# SixPak_Ultra.net
KiCad netlist of a schematic drawn in Altium Designer
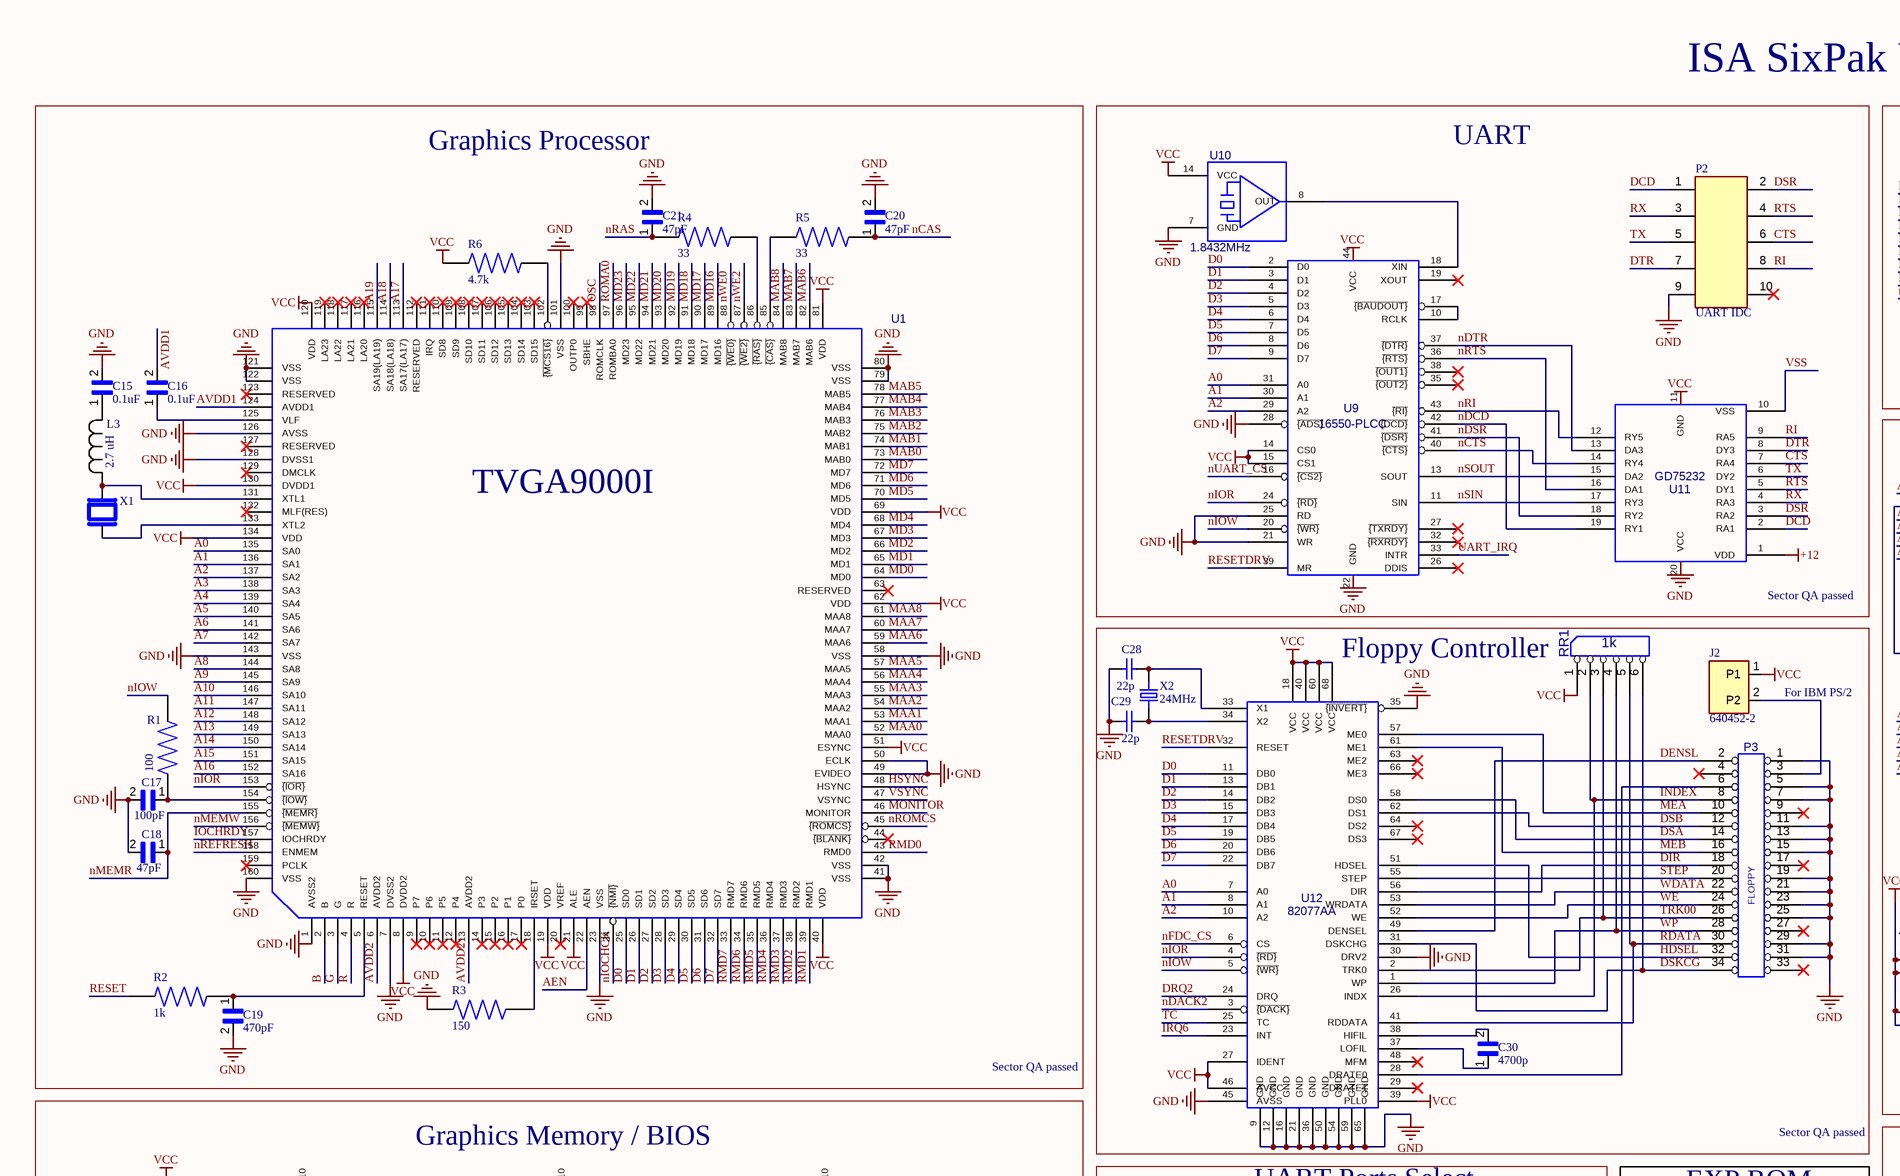
[diagram p0: SixPak Ultra.SchDoc, top left]
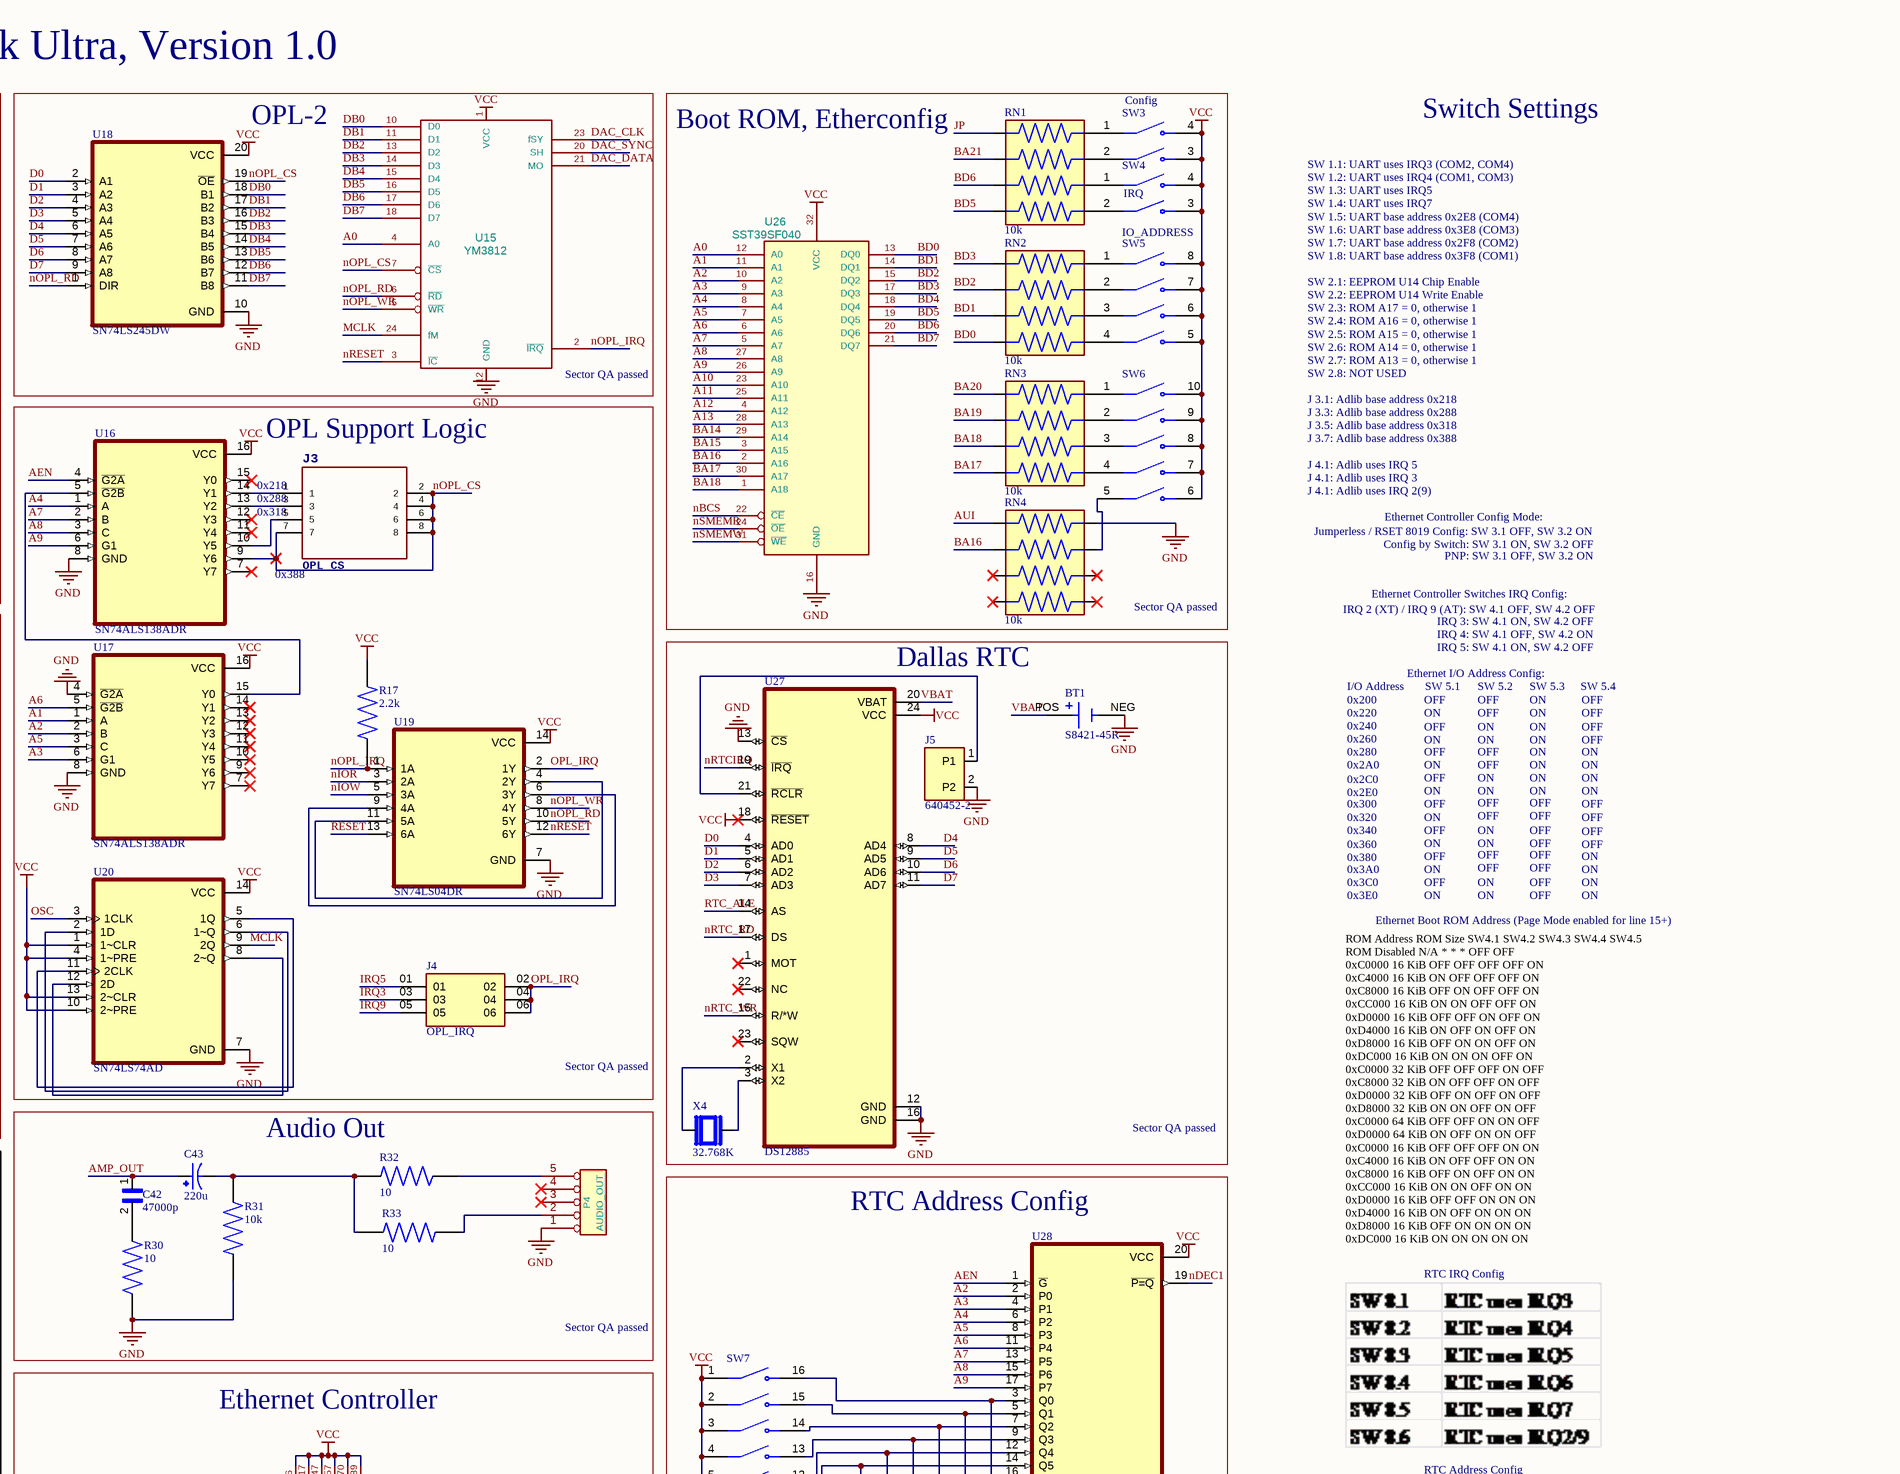
[diagram p1: SixPak Ultra.SchDoc, top right]
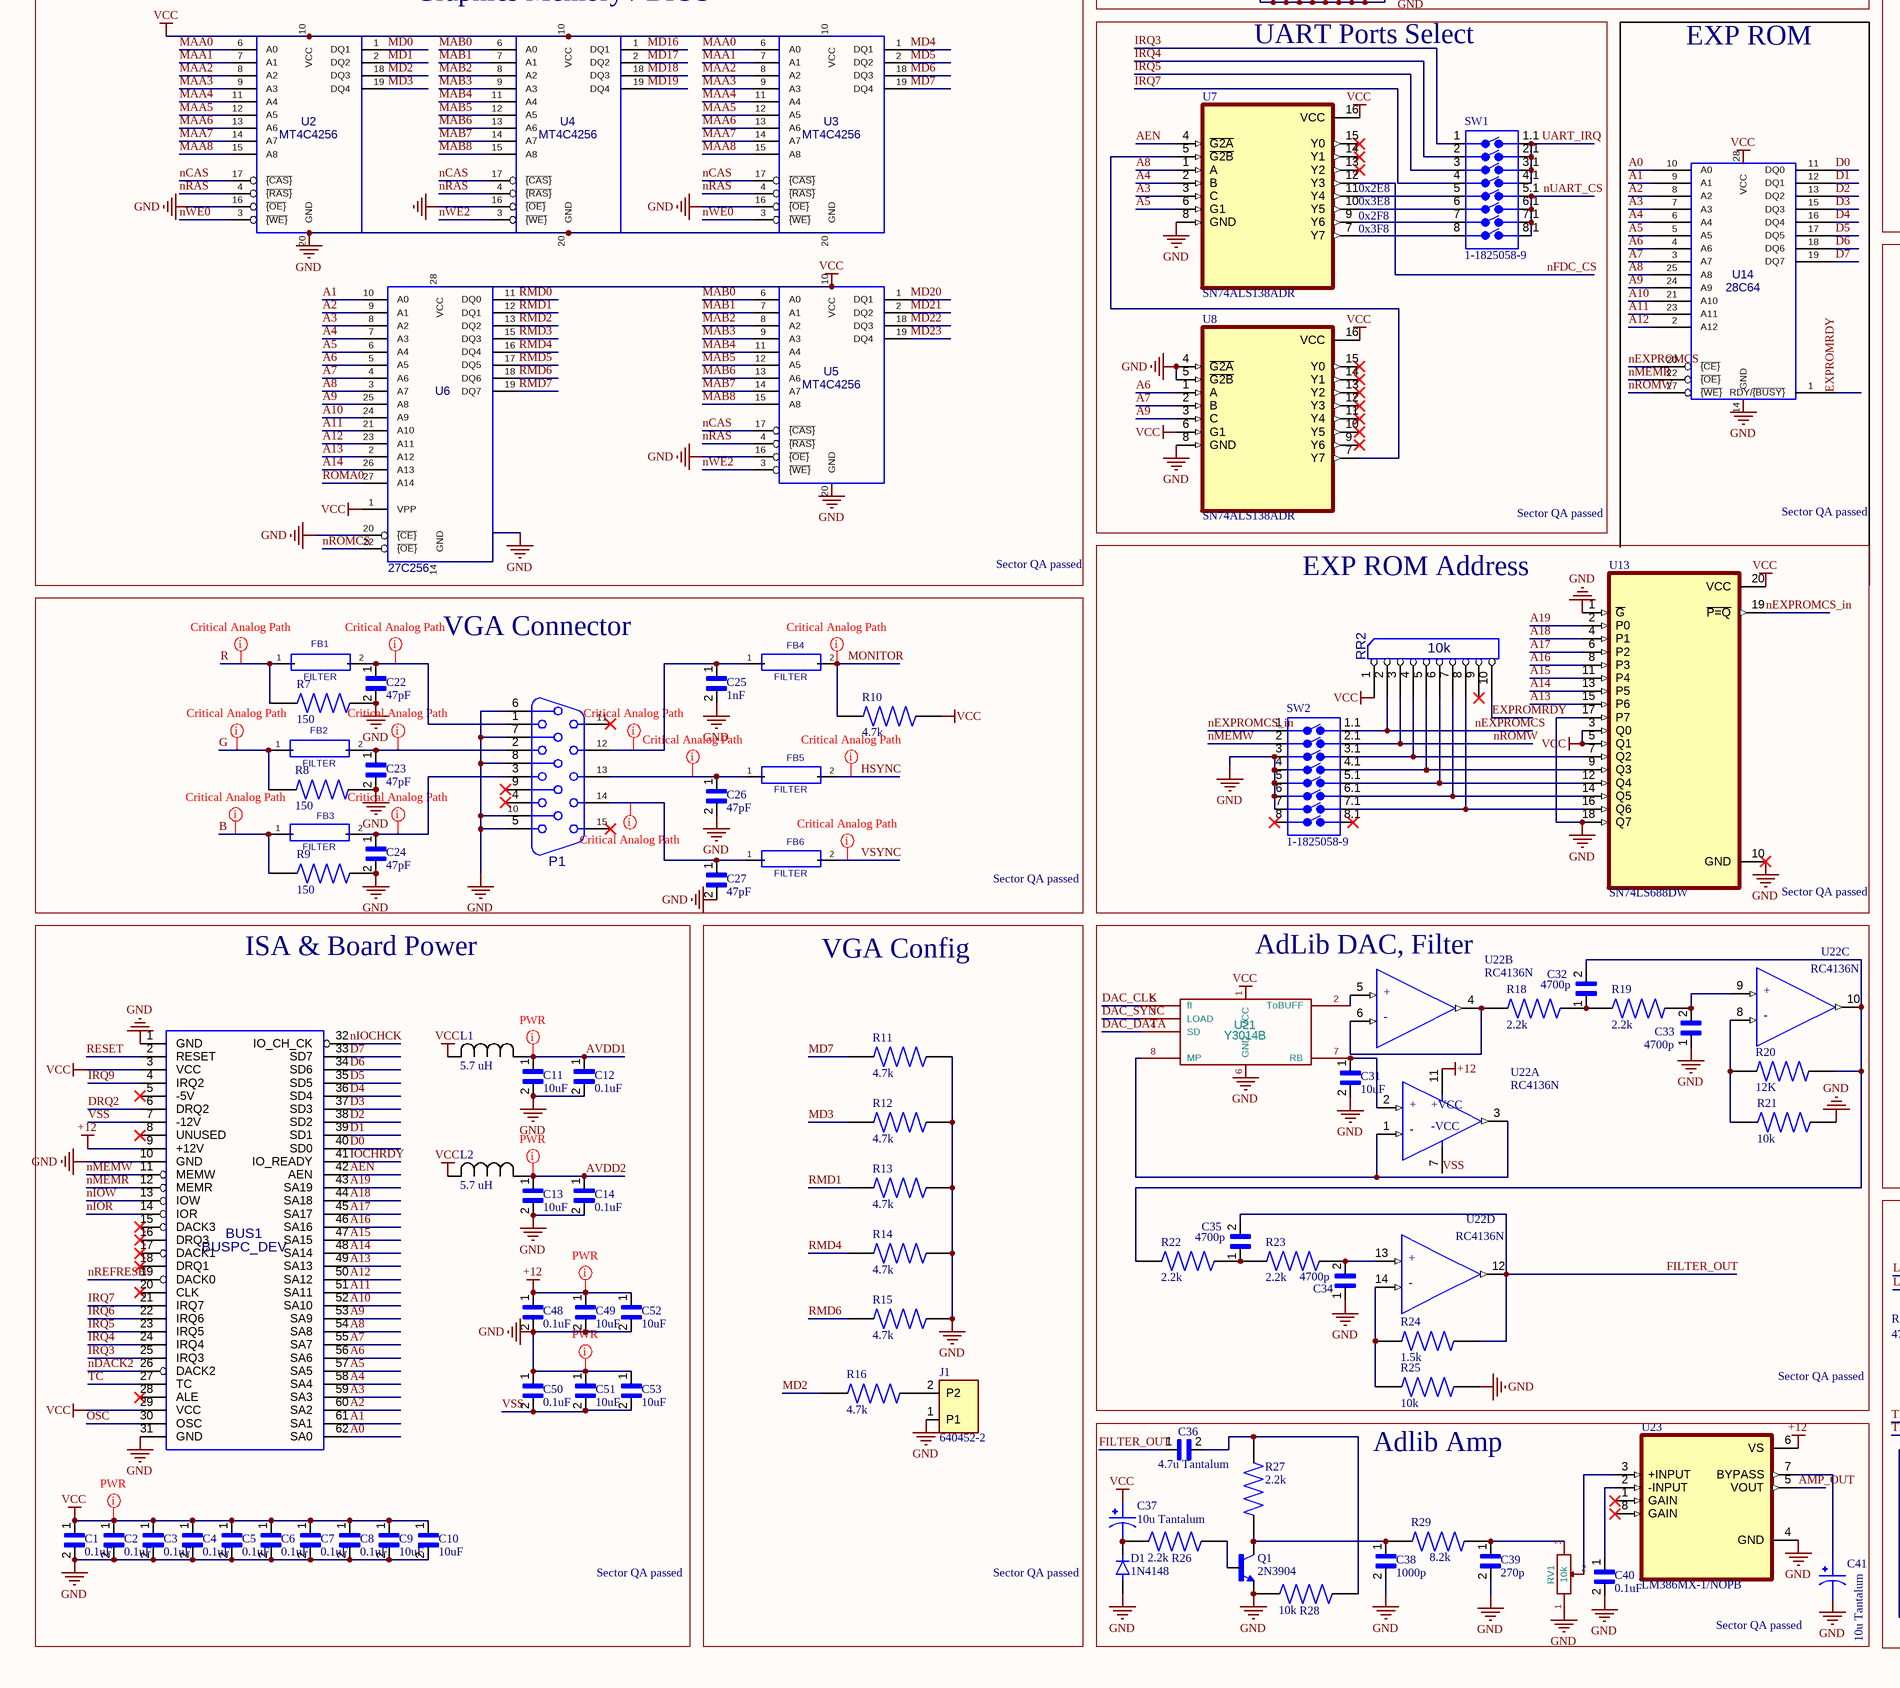
[diagram p2: SixPak Ultra.SchDoc, bottom left]
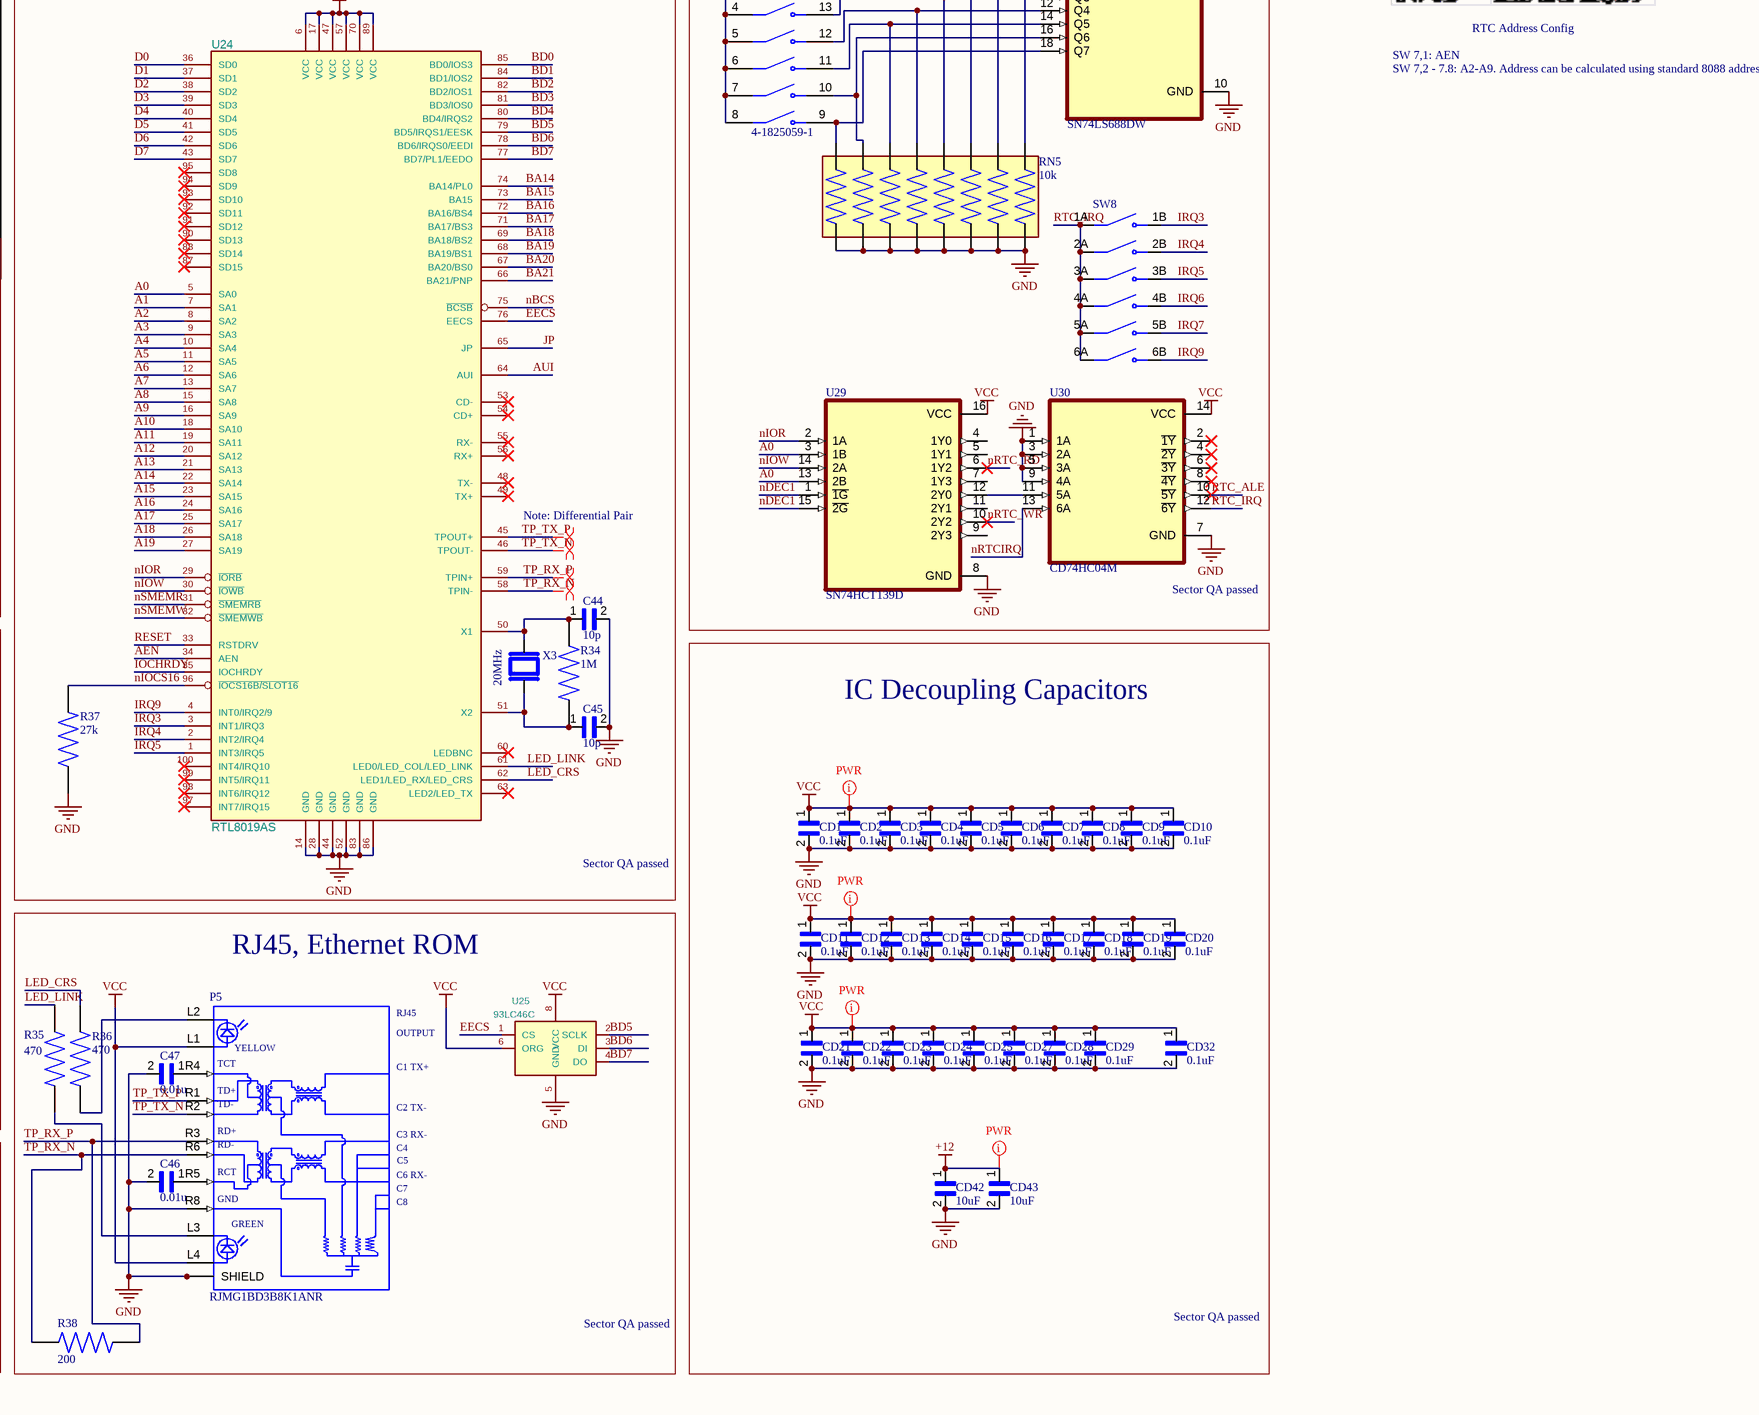
[diagram p3: SixPak Ultra.SchDoc, bottom right]

(export (version "E")
  (design (tool "Eeschema 10.0.6"))
  (components
    (comp (ref "BT1")
      (value "S8421-45R")
      (footprint "BAT_S8421-45R")
      (description "Battery Holder (Open) Coin, 20.0mm 1 Cell SMD (SMT) Tab")
      (fields (field (name "MF") "{'manufacturer': u'Harwin Inc.'}"))
      (libsource (lib "SixPakUltra_Mac") (part "S8421-45R"))
    )
    (comp (ref "BUS1")
      (value "BUSPC_DEV")
      (footprint "Conn_Bus_ISA8")
      (libsource (lib "isa_svga-rescue") (part "BUSPC_DEV"))
    )
    (comp (ref "C1")
      (value "0.1uF")
      (footprint "CAPC2012X140N")
      (description "0.1ÂµF Molded Tantalum Capacitors 35V 0805 _2012 Metric_ 29Ohm")
      (fields (field (name "MF") "AVX") (field (name "MP") "TAJR104K035RNJ"))
      (libsource (lib "TAJR104K035RNJ") (part "TAJR104K035RNJ"))
    )
    (comp (ref "C2")
      (value "0.1uF")
      (footprint "CAPC2012X140N")
      (description "0.1ÂµF Molded Tantalum Capacitors 35V 0805 _2012 Metric_ 29Ohm")
      (fields (field (name "MF") "AVX") (field (name "MP") "TAJR104K035RNJ"))
      (libsource (lib "TAJR104K035RNJ") (part "TAJR104K035RNJ"))
    )
    (comp (ref "C3")
      (value "0.1uF")
      (footprint "CAPC2012X140N")
      (description "0.1ÂµF Molded Tantalum Capacitors 35V 0805 _2012 Metric_ 29Ohm")
      (fields (field (name "MF") "AVX") (field (name "MP") "TAJR104K035RNJ"))
      (libsource (lib "TAJR104K035RNJ") (part "TAJR104K035RNJ"))
    )
    (comp (ref "C4")
      (value "0.1uF")
      (footprint "CAPC2012X140N")
      (description "0.1ÂµF Molded Tantalum Capacitors 35V 0805 _2012 Metric_ 29Ohm")
      (fields (field (name "MF") "AVX") (field (name "MP") "TAJR104K035RNJ"))
      (libsource (lib "TAJR104K035RNJ") (part "TAJR104K035RNJ"))
    )
    (comp (ref "C5")
      (value "0.1uF")
      (footprint "CAPC2012X140N")
      (description "0.1ÂµF Molded Tantalum Capacitors 35V 0805 _2012 Metric_ 29Ohm")
      (fields (field (name "MF") "AVX") (field (name "MP") "TAJR104K035RNJ"))
      (libsource (lib "TAJR104K035RNJ") (part "TAJR104K035RNJ"))
    )
    (comp (ref "C6")
      (value "0.1uF")
      (footprint "CAPC2012X140N")
      (description "0.1ÂµF Molded Tantalum Capacitors 35V 0805 _2012 Metric_ 29Ohm")
      (fields (field (name "MF") "AVX") (field (name "MP") "TAJR104K035RNJ"))
      (libsource (lib "TAJR104K035RNJ") (part "TAJR104K035RNJ"))
    )
    (comp (ref "C7")
      (value "0.1uF")
      (footprint "CAPC2012X140N")
      (description "0.1ÂµF Molded Tantalum Capacitors 35V 0805 _2012 Metric_ 29Ohm")
      (fields (field (name "MF") "AVX") (field (name "MP") "TAJR104K035RNJ"))
      (libsource (lib "TAJR104K035RNJ") (part "TAJR104K035RNJ"))
    )
    (comp (ref "C8")
      (value "0.1uF")
      (footprint "CAPC2012X140N")
      (description "0.1ÂµF Molded Tantalum Capacitors 35V 0805 _2012 Metric_ 29Ohm")
      (fields (field (name "MF") "AVX") (field (name "MP") "TAJR104K035RNJ"))
      (libsource (lib "TAJR104K035RNJ") (part "TAJR104K035RNJ"))
    )
    (comp (ref "C9")
      (value "10uF")
      (footprint "CAPC2012X140N")
      (description "Cap Tant Solid 10uF 16V R CASE 10% (2 X 1.35 X 1.35mm) SMD 2012-15 5 Ohm 125ÂÂŽ T/R")
      (fields (field (name "MP") "TACR106K016XTA"))
      (libsource (lib "TACR106K016XTA") (part "TACR106K016XTA"))
    )
    (comp (ref "C10")
      (value "10uF")
      (footprint "CAPC2012X140N")
      (description "Cap Tant Solid 10uF 16V R CASE 10% (2 X 1.35 X 1.35mm) SMD 2012-15 5 Ohm 125ÂÂŽ T/R")
      (fields (field (name "MP") "TACR106K016XTA"))
      (libsource (lib "TACR106K016XTA") (part "TACR106K016XTA"))
    )
    (comp (ref "C11")
      (value "10uF")
      (footprint "CAPC2012X140N")
      (description "Cap Tant Solid 10uF 16V R CASE 10% (2 X 1.35 X 1.35mm) SMD 2012-15 5 Ohm 125ÂÂŽ T/R")
      (fields (field (name "MP") "TACR106K016XTA"))
      (libsource (lib "TACR106K016XTA") (part "TACR106K016XTA"))
    )
    (comp (ref "C12")
      (value "0.1uF")
      (footprint "CAPC2012X140N")
      (description "0.1ÂµF Molded Tantalum Capacitors 35V 0805 _2012 Metric_ 29Ohm")
      (fields (field (name "MF") "AVX") (field (name "MP") "TAJR104K035RNJ"))
      (libsource (lib "TAJR104K035RNJ") (part "TAJR104K035RNJ"))
    )
    (comp (ref "C13")
      (value "10uF")
      (footprint "CAPC2012X140N")
      (description "Cap Tant Solid 10uF 16V R CASE 10% (2 X 1.35 X 1.35mm) SMD 2012-15 5 Ohm 125ÂÂŽ T/R")
      (fields (field (name "MP") "TACR106K016XTA"))
      (libsource (lib "TACR106K016XTA") (part "TACR106K016XTA"))
    )
    (comp (ref "C14")
      (value "0.1uF")
      (footprint "CAPC2012X140N")
      (description "0.1ÂµF Molded Tantalum Capacitors 35V 0805 _2012 Metric_ 29Ohm")
      (fields (field (name "MF") "AVX") (field (name "MP") "TAJR104K035RNJ"))
      (libsource (lib "TAJR104K035RNJ") (part "TAJR104K035RNJ"))
    )
    (comp (ref "C15")
      (value "0.1uF")
      (footprint "CAPC2012X145N")
      (description "0.1 ÂµF Â±10% 50V Ceramic Capacitor X8R 0805 (2012 Metric)")
      (fields (field (name "MF") "TDK") (field (name "MP") "CGA4J2X8R1H104K125AA"))
      (libsource (lib "CGA4J2X8R1H104K125AA") (part "CGA4J2X8R1H104K125AA"))
    )
    (comp (ref "C16")
      (value "0.1uF")
      (footprint "CAPC2012X145N")
      (description "0.1 ÂµF Â±10% 50V Ceramic Capacitor X8R 0805 (2012 Metric)")
      (fields (field (name "MF") "TDK") (field (name "MP") "CGA4J2X8R1H104K125AA"))
      (libsource (lib "CGA4J2X8R1H104K125AA") (part "CGA4J2X8R1H104K125AA"))
    )
    (comp (ref "C17")
      (value "100pF")
      (footprint "CAPC2012X88N")
      (fields (field (name "MP") "C0805C101J5RAC7800"))
      (libsource (lib "C0805C101J5RAC7800") (part "C0805C101J5RAC7800"))
    )
    (comp (ref "C18")
      (value "47pF")
      (footprint "CAPC2012X94N")
      (description "Capacitor: ceramic; 47pF; 50V; C0G; Â±5%; SMD; Case (inch):0805")
      (fields (field (name "MP") "08055A470JAT2A"))
      (libsource (lib "") (part "08055A470JAT2A_2"))
    )
    (comp (ref "C19")
      (value "470pF")
      (footprint "CAPC2012X94N")
      (description "Capacitor: ceramic; 47pF; 50V; C0G; Â±5%; SMD; Case (inch):0805")
      (fields (field (name "MP") "08055A470JAT2A"))
      (libsource (lib "") (part "08055A470JAT2A_1"))
    )
    (comp (ref "C20")
      (value "47pF")
      (footprint "CAPC2012X94N")
      (description "Capacitor: ceramic; 47pF; 50V; C0G; Â±5%; SMD; Case (inch):0805")
      (fields (field (name "MP") "08055A470JAT2A"))
      (libsource (lib "08055A470JAT2A") (part "08055A470JAT2A"))
    )
    (comp (ref "C21")
      (value "47pF")
      (footprint "CAPC2012X94N")
      (description "Capacitor: ceramic; 47pF; 50V; C0G; Â±5%; SMD; Case (inch):0805")
      (fields (field (name "MP") "08055A470JAT2A"))
      (libsource (lib "08055A470JAT2A") (part "08055A470JAT2A"))
    )
    (comp (ref "C22")
      (value "47pF")
      (footprint "CAPC2012X94N")
      (description "Capacitor: ceramic; 47pF; 50V; C0G; Â±5%; SMD; Case (inch):0805")
      (fields (field (name "MP") "08055A470JAT2A"))
      (libsource (lib "") (part "08055A470JAT2A_1"))
    )
    (comp (ref "C23")
      (value "47pF")
      (footprint "CAPC2012X94N")
      (description "Capacitor: ceramic; 47pF; 50V; C0G; Â±5%; SMD; Case (inch):0805")
      (fields (field (name "MP") "08055A470JAT2A"))
      (libsource (lib "") (part "08055A470JAT2A_1"))
    )
    (comp (ref "C24")
      (value "47pF")
      (footprint "CAPC2012X94N")
      (description "Capacitor: ceramic; 47pF; 50V; C0G; Â±5%; SMD; Case (inch):0805")
      (fields (field (name "MP") "08055A470JAT2A"))
      (libsource (lib "") (part "08055A470JAT2A_1"))
    )
    (comp (ref "C25")
      (value "1nF")
      (footprint "CAPC2012X70")
      (description "1ÂµF Â±10% 25V Ceramic Capacitor X7R 0805 (2012 Metric)")
      (fields (field (name "MP") "CC0805KFX7R8BB105") (field (name "MF") "Yageo"))
      (libsource (lib "CC0805KFX7R8BB105") (part "CC0805KFX7R8BB105"))
    )
    (comp (ref "C26")
      (value "47pF")
      (footprint "CAPC2012X94N")
      (description "Capacitor: ceramic; 47pF; 50V; C0G; Â±5%; SMD; Case (inch):0805")
      (fields (field (name "MP") "08055A470JAT2A"))
      (libsource (lib "") (part "08055A470JAT2A_1"))
    )
    (comp (ref "C27")
      (value "47pF")
      (footprint "CAPC2012X94N")
      (description "Capacitor: ceramic; 47pF; 50V; C0G; Â±5%; SMD; Case (inch):0805")
      (fields (field (name "MP") "08055A470JAT2A"))
      (libsource (lib "") (part "08055A470JAT2A_1"))
    )
    (comp (ref "C28")
      (value "22p")
      (footprint "CAPC2013X145X50NL20T20")
      (fields (field (name "MANUFACTURER") "Vitramon") (field (name "PART NUMBER") "VJ0805A220KXJPW1BC"))
      (libsource (lib "Altium Content Vault") (part "CAP"))
    )
    (comp (ref "C29")
      (value "22p")
      (footprint "CAPC2013X145X50NL20T20")
      (fields (field (name "MANUFACTURER") "Vitramon") (field (name "PART NUMBER") "VJ0805A220KXJPW1BC"))
      (libsource (lib "Altium Content Vault") (part "CAP"))
    )
    (comp (ref "C30")
      (value "4700p")
      (footprint "CAPC2012X100N")
      (fields (field (name "MP") "C0805C472J2GAC7800"))
      (libsource (lib "C0805C472J2GAC7800") (part "C0805C472J2GAC7800"))
    )
    (comp (ref "C31")
      (value "10uF")
      (footprint "CAPC2012X140N")
      (description "Cap Tant Solid 10uF 16V R CASE 10% (2 X 1.35 X 1.35mm) SMD 2012-15 5 Ohm 125ÂÂŽ T/R")
      (fields (field (name "MP") "TACR106K016XTA"))
      (libsource (lib "TACR106K016XTA") (part "TACR106K016XTA"))
    )
    (comp (ref "C32")
      (value "4700p")
      (footprint "CAPC2012X100N")
      (fields (field (name "MP") "C0805C472J2GAC7800"))
      (libsource (lib "C0805C472J2GAC7800") (part "C0805C472J2GAC7800"))
    )
    (comp (ref "C33")
      (value "4700p")
      (footprint "CAPC2012X100N")
      (fields (field (name "MP") "C0805C472J2GAC7800"))
      (libsource (lib "C0805C472J2GAC7800") (part "C0805C472J2GAC7800"))
    )
    (comp (ref "C34")
      (value "4700p")
      (footprint "CAPC2012X100N")
      (fields (field (name "MP") "C0805C472J2GAC7800"))
      (libsource (lib "C0805C472J2GAC7800") (part "C0805C472J2GAC7800"))
    )
    (comp (ref "C35")
      (value "4700p")
      (footprint "CAPC2012X100N")
      (fields (field (name "MP") "C0805C472J2GAC7800"))
      (libsource (lib "C0805C472J2GAC7800") (part "C0805C472J2GAC7800"))
    )
    (comp (ref "C36")
      (value "4.7u Tantalum")
      (footprint "CAPC2012X140N")
      (description "4.7uF SMD Solid MnO2 Tantalum Electrolytic Capacitor, 20 V dc +/-20%, TAC Series")
      (fields (field (name "MP") "TACR475M020XTA"))
      (libsource (lib "TACR475M020XTA") (part "TACR475M020XTA"))
    )
    (comp (ref "C37")
      (value "10u Tantalum")
      (footprint "CAPPM6032X280N")
      (description "10ÂµF Molded Tantalum Capacitors 16V 2312 (6032 Metric) 2Ohm")
      (fields (field (name "MP") "TAJC106J016RNJ") (field (name "MF") "AVX"))
      (libsource (lib "TAJC106J016RNJ") (part "TAJC106J016RNJ"))
    )
    (comp (ref "C38")
      (value "1000p")
      (footprint "CAPC2012X94N")
      (description "CAP CER 1000PF 16V 5% X7R 0805")
      (fields (field (name "MP") "0805YC102JAT2A"))
      (libsource (lib "0805YC102JAT2A") (part "0805YC102JAT2A"))
    )
    (comp (ref "C39")
      (value "270p")
      (footprint "CAPC2012X88N")
      (description "CAP, MLCC, C0G, 270PF, 50V, 0805")
      (fields (field (name "MP") "C0805C271F5GACTU"))
      (libsource (lib "C0805C271F5GACTU") (part "C0805C271F5GACTU"))
    )
    (comp (ref "C40")
      (value "0.1uF")
      (footprint "CAPC2012X140N")
      (description "0.1ÂµF Molded Tantalum Capacitors 35V 0805 _2012 Metric_ 29Ohm")
      (fields (field (name "MF") "AVX") (field (name "MP") "TAJR104K035RNJ"))
      (libsource (lib "TAJR104K035RNJ") (part "TAJR104K035RNJ"))
    )
    (comp (ref "C41")
      (value "10u Tantalum")
      (footprint "CAPPM6032X280N")
      (description "10ÂµF Molded Tantalum Capacitors 16V 2312 (6032 Metric) 2Ohm")
      (fields (field (name "MP") "TAJC106J016RNJ") (field (name "MF") "AVX"))
      (libsource (lib "TAJC106J016RNJ") (part "TAJC106J016RNJ"))
    )
    (comp (ref "C42")
      (value "47000p")
      (footprint "CAPC2012X75N")
      (description "4700 pF Â±5% 50V Ceramic Capacitor C0G, NP0 0805 (2012 Metric)")
      (fields (field (name "MF") "TDK") (field (name "MP") "CGA4C2C0G1H472J060AA"))
      (libsource (lib "CGA4C2C0G1H472J060AA") (part "CGA4C2C0G1H472J060AA"))
    )
    (comp (ref "C43")
      (value "220u")
      (footprint "CAPPRD350W60D800H1150")
      (description "470F 16V Aluminum Electrolytic Capacitors Radial, Can 2000 Hrs @ 85C")
      (fields (field (name "MF") "Panasonic") (field (name "MP") "ECA1CM471"))
      (libsource (lib "ECA1CM471") (part "ECA1CM471"))
    )
    (comp (ref "C44")
      (value "10p")
      (footprint "CAPC2012X88N")
      (fields (field (name "MP") "C0805C100K4HACAUTO"))
      (libsource (lib "C0805C100K4HACAUTO") (part "C0805C100K4HACAUTO"))
    )
    (comp (ref "C45")
      (value "10p")
      (footprint "CAPC2012X88N")
      (fields (field (name "MP") "C0805C100K4HACAUTO"))
      (libsource (lib "C0805C100K4HACAUTO") (part "C0805C100K4HACAUTO"))
    )
    (comp (ref "C46")
      (value "0.01u")
      (footprint "CAPC2012X88N")
      (fields (field (name "MP") "C0805C103J4RAC7800"))
      (libsource (lib "C0805C103J4RAC7800") (part "C0805C103J4RAC7800"))
    )
    (comp (ref "C47")
      (value "0.01u")
      (footprint "CAPC2012X88N")
      (fields (field (name "MP") "C0805C103J4RAC7800"))
      (libsource (lib "C0805C103J4RAC7800") (part "C0805C103J4RAC7800"))
    )
    (comp (ref "C48")
      (value "0.1uF")
      (footprint "CAPC2012X140N")
      (description "0.1ÂµF Molded Tantalum Capacitors 35V 0805 _2012 Metric_ 29Ohm")
      (fields (field (name "MF") "AVX") (field (name "MP") "TAJR104K035RNJ"))
      (libsource (lib "TAJR104K035RNJ") (part "TAJR104K035RNJ"))
    )
    (comp (ref "C49")
      (value "10uF")
      (footprint "CAPC2012X140N")
      (description "Cap Tant Solid 10uF 16V R CASE 10% (2 X 1.35 X 1.35mm) SMD 2012-15 5 Ohm 125ÂÂŽ T/R")
      (fields (field (name "MP") "TACR106K016XTA"))
      (libsource (lib "TACR106K016XTA") (part "TACR106K016XTA"))
    )
    (comp (ref "C50")
      (value "0.1uF")
      (footprint "CAPC2012X140N")
      (description "0.1ÂµF Molded Tantalum Capacitors 35V 0805 _2012 Metric_ 29Ohm")
      (fields (field (name "MF") "AVX") (field (name "MP") "TAJR104K035RNJ"))
      (libsource (lib "TAJR104K035RNJ") (part "TAJR104K035RNJ"))
    )
    (comp (ref "C51")
      (value "10uF")
      (footprint "CAPC2012X140N")
      (description "Cap Tant Solid 10uF 16V R CASE 10% (2 X 1.35 X 1.35mm) SMD 2012-15 5 Ohm 125ÂÂŽ T/R")
      (fields (field (name "MP") "TACR106K016XTA"))
      (libsource (lib "TACR106K016XTA") (part "TACR106K016XTA"))
    )
    (comp (ref "C52")
      (value "10uF")
      (footprint "CAPC2012X140N")
      (description "Cap Tant Solid 10uF 16V R CASE 10% (2 X 1.35 X 1.35mm) SMD 2012-15 5 Ohm 125ÂÂŽ T/R")
      (fields (field (name "MP") "TACR106K016XTA"))
      (libsource (lib "TACR106K016XTA") (part "TACR106K016XTA"))
    )
    (comp (ref "C53")
      (value "10uF")
      (footprint "CAPC2012X140N")
      (description "Cap Tant Solid 10uF 16V R CASE 10% (2 X 1.35 X 1.35mm) SMD 2012-15 5 Ohm 125ÂÂŽ T/R")
      (fields (field (name "MP") "TACR106K016XTA"))
      (libsource (lib "TACR106K016XTA") (part "TACR106K016XTA"))
    )
    (comp (ref "CD1")
      (value "0.1uF")
      (footprint "CAPC2012X140N")
      (description "0.1ÂµF Molded Tantalum Capacitors 35V 0805 _2012 Metric_ 29Ohm")
      (fields (field (name "MF") "AVX") (field (name "MP") "TAJR104K035RNJ"))
      (libsource (lib "TAJR104K035RNJ") (part "TAJR104K035RNJ"))
    )
    (comp (ref "CD2")
      (value "0.1uF")
      (footprint "CAPC2012X140N")
      (description "0.1ÂµF Molded Tantalum Capacitors 35V 0805 _2012 Metric_ 29Ohm")
      (fields (field (name "MF") "AVX") (field (name "MP") "TAJR104K035RNJ"))
      (libsource (lib "TAJR104K035RNJ") (part "TAJR104K035RNJ"))
    )
    (comp (ref "CD3")
      (value "0.1uF")
      (footprint "CAPC2012X140N")
      (description "0.1ÂµF Molded Tantalum Capacitors 35V 0805 _2012 Metric_ 29Ohm")
      (fields (field (name "MF") "AVX") (field (name "MP") "TAJR104K035RNJ"))
      (libsource (lib "TAJR104K035RNJ") (part "TAJR104K035RNJ"))
    )
    (comp (ref "CD4")
      (value "0.1uF")
      (footprint "CAPC2012X140N")
      (description "0.1ÂµF Molded Tantalum Capacitors 35V 0805 _2012 Metric_ 29Ohm")
      (fields (field (name "MF") "AVX") (field (name "MP") "TAJR104K035RNJ"))
      (libsource (lib "TAJR104K035RNJ") (part "TAJR104K035RNJ"))
    )
    (comp (ref "CD5")
      (value "0.1uF")
      (footprint "CAPC2012X140N")
      (description "0.1ÂµF Molded Tantalum Capacitors 35V 0805 _2012 Metric_ 29Ohm")
      (fields (field (name "MF") "AVX") (field (name "MP") "TAJR104K035RNJ"))
      (libsource (lib "TAJR104K035RNJ") (part "TAJR104K035RNJ"))
    )
    (comp (ref "CD6")
      (value "0.1uF")
      (footprint "CAPC2012X140N")
      (description "0.1ÂµF Molded Tantalum Capacitors 35V 0805 _2012 Metric_ 29Ohm")
      (fields (field (name "MF") "AVX") (field (name "MP") "TAJR104K035RNJ"))
      (libsource (lib "TAJR104K035RNJ") (part "TAJR104K035RNJ"))
    )
    (comp (ref "CD7")
      (value "0.1uF")
      (footprint "CAPC2012X140N")
      (description "0.1ÂµF Molded Tantalum Capacitors 35V 0805 _2012 Metric_ 29Ohm")
      (fields (field (name "MF") "AVX") (field (name "MP") "TAJR104K035RNJ"))
      (libsource (lib "TAJR104K035RNJ") (part "TAJR104K035RNJ"))
    )
    (comp (ref "CD8")
      (value "0.1uF")
      (footprint "CAPC2012X140N")
      (description "0.1ÂµF Molded Tantalum Capacitors 35V 0805 _2012 Metric_ 29Ohm")
      (fields (field (name "MF") "AVX") (field (name "MP") "TAJR104K035RNJ"))
      (libsource (lib "TAJR104K035RNJ") (part "TAJR104K035RNJ"))
    )
    (comp (ref "CD9")
      (value "0.1uF")
      (footprint "CAPC2012X140N")
      (description "0.1ÂµF Molded Tantalum Capacitors 35V 0805 _2012 Metric_ 29Ohm")
      (fields (field (name "MF") "AVX") (field (name "MP") "TAJR104K035RNJ"))
      (libsource (lib "TAJR104K035RNJ") (part "TAJR104K035RNJ"))
    )
    (comp (ref "CD10")
      (value "0.1uF")
      (footprint "CAPC2012X140N")
      (description "0.1ÂµF Molded Tantalum Capacitors 35V 0805 _2012 Metric_ 29Ohm")
      (fields (field (name "MF") "AVX") (field (name "MP") "TAJR104K035RNJ"))
      (libsource (lib "TAJR104K035RNJ") (part "TAJR104K035RNJ"))
    )
    (comp (ref "CD11")
      (value "0.1uF")
      (footprint "CAPC2012X140N")
      (description "0.1ÂµF Molded Tantalum Capacitors 35V 0805 _2012 Metric_ 29Ohm")
      (fields (field (name "MF") "AVX") (field (name "MP") "TAJR104K035RNJ"))
      (libsource (lib "TAJR104K035RNJ") (part "TAJR104K035RNJ"))
    )
    (comp (ref "CD12")
      (value "0.1uF")
      (footprint "CAPC2012X140N")
      (description "0.1ÂµF Molded Tantalum Capacitors 35V 0805 _2012 Metric_ 29Ohm")
      (fields (field (name "MF") "AVX") (field (name "MP") "TAJR104K035RNJ"))
      (libsource (lib "TAJR104K035RNJ") (part "TAJR104K035RNJ"))
    )
    (comp (ref "CD13")
      (value "0.1uF")
      (footprint "CAPC2012X140N")
      (description "0.1ÂµF Molded Tantalum Capacitors 35V 0805 _2012 Metric_ 29Ohm")
      (fields (field (name "MF") "AVX") (field (name "MP") "TAJR104K035RNJ"))
      (libsource (lib "TAJR104K035RNJ") (part "TAJR104K035RNJ"))
    )
    (comp (ref "CD14")
      (value "0.1uF")
      (footprint "CAPC2012X140N")
      (description "0.1ÂµF Molded Tantalum Capacitors 35V 0805 _2012 Metric_ 29Ohm")
      (fields (field (name "MF") "AVX") (field (name "MP") "TAJR104K035RNJ"))
      (libsource (lib "TAJR104K035RNJ") (part "TAJR104K035RNJ"))
    )
    (comp (ref "CD15")
      (value "0.1uF")
      (footprint "CAPC2012X140N")
      (description "0.1ÂµF Molded Tantalum Capacitors 35V 0805 _2012 Metric_ 29Ohm")
      (fields (field (name "MF") "AVX") (field (name "MP") "TAJR104K035RNJ"))
      (libsource (lib "TAJR104K035RNJ") (part "TAJR104K035RNJ"))
    )
    (comp (ref "CD16")
      (value "0.1uF")
      (footprint "CAPC2012X140N")
      (description "0.1ÂµF Molded Tantalum Capacitors 35V 0805 _2012 Metric_ 29Ohm")
      (fields (field (name "MF") "AVX") (field (name "MP") "TAJR104K035RNJ"))
      (libsource (lib "TAJR104K035RNJ") (part "TAJR104K035RNJ"))
    )
    (comp (ref "CD17")
      (value "0.1uF")
      (footprint "CAPC2012X140N")
      (description "0.1ÂµF Molded Tantalum Capacitors 35V 0805 _2012 Metric_ 29Ohm")
      (fields (field (name "MF") "AVX") (field (name "MP") "TAJR104K035RNJ"))
      (libsource (lib "TAJR104K035RNJ") (part "TAJR104K035RNJ"))
    )
    (comp (ref "CD18")
      (value "0.1uF")
      (footprint "CAPC2012X140N")
      (description "0.1ÂµF Molded Tantalum Capacitors 35V 0805 _2012 Metric_ 29Ohm")
      (fields (field (name "MF") "AVX") (field (name "MP") "TAJR104K035RNJ"))
      (libsource (lib "TAJR104K035RNJ") (part "TAJR104K035RNJ"))
    )
    (comp (ref "CD19")
      (value "0.1uF")
      (footprint "CAPC2012X140N")
      (description "0.1ÂµF Molded Tantalum Capacitors 35V 0805 _2012 Metric_ 29Ohm")
      (fields (field (name "MF") "AVX") (field (name "MP") "TAJR104K035RNJ"))
      (libsource (lib "TAJR104K035RNJ") (part "TAJR104K035RNJ"))
    )
    (comp (ref "CD20")
      (value "0.1uF")
      (footprint "CAPC2012X140N")
      (description "0.1ÂµF Molded Tantalum Capacitors 35V 0805 _2012 Metric_ 29Ohm")
      (fields (field (name "MF") "AVX") (field (name "MP") "TAJR104K035RNJ"))
      (libsource (lib "TAJR104K035RNJ") (part "TAJR104K035RNJ"))
    )
    (comp (ref "CD21")
      (value "0.1uF")
      (footprint "CAPC2012X140N")
      (description "0.1ÂµF Molded Tantalum Capacitors 35V 0805 _2012 Metric_ 29Ohm")
      (fields (field (name "MF") "AVX") (field (name "MP") "TAJR104K035RNJ"))
      (libsource (lib "TAJR104K035RNJ") (part "TAJR104K035RNJ"))
    )
    (comp (ref "CD22")
      (value "0.1uF")
      (footprint "CAPC2012X140N")
      (description "0.1ÂµF Molded Tantalum Capacitors 35V 0805 _2012 Metric_ 29Ohm")
      (fields (field (name "MF") "AVX") (field (name "MP") "TAJR104K035RNJ"))
      (libsource (lib "TAJR104K035RNJ") (part "TAJR104K035RNJ"))
    )
    (comp (ref "CD23")
      (value "0.1uF")
      (footprint "CAPC2012X140N")
      (description "0.1ÂµF Molded Tantalum Capacitors 35V 0805 _2012 Metric_ 29Ohm")
      (fields (field (name "MF") "AVX") (field (name "MP") "TAJR104K035RNJ"))
      (libsource (lib "TAJR104K035RNJ") (part "TAJR104K035RNJ"))
    )
    (comp (ref "CD24")
      (value "0.1uF")
      (footprint "CAPC2012X140N")
      (description "0.1ÂµF Molded Tantalum Capacitors 35V 0805 _2012 Metric_ 29Ohm")
      (fields (field (name "MF") "AVX") (field (name "MP") "TAJR104K035RNJ"))
      (libsource (lib "TAJR104K035RNJ") (part "TAJR104K035RNJ"))
    )
    (comp (ref "CD25")
      (value "0.1uF")
      (footprint "CAPC2012X140N")
      (description "0.1ÂµF Molded Tantalum Capacitors 35V 0805 _2012 Metric_ 29Ohm")
      (fields (field (name "MF") "AVX") (field (name "MP") "TAJR104K035RNJ"))
      (libsource (lib "TAJR104K035RNJ") (part "TAJR104K035RNJ"))
    )
    (comp (ref "CD27")
      (value "0.1uF")
      (footprint "CAPC2012X140N")
      (description "0.1ÂµF Molded Tantalum Capacitors 35V 0805 _2012 Metric_ 29Ohm")
      (fields (field (name "MF") "AVX") (field (name "MP") "TAJR104K035RNJ"))
      (libsource (lib "TAJR104K035RNJ") (part "TAJR104K035RNJ"))
    )
    (comp (ref "CD28")
      (value "0.1uF")
      (footprint "CAPC2012X140N")
      (description "0.1ÂµF Molded Tantalum Capacitors 35V 0805 _2012 Metric_ 29Ohm")
      (fields (field (name "MF") "AVX") (field (name "MP") "TAJR104K035RNJ"))
      (libsource (lib "TAJR104K035RNJ") (part "TAJR104K035RNJ"))
    )
    (comp (ref "CD29")
      (value "0.1uF")
      (footprint "CAPC2012X140N")
      (description "0.1ÂµF Molded Tantalum Capacitors 35V 0805 _2012 Metric_ 29Ohm")
      (fields (field (name "MF") "AVX") (field (name "MP") "TAJR104K035RNJ"))
      (libsource (lib "TAJR104K035RNJ") (part "TAJR104K035RNJ"))
    )
    (comp (ref "CD32")
      (value "0.1uF")
      (footprint "CAPC2012X140N")
      (description "0.1ÂµF Molded Tantalum Capacitors 35V 0805 _2012 Metric_ 29Ohm")
      (fields (field (name "MF") "AVX") (field (name "MP") "TAJR104K035RNJ"))
      (libsource (lib "TAJR104K035RNJ") (part "TAJR104K035RNJ"))
    )
    (comp (ref "CD42")
      (value "10uF")
      (footprint "CAPC2012X140N")
      (description "Cap Tant Solid 10uF 16V R CASE 10% (2 X 1.35 X 1.35mm) SMD 2012-15 5 Ohm 125ÂÂŽ T/R")
      (fields (field (name "MP") "TACR106K016XTA"))
      (libsource (lib "TACR106K016XTA") (part "TACR106K016XTA"))
    )
    (comp (ref "CD43")
      (value "10uF")
      (footprint "CAPC2012X140N")
      (description "Cap Tant Solid 10uF 16V R CASE 10% (2 X 1.35 X 1.35mm) SMD 2012-15 5 Ohm 125ÂÂŽ T/R")
      (fields (field (name "MP") "TACR106K016XTA"))
      (libsource (lib "TACR106K016XTA") (part "TACR106K016XTA"))
    )
    (comp (ref "D1")
      (value "1N4148")
      (footprint "DIOAD829W49L456D191")
      (description "Small Signal Fast Switching Diodes")
      (libsource (lib "1N4148") (part "1N4148"))
    )
    (comp (ref "FB1")
      (value "FILTER")
      (footprint "FILTER")
      (libsource (lib "isa_svga-rescue") (part "FILTER"))
    )
    (comp (ref "FB2")
      (value "FILTER")
      (footprint "FILTER")
      (libsource (lib "isa_svga-rescue") (part "FILTER"))
    )
    (comp (ref "FB3")
      (value "FILTER")
      (footprint "FILTER")
      (libsource (lib "isa_svga-rescue") (part "FILTER"))
    )
    (comp (ref "FB4")
      (value "FILTER")
      (footprint "FILTER")
      (libsource (lib "isa_svga-rescue") (part "FILTER"))
    )
    (comp (ref "FB5")
      (value "FILTER")
      (footprint "FILTER")
      (libsource (lib "isa_svga-rescue") (part "FILTER"))
    )
    (comp (ref "FB6")
      (value "FILTER")
      (footprint "FILTER")
      (libsource (lib "isa_svga-rescue") (part "FILTER"))
    )
    (comp (ref "J1")
      (value "640452-2")
      (footprint "TE_640452-2")
      (description "Header, Friction Lock; MTA-100; 2; 250 VAC; Polyester; Tin; Copper Alloy; Tin")
      (fields (field (name "MF") "TE Connectivity") (field (name "DIGI-KEY_PART_NUMBER") "A1911-ND"))
      (libsource (lib "640452-2") (part "640452-2"))
    )
    (comp (ref "J2")
      (value "640452-2")
      (footprint "TE_640452-2")
      (description "Header, Friction Lock; MTA-100; 2; 250 VAC; Polyester; Tin; Copper Alloy; Tin")
      (fields (field (name "MF") "TE Connectivity") (field (name "DIGI-KEY_PART_NUMBER") "A1911-ND"))
      (libsource (lib "") (part "640452-2_1"))
    )
    (comp (ref "J3")
      (value "OPL CS")
      (footprint "SAMTEC-TSM-104-01-X-DV-A")
      (libsource (lib "SAMTEC-TSM-104-01-X-DV-A") (part "SAMTEC-TSM-104-01-X-DV-AJ"))
    )
    (comp (ref "J4")
      (value "OPL_IRQ")
      (footprint "SAMTEC_TSM-103-01-T-DV")
      (fields (field (name "MP") "TSM-103-01-T-DV") (field (name "MF") "Samtec"))
      (libsource (lib "TSM-103-01-T-DV") (part "TSM-103-01-T-DV"))
    )
    (comp (ref "J5")
      (value "640452-2")
      (footprint "TE_640452-2")
      (description "Header, Friction Lock; MTA-100; 2; 250 VAC; Polyester; Tin; Copper Alloy; Tin")
      (fields (field (name "MF") "TE Connectivity") (field (name "DIGI-KEY_PART_NUMBER") "A1911-ND"))
      (libsource (lib "") (part "640452-2_1"))
    )
    (comp (ref "L1")
      (value "5.7 uH")
      (footprint "IND_BOURNS_78F")
      (description "No Description Available")
      (fields
        (field (name "MANUFACTURER_PART_NUMBER") "78F5R6J-RC")
        (field (name "COPYRIGHT") "Copyright (C) 2022 Ultra Librarian. All rights reserved.")
      )
      (libsource (lib "78F5R6J-RC") (part "78F5R6J-RC"))
    )
    (comp (ref "L2")
      (value "5.7 uH")
      (footprint "IND_BOURNS_78F")
      (description "No Description Available")
      (fields
        (field (name "MANUFACTURER_PART_NUMBER") "78F5R6J-RC")
        (field (name "COPYRIGHT") "Copyright (C) 2022 Ultra Librarian. All rights reserved.")
      )
      (libsource (lib "78F5R6J-RC") (part "78F5R6J-RC"))
    )
    (comp (ref "L3")
      (value "2.7 uH")
      (footprint "IND_BOURNS_78F")
      (description "No Description Available")
      (fields
        (field (name "MANUFACTURER_PART_NUMBER") "78F5R6J-RC")
        (field (name "COPYRIGHT") "Copyright (C) 2022 Ultra Librarian. All rights reserved.")
      )
      (libsource (lib "78F5R6J-RC") (part "78F5R6J-RC"))
    )
    (comp (ref "P1") (value "VGA") (footprint "VGA_Conn") (libsource (lib "isa_svga-rescue") (part "DE15")))
    (comp (ref "P2")
      (value "UART IDC")
      (footprint "61201021621")
      (fields (field (name "MF") "{'manufacturer': u'Wurth Elektronik'}") (field (name "MP") "61201021621"))
      (libsource (lib "SnapEDA_Library") (part "61201021621"))
    )
    (comp (ref "P3")
      (value "FLOPPY")
      (footprint "Floppy Connector")
      (libsource (lib "isa_fdc-rescue") (part "CONN_17X2"))
    )
    (comp (ref "P4")
      (value "AUDIO_OUT")
      (footprint "Headphone")
      (libsource (lib "isa_opl2-rescue") (part "CONN_5"))
    )
    (comp (ref "P5")
      (value "RJMG1BD3B8K1ANR")
      (footprint "CONN_RJMG1BD3B8K1ANR")
      (description "1 Port RJ45 Magjack Connector Through Hole 10/100 Base-T, AutoMDIX")
      (fields (field (name "MF") "Amphenol ICC") (field (name "DIGI-KEY_PART_NUMBER") "RJMG1BD3B8K1ANR-ND"))
      (libsource (lib "RJMG1BD3B8K1ANR") (part "RJMG1BD3B8K1ANR"))
    )
    (comp (ref "Q1")
      (value "2N3904")
      (footprint "TO92127P495H495-3")
      (libsource (lib "2N3904") (part "2N3904"))
    )
    (comp (ref "R1")
      (value "100")
      (footprint "RES_ERJ6ENF1000V")
      (fields (field (name "MP") "ERJ6ENF1000V"))
      (libsource (lib "ERJ6ENF1000V") (part "ERJ6ENF1000V"))
    )
    (comp (ref "R2")
      (value "1k")
      (footprint "RESC2012X60N")
      (description "1 kOhms Â±1% 0.125W, 1/8W Chip Resistor 0805 (2012 Metric) Automotive AEC-Q200 Thick Film")
      (fields
        (field (name "MP") "AC0805FR-101KL")
        (field (name "DIGI-KEY_PART_NUMBER") "13-AC0805FR-101KLTR-ND")
      )
      (libsource (lib "AC0805FR-101KL") (part "AC0805FR-101KL"))
    )
    (comp (ref "R3")
      (value "150")
      (footprint "RESC2012X70N")
      (description "Res Thick Film 0805 150 Ohm 5% 0.125W(1/8W) Â}200ppm/ÂÂŽ Molded SMD Automotive T/R")
      (fields (field (name "MP") "ERJ-6GEYJ151V"))
      (libsource (lib "ERJ-6GEYJ151V") (part "ERJ-6GEYJ151V"))
    )
    (comp (ref "R4")
      (value "33")
      (footprint "RESC2012X65N")
      (fields (field (name "MP") "RMCF0805JT33R0"))
      (libsource (lib "RMCF0805JT33R0") (part "RMCF0805JT33R0"))
    )
    (comp (ref "R5")
      (value "33")
      (footprint "RESC2012X65N")
      (fields (field (name "MP") "RMCF0805JT33R0"))
      (libsource (lib "RMCF0805JT33R0") (part "RMCF0805JT33R0"))
    )
    (comp (ref "R6")
      (value "4.7k")
      (footprint "RESC2012X60N")
      (description "4.7 kOhms Â±1% 0.125W, 1/8W Chip Resistor 0805 _2012 Metric_ Moisture Resistant Thick Film")
      (fields (field (name "MF") "Yageo") (field (name "DIGI-KEY_PART_NUMBER") "311-4.70KCRCT-ND"))
      (libsource (lib "RC0805FR-074K7L") (part "RC0805FR-074K7L"))
    )
    (comp (ref "R7")
      (value "150")
      (footprint "RESC2012X70N")
      (description "Res Thick Film 0805 150 Ohm 5% 0.125W(1/8W) Â}200ppm/ÂÂŽ Molded SMD Automotive T/R")
      (fields (field (name "MP") "ERJ-6GEYJ151V"))
      (libsource (lib "ERJ-6GEYJ151V") (part "ERJ-6GEYJ151V"))
    )
    (comp (ref "R8")
      (value "150")
      (footprint "RESC2012X70N")
      (description "Res Thick Film 0805 150 Ohm 5% 0.125W(1/8W) Â}200ppm/ÂÂŽ Molded SMD Automotive T/R")
      (fields (field (name "MP") "ERJ-6GEYJ151V"))
      (libsource (lib "ERJ-6GEYJ151V") (part "ERJ-6GEYJ151V"))
    )
    (comp (ref "R9")
      (value "150")
      (footprint "RESC2012X70N")
      (description "Res Thick Film 0805 150 Ohm 5% 0.125W(1/8W) Â}200ppm/ÂÂŽ Molded SMD Automotive T/R")
      (fields (field (name "MP") "ERJ-6GEYJ151V"))
      (libsource (lib "ERJ-6GEYJ151V") (part "ERJ-6GEYJ151V"))
    )
    (comp (ref "R10")
      (value "4.7k")
      (footprint "RESC2012X60N")
      (description "4.7 kOhms Â±1% 0.125W, 1/8W Chip Resistor 0805 _2012 Metric_ Moisture Resistant Thick Film")
      (fields (field (name "MF") "Yageo") (field (name "DIGI-KEY_PART_NUMBER") "311-4.70KCRCT-ND"))
      (libsource (lib "RC0805FR-074K7L") (part "RC0805FR-074K7L"))
    )
    (comp (ref "R11")
      (value "4.7k")
      (footprint "RESC2012X60N")
      (description "4.7 kOhms Â±1% 0.125W, 1/8W Chip Resistor 0805 _2012 Metric_ Moisture Resistant Thick Film")
      (fields (field (name "MF") "Yageo") (field (name "DIGI-KEY_PART_NUMBER") "311-4.70KCRCT-ND"))
      (libsource (lib "RC0805FR-074K7L") (part "RC0805FR-074K7L"))
    )
    (comp (ref "R12")
      (value "4.7k")
      (footprint "RESC2012X60N")
      (description "4.7 kOhms Â±1% 0.125W, 1/8W Chip Resistor 0805 _2012 Metric_ Moisture Resistant Thick Film")
      (fields (field (name "MF") "Yageo") (field (name "DIGI-KEY_PART_NUMBER") "311-4.70KCRCT-ND"))
      (libsource (lib "RC0805FR-074K7L") (part "RC0805FR-074K7L"))
    )
    (comp (ref "R13")
      (value "4.7k")
      (footprint "RESC2012X60N")
      (description "4.7 kOhms Â±1% 0.125W, 1/8W Chip Resistor 0805 _2012 Metric_ Moisture Resistant Thick Film")
      (fields (field (name "MF") "Yageo") (field (name "DIGI-KEY_PART_NUMBER") "311-4.70KCRCT-ND"))
      (libsource (lib "RC0805FR-074K7L") (part "RC0805FR-074K7L"))
    )
    (comp (ref "R14")
      (value "4.7k")
      (footprint "RESC2012X60N")
      (description "4.7 kOhms Â±1% 0.125W, 1/8W Chip Resistor 0805 _2012 Metric_ Moisture Resistant Thick Film")
      (fields (field (name "MF") "Yageo") (field (name "DIGI-KEY_PART_NUMBER") "311-4.70KCRCT-ND"))
      (libsource (lib "RC0805FR-074K7L") (part "RC0805FR-074K7L"))
    )
    (comp (ref "R15")
      (value "4.7k")
      (footprint "RESC2012X60N")
      (description "4.7 kOhms Â±1% 0.125W, 1/8W Chip Resistor 0805 _2012 Metric_ Moisture Resistant Thick Film")
      (fields (field (name "MF") "Yageo") (field (name "DIGI-KEY_PART_NUMBER") "311-4.70KCRCT-ND"))
      (libsource (lib "RC0805FR-074K7L") (part "RC0805FR-074K7L"))
    )
    (comp (ref "R16")
      (value "4.7k")
      (footprint "RESC2012X60N")
      (description "4.7 kOhms Â±1% 0.125W, 1/8W Chip Resistor 0805 _2012 Metric_ Moisture Resistant Thick Film")
      (fields (field (name "MF") "Yageo") (field (name "DIGI-KEY_PART_NUMBER") "311-4.70KCRCT-ND"))
      (libsource (lib "RC0805FR-074K7L") (part "RC0805FR-074K7L"))
    )
    (comp (ref "R17")
      (value "2.2k")
      (footprint "RESC2012X60N")
      (description "AC0805 2,2K 5% 0,125W AUTOMO")
      (fields (field (name "MP") "AC0805JR-072K2L"))
      (libsource (lib "AC0805JR-072K2L") (part "AC0805JR-072K2L"))
    )
    (comp (ref "R18")
      (value "2.2k")
      (footprint "RESC2012X70N")
      (fields (field (name "MP") "ERJ-PB6B2201V"))
      (libsource (lib "ERJ-PB6B2201V") (part "ERJ-PB6B2201V"))
    )
    (comp (ref "R19")
      (value "2.2k")
      (footprint "RESC2012X70N")
      (fields (field (name "MP") "ERJ-PB6B2201V"))
      (libsource (lib "ERJ-PB6B2201V") (part "ERJ-PB6B2201V"))
    )
    (comp (ref "R20")
      (value "12K")
      (footprint "RESC2012X70N")
      (fields (field (name "MP") "ERJ-PB6B1202V"))
      (libsource (lib "ERJ-PB6B1202V") (part "ERJ-PB6B1202V"))
    )
    (comp (ref "R21")
      (value "10k")
      (footprint "RESC2012X70N")
      (fields
        (field (name "MP") "ERJ-PB6B1002V")
        (field (name "MF") "Panasonic Electronic")
        (field (name "DIGI-KEY_PART_NUMBER") "P20708CT-ND")
      )
      (libsource (lib "ERJ-PB6B1002V") (part "ERJ-PB6B1002V"))
    )
    (comp (ref "R22")
      (value "2.2k")
      (footprint "RESC2012X70N")
      (fields (field (name "MP") "ERJ-PB6B2201V"))
      (libsource (lib "ERJ-PB6B2201V") (part "ERJ-PB6B2201V"))
    )
    (comp (ref "R23")
      (value "2.2k")
      (footprint "RESC2012X70N")
      (fields (field (name "MP") "ERJ-PB6B2201V"))
      (libsource (lib "ERJ-PB6B2201V") (part "ERJ-PB6B2201V"))
    )
    (comp (ref "R24")
      (value "1.5k")
      (footprint "RESC2012X70N")
      (description "Res Thick Film 0805 1.5K Ohm 0.1% 0.25W(1/4W) Â±50ppm/C Pad SMD Automotive T/R")
      (fields (field (name "MP") "ERJ-PB6B1501V"))
      (libsource (lib "ERJ-PB6B1501V") (part "ERJ-PB6B1501V"))
    )
    (comp (ref "R25")
      (value "10k")
      (footprint "RESC2012X70N")
      (fields
        (field (name "MP") "ERJ-PB6B1002V")
        (field (name "MF") "Panasonic Electronic")
        (field (name "DIGI-KEY_PART_NUMBER") "P20708CT-ND")
      )
      (libsource (lib "ERJ-PB6B1002V") (part "ERJ-PB6B1002V"))
    )
    (comp (ref "R26")
      (value "2.2k")
      (footprint "RESC2012X70N")
      (fields (field (name "MP") "ERJ-PB6B2201V"))
      (libsource (lib "ERJ-PB6B2201V") (part "ERJ-PB6B2201V"))
    )
    (comp (ref "R27")
      (value "2.2k")
      (footprint "RESC2012X70N")
      (fields (field (name "MP") "ERJ-PB6B2201V"))
      (libsource (lib "ERJ-PB6B2201V") (part "ERJ-PB6B2201V"))
    )
    (comp (ref "R28")
      (value "10k")
      (footprint "RESC2012X70N")
      (fields
        (field (name "MP") "ERJ-PB6B1002V")
        (field (name "MF") "Panasonic Electronic")
        (field (name "DIGI-KEY_PART_NUMBER") "P20708CT-ND")
      )
      (libsource (lib "ERJ-PB6B1002V") (part "ERJ-PB6B1002V"))
    )
    (comp (ref "R29")
      (value "8.2k")
      (footprint "RESC2012X70N")
      (fields (field (name "MP") "ERJ-PB6B8201V"))
      (libsource (lib "ERJ-PB6B8201V") (part "ERJ-PB6B8201V"))
    )
    (comp (ref "R30")
      (value "10")
      (footprint "RESC2012X70N")
      (fields (field (name "MP") "ERJ-PB6B8201V"))
      (libsource (lib "ERJ-PB6B8201V") (part "ERJ-PB6B8201V"))
    )
    (comp (ref "R31")
      (value "10k")
      (footprint "RESC2012X70N")
      (fields
        (field (name "MP") "ERJ-PB6B1002V")
        (field (name "MF") "Panasonic Electronic")
        (field (name "DIGI-KEY_PART_NUMBER") "P20708CT-ND")
      )
      (libsource (lib "ERJ-PB6B1002V") (part "ERJ-PB6B1002V"))
    )
    (comp (ref "R32")
      (value "10")
      (footprint "RESC2012X70N")
      (fields (field (name "MP") "ERJ-PB6B8201V"))
      (libsource (lib "ERJ-PB6B8201V") (part "ERJ-PB6B8201V"))
    )
    (comp (ref "R33")
      (value "10")
      (footprint "RESC2012X70N")
      (fields (field (name "MP") "ERJ-PB6B8201V"))
      (libsource (lib "ERJ-PB6B8201V") (part "ERJ-PB6B8201V"))
    )
    (comp (ref "R34")
      (value "1M")
      (footprint "RESC2012X70N")
      (fields (field (name "MP") "ERJ-PB6B8201V"))
      (libsource (lib "ERJ-PB6B8201V") (part "ERJ-PB6B8201V"))
    )
    (comp (ref "R35")
      (value "470")
      (footprint "RESC2012X70N")
      (fields (field (name "MP") "ERJ-PB6B4700V"))
      (libsource (lib "ERJ-PB6B4700V") (part "ERJ-PB6B4700V"))
    )
    (comp (ref "R36")
      (value "470")
      (footprint "RESC2012X70N")
      (fields (field (name "MP") "ERJ-PB6B4700V"))
      (libsource (lib "ERJ-PB6B4700V") (part "ERJ-PB6B4700V"))
    )
    (comp (ref "R37")
      (value "27k")
      (footprint "RESC2012X60N")
      (description "Res Thick Film 0805 27K Ohm 1% 0.25W(1/4W) Â±100ppm/Â°C Sulfur Resistant Pad SMD Automotive T/R")
      (fields (field (name "MP") "RK73H2ARTTD2702F") (field (name "MF") "{'manufacturer': u'KOA Speer'}"))
      (libsource (lib "SnapEDA_Library") (part "RK73H2ARTTD2702F"))
    )
    (comp (ref "R38")
      (value "200")
      (footprint "RESC2012X70N")
      (description "Res Thick Film 0805 200 Ohm 0.1% 0.25W(1/4W) Â±50ppm/C Pad SMD Automotive T/R")
      (fields (field (name "MP") "ERJ-PB6B2000V") (field (name "MF") "{'manufacturer': u'Panasonic'}"))
      (libsource (lib "SnapEDA_Library") (part "ERJ-PB6B2000V"))
    )
    (comp (ref "RN1")
      (value "10k")
      (footprint "RESCAXS80P320X160X60-8N")
      (fields (field (name "MP") "EXB-38V103JV") (field (name "MF") "{'manufacturer': u'Panasonic'}"))
      (libsource (lib "SixPakUltra_Mac") (part "EXB-38V103JV"))
    )
    (comp (ref "RN2")
      (value "10k")
      (footprint "RESCAXS80P320X160X60-8N")
      (fields (field (name "MP") "EXB-38V103JV") (field (name "MF") "{'manufacturer': u'Panasonic'}"))
      (libsource (lib "SixPakUltra_Mac") (part "EXB-38V103JV"))
    )
    (comp (ref "RN3")
      (value "10k")
      (footprint "RESCAXS80P320X160X60-8N")
      (fields (field (name "MP") "EXB-38V103JV") (field (name "MF") "{'manufacturer': u'Panasonic'}"))
      (libsource (lib "SixPakUltra_Mac") (part "EXB-38V103JV"))
    )
    (comp (ref "RN4")
      (value "10k")
      (footprint "RESCAXS80P320X160X60-8N")
      (fields (field (name "MP") "EXB-38V103JV") (field (name "MF") "{'manufacturer': u'Panasonic'}"))
      (libsource (lib "SixPakUltra_Mac") (part "EXB-38V103JV"))
    )
    (comp (ref "RN5")
      (value "10k")
      (footprint "SOIC127P762X240-16N")
      (description "Res Thick Film NET 68K Ohm 2% 1.28W Â±100ppm/C ISOL Molded 16-Pin SOM Gull Wing SMD Automotive T/R")
      (fields (field (name "MP") "4816P-1-103LF") (field (name "MF") "{'manufacturer': u'Bourns'}"))
      (libsource (lib "SixPakUltra_Mac") (part "4816P-1-103LF"))
    )
    (comp (ref "RR1")
      (value "1k")
      (footprint "Res Network RR2 Floppy")
      (libsource (lib "isa_fdc-rescue") (part "RR5"))
    )
    (comp (ref "RR2")
      (value "10k")
      (footprint "Res Network RR1 Floppy ROM")
      (libsource (lib "isa_fdc-rescue") (part "RR9"))
    )
    (comp (ref "RV1")
      (value "10k")
      (footprint "Potentiometer")
      (libsource (lib "isa_opl2-rescue") (part "POT"))
    )
    (comp (ref "SW1")
      (value "1-1825058-9")
      (footprint "SW_1-1825058-9")
      (description "AD Series 8 Position SPST Extended Slide Non Sealed 2.54 mm Pitch SMT DIP Switch")
      (fields (field (name "MF") "TE Connectivity"))
      (libsource (lib "1-1825058-9") (part "1-1825058-9"))
    )
    (comp (ref "SW2")
      (value "1-1825058-9")
      (footprint "SW_1-1825058-9")
      (description "AD Series 8 Position SPST Extended Slide Non Sealed 2.54 mm Pitch SMT DIP Switch")
      (fields (field (name "MF") "TE Connectivity"))
      (libsource (lib "1-1825058-9") (part "1-1825058-9"))
    )
    (comp (ref "SW3")
      (value "1825059-1")
      (footprint "SW_1825059-1")
      (description "SPST Flush Slide Sealed 2.54 mm Pitch Surface Mount DIP Switch")
      (fields (field (name "MF") "{'manufacturer': u'TE Connectivity'}"))
      (libsource (lib "SixPakUltra_Mac") (part "1825059-1"))
    )
    (comp (ref "SW4")
      (value "1825059-1")
      (footprint "SW_1825059-1")
      (description "SPST Flush Slide Sealed 2.54 mm Pitch Surface Mount DIP Switch")
      (fields (field (name "MF") "{'manufacturer': u'TE Connectivity'}"))
      (libsource (lib "SixPakUltra_Mac") (part "1825059-1"))
    )
    (comp (ref "SW5")
      (value "1-1825059-7")
      (footprint "SW_1-1825059-7")
      (description "SPST Flush Slide Sealed 2.54 mm Pitch Surface Mount DIP Switch")
      (fields (field (name "MF") "{'manufacturer': u'TE Connectivity'}"))
      (libsource (lib "SixPakUltra_Mac") (part "1-1825059-7"))
    )
    (comp (ref "SW6")
      (value "2-1825059-3")
      (footprint "SW_2-1825059-3")
      (description "SPST Flush Slide Sealed 2.54 mm Pitch Surface Mount DIP Switch")
      (fields (field (name "MF") "{'manufacturer': u'TE Connectivity'}"))
      (libsource (lib "SixPakUltra_Mac") (part "2-1825059-3"))
    )
    (comp (ref "SW7")
      (value "4-1825059-1")
      (footprint "SW_4-1825059-1")
      (description "SPST Flush Slide Sealed 2.54 mm Pitch Surface Mount DIP Switch")
      (fields (field (name "MF") "{'manufacturer': u'TE Connectivity'}"))
      (libsource (lib "SixPakUltra_Mac") (part "4-1825059-1"))
    )
    (comp (ref "SW8")
      (value "DS04-254-2-06BK-SMT-TR")
      (footprint "SW_DS04-254-2-06BK-SMT-TR")
      (fields (field (name "MF") "{'manufacturer': u'CUI Devices'}"))
      (libsource (lib "SixPakUltra_Mac") (part "DS04-254-2-06BK-SMT-TR"))
    )
    (comp (ref "U1")
      (value "TVGA9000I")
      (footprint "TVGA9000")
      (libsource (lib "isa_svga-rescue") (part "TVGA9000I"))
    )
    (comp (ref "U2")
      (value "MT4C4256")
      (footprint "MT4C4256")
      (libsource (lib "isa_svga-rescue") (part "MT4C4256"))
    )
    (comp (ref "U3")
      (value "MT4C4256")
      (footprint "MT4C4256")
      (libsource (lib "isa_svga-rescue") (part "MT4C4256"))
    )
    (comp (ref "U4")
      (value "MT4C4256")
      (footprint "MT4C4256")
      (libsource (lib "isa_svga-rescue") (part "MT4C4256"))
    )
    (comp (ref "U5")
      (value "MT4C4256")
      (footprint "MT4C4256")
      (libsource (lib "isa_svga-rescue") (part "MT4C4256"))
    )
    (comp (ref "U6")
      (value "27C256")
      (footprint "27C256")
      (libsource (lib "isa_svga-rescue") (part "27C256"))
    )
    (comp (ref "U7")
      (value "SN74ALS138ADR")
      (footprint "SOIC127P600X175-16N")
      (libsource (lib "SN74ALS138ADR") (part "SN74ALS138ADR"))
    )
    (comp (ref "U8")
      (value "SN74ALS138ADR")
      (footprint "SOIC127P600X175-16N")
      (libsource (lib "SN74ALS138ADR") (part "SN74ALS138ADR"))
    )
    (comp (ref "U9")
      (value "16550-PLCC")
      (footprint "16550_PLCC")
      (libsource (lib "isa_fdc-rescue") (part "16550-PLCC"))
    )
    (comp (ref "U10")
      (value "1.8432MHz")
      (footprint "Osc_Socket 4PIN")
      (libsource (lib "isa_fdc-rescue") (part "OSC"))
    )
    (comp (ref "U11")
      (value "GD75232")
      (footprint "GD75232")
      (libsource (lib "isa_fdc-rescue") (part "GD75232"))
    )
    (comp (ref "U12")
      (value "82077AA")
      (footprint "82077AA")
      (libsource (lib "isa_fdc-rescue") (part "82077AA"))
    )
    (comp (ref "U13")
      (value "SN74LS688DW")
      (footprint "SOIC127P1030X265-20N")
      (libsource (lib "SN74LS688DW") (part "SN74LS688DW"))
    )
    (comp (ref "U14") (value "28C64") (footprint "27C256") (libsource (lib "isa_fdc-rescue") (part "28C64")))
    (comp (ref "U15")
      (value "YM3812")
      (footprint "YM3812")
      (libsource (lib "controllers-sergey") (part "YM3812"))
    )
    (comp (ref "U16")
      (value "SN74ALS138ADR")
      (footprint "SOIC127P600X175-16N")
      (libsource (lib "SN74ALS138ADR") (part "SN74ALS138ADR"))
    )
    (comp (ref "U17")
      (value "SN74ALS138ADR")
      (footprint "SOIC127P600X175-16N")
      (libsource (lib "SN74ALS138ADR") (part "SN74ALS138ADR"))
    )
    (comp (ref "U18")
      (value "SN74LS245DW")
      (footprint "SOIC127P1030X265-20N")
      (description "Octal bus transceivers 20-SOIC 0 to 70")
      (fields (field (name "MF") "Texas Instruments") (field (name "DIGI-KEY_PART_NUMBER") "296-1214-2-ND"))
      (libsource (lib "SN74LS245DW") (part "SN74LS245DW"))
    )
    (comp (ref "U19")
      (value "SN74LS04DR")
      (footprint "SOIC127P600X175-14N")
      (description "6-ch, 4.75-V to 5.25-V bipolar inverters")
      (fields (field (name "MF") "Texas Instruments"))
      (libsource (lib "SN74LS04DR") (part "SN74LS04DR"))
    )
    (comp (ref "U20")
      (value "SN74LS74AD")
      (footprint "SOIC127P600X175-14N")
      (description "Dual D-type pos.-edge-triggered flip-flops with preset and clear 14-SOIC 0 to 70")
      (fields (field (name "MF") "Texas Instruments"))
      (libsource (lib "SN74LS74AD") (part "SN74LS74AD"))
    )
    (comp (ref "U21")
      (value "Y3014B")
      (footprint "Y3014B")
      (libsource (lib "controllers-sergey") (part "Y3014B"))
    )
    (comp (ref "U22")
      (value "RC4136N")
      (footprint "DIP794W45P254L1969H508Q14")
      (description "Quad general purpose 30V operational amplifier 14-PDIP 0 to 70")
      (fields (field (name "MF") "Texas Instruments"))
      (libsource (lib "RC4136N") (part "RC4136N"))
    )
    (comp (ref "U23")
      (value "LM386MX-1/NOPB")
      (footprint "SOIC127P599X175-8N")
      (description "Wide Input Voltage Low Power Audio Amplifier with Internal Gain")
      (fields (field (name "MF") "Texas Instruments"))
      (libsource (lib "LM386MX-1_NOPB") (part "LM386MX-1/NOPB"))
    )
    (comp (ref "U24")
      (value "RTL8019AS")
      (footprint "Ethernet Controller")
      (libsource (lib "my_components") (part "RTL8019AS"))
    )
    (comp (ref "U25")
      (value "93LC46C")
      (footprint "93LC46C")
      (libsource (lib "Memory_EEPROM") (part "93LCxxC"))
    )
    (comp (ref "U26")
      (value "SST39SF040")
      (footprint "SST39LF040")
      (libsource (lib "my_components") (part "SST39SF040"))
    )
    (comp (ref "U27")
      (value "DS12885")
      (footprint "DIP1524W46P254L3226H508Q24")
      (fields (field (name "MF") "{'manufacturer': u'Maxim Integrated'}"))
      (libsource (lib "SixPakUltra_Mac") (part "DS12885"))
    )
    (comp (ref "U28")
      (value "SN74LS688DW")
      (footprint "SOIC127P1030X265-20N")
      (fields (field (name "MF") "{'manufacturer': u'Texas Instruments'}"))
      (libsource (lib "SixPakUltra_Mac") (part "SN74LS688DW"))
    )
    (comp (ref "U29")
      (value "SN74HCT139D")
      (footprint "SOIC127P600X175-16N")
      (fields (field (name "MF") "{'manufacturer': u'Texas Instruments'}"))
      (libsource (lib "SixPakUltra_Mac") (part "SN74HCT139D"))
    )
    (comp (ref "U30")
      (value "CD74HC04M")
      (footprint "SOIC127P600X175-14N")
      (fields (field (name "MF") "{'manufacturer': u'Texas Instruments'}"))
      (libsource (lib "SixPakUltra_Mac") (part "CD74HC04M"))
    )
    (comp (ref "X1")
      (value "ABM3-40.000MHZ-B2-T")
      (footprint "XTAL_ABM3-40.000MHZ-B2-T")
      (libsource (lib "ABM3-40.000MHZ-B2-T") (part "ABM3-40.000MHZ-B2-T"))
    )
    (comp (ref "X2")
      (value "24MHz")
      (footprint "XTAL_ECS-240-12-20A-TR")
      (description "SMD CRYSTAL")
      (fields (field (name "MP") "ECS-240-12-20A-TR") (field (name "MF") "{'manufacturer': u'ECS Inc.'}"))
      (libsource (lib "SnapEDA_Library") (part "ECS-240-12-20A-TR"))
    )
    (comp (ref "X3")
      (value "20MHz")
      (footprint "XTAL_ABM3-20.000MHZ-B2-T")
      (description "20 MHz Â±20ppm Crystal 18pF 30 Ohms 2-SMD, No Lead")
      (fields (field (name "MP") "ABM3-20.000MHZ-B2-T") (field (name "MF") "Abracon"))
      (libsource (lib "ABM3-20.000MHZ-B2-T") (part "ABM3-20.000MHZ-B2-T"))
    )
    (comp (ref "X4")
      (value "32.768K")
      (footprint "XTAL_MS1V-T1K-32.768KHZ-7PF-20PPM-TA-QC-AU")
      (description "Tuning Fork Crystal 30 kHz â€“ 200 kHz")
      (fields
        (field (name "MP") "MS1V-T1K-32.768KHZ-7PF-20PPM-TA-QC-AU")
        (field (name "MF") "{'manufacturer': u'Micro Crystal'}")
      )
      (libsource (lib "SixPakUltra_Mac") (part "MS1V-T1K-32.768KHZ-7PF-20PPM-TA-QC-AU"))
    )
  )
  (nets
    (net (code "1") (name "+12") (class "Default")
      (node (ref "BUS1") (pin "9") (pinfunction "+12V_9") (pintype "passive"))
      (node (ref "C48") (pin "1") (pinfunction "1_1") (pintype "passive"))
      (node (ref "C49") (pin "1") (pinfunction "1_1") (pintype "passive"))
      (node (ref "C52") (pin "1") (pinfunction "1_1") (pintype "passive"))
      (node (ref "CD42") (pin "1") (pinfunction "1_1") (pintype "passive"))
      (node (ref "CD43") (pin "1") (pinfunction "1_1") (pintype "passive"))
      (node (ref "U11") (pin "1") (pinfunction "VDD_1") (pintype "passive"))
      (node (ref "U22") (pin "11") (pinfunction "VCC+_11") (pintype "power_in"))
      (node (ref "U23") (pin "6") (pinfunction "VS_6") (pintype "power_in"))
    )
    (net (code "2") (name "/A0") (class "Default")
      (node (ref "BUS1") (pin "62") (pinfunction "SA0_62") (pintype "passive"))
      (node (ref "U1") (pin "135") (pinfunction "SA0_135") (pintype "passive"))
      (node (ref "U12") (pin "7") (pinfunction "A0_7") (pintype "passive"))
      (node (ref "U14") (pin "10") (pinfunction "A0_10") (pintype "passive"))
      (node (ref "U15") (pin "4") (pinfunction "A0_4") (pintype "passive"))
      (node (ref "U24") (pin "5") (pinfunction "SA0_5") (pintype "passive"))
      (node (ref "U26") (pin "12") (pinfunction "A0_12") (pintype "passive"))
      (node (ref "U29") (pin "13") (pinfunction "2B_13") (pintype "input"))
      (node (ref "U29") (pin "3") (pinfunction "1B_3") (pintype "input"))
      (node (ref "U9") (pin "31") (pinfunction "A0_31") (pintype "passive"))
    )
    (net (code "3") (name "/A1") (class "Default")
      (node (ref "BUS1") (pin "61") (pinfunction "SA1_61") (pintype "passive"))
      (node (ref "U1") (pin "136") (pinfunction "SA1_136") (pintype "passive"))
      (node (ref "U12") (pin "8") (pinfunction "A1_8") (pintype "passive"))
      (node (ref "U14") (pin "9") (pinfunction "A1_9") (pintype "passive"))
      (node (ref "U17") (pin "1") (pinfunction "A_1") (pintype "input"))
      (node (ref "U24") (pin "7") (pinfunction "SA1_7") (pintype "passive"))
      (node (ref "U26") (pin "11") (pinfunction "A1_11") (pintype "passive"))
      (node (ref "U6") (pin "10") (pinfunction "A0_10") (pintype "passive"))
      (node (ref "U9") (pin "30") (pinfunction "A1_30") (pintype "passive"))
    )
    (net (code "4") (name "/A2") (class "Default")
      (node (ref "BUS1") (pin "60") (pinfunction "SA2_60") (pintype "passive"))
      (node (ref "U1") (pin "137") (pinfunction "SA2_137") (pintype "passive"))
      (node (ref "U12") (pin "10") (pinfunction "A2_10") (pintype "passive"))
      (node (ref "U14") (pin "8") (pinfunction "A2_8") (pintype "passive"))
      (node (ref "U17") (pin "2") (pinfunction "B_2") (pintype "input"))
      (node (ref "U24") (pin "8") (pinfunction "SA2_8") (pintype "passive"))
      (node (ref "U26") (pin "10") (pinfunction "A2_10") (pintype "passive"))
      (node (ref "U28") (pin "2") (pinfunction "P0_2") (pintype "input"))
      (node (ref "U6") (pin "9") (pinfunction "A1_9") (pintype "passive"))
      (node (ref "U9") (pin "29") (pinfunction "A2_29") (pintype "passive"))
    )
    (net (code "5") (name "/A3") (class "Default")
      (node (ref "BUS1") (pin "59") (pinfunction "SA3_59") (pintype "passive"))
      (node (ref "U1") (pin "138") (pinfunction "SA3_138") (pintype "passive"))
      (node (ref "U14") (pin "7") (pinfunction "A3_7") (pintype "passive"))
      (node (ref "U17") (pin "6") (pinfunction "G1_6") (pintype "input"))
      (node (ref "U24") (pin "9") (pinfunction "SA3_9") (pintype "passive"))
      (node (ref "U26") (pin "9") (pinfunction "A3_9") (pintype "passive"))
      (node (ref "U28") (pin "4") (pinfunction "P1_4") (pintype "input"))
      (node (ref "U6") (pin "8") (pinfunction "A2_8") (pintype "passive"))
      (node (ref "U7") (pin "3") (pinfunction "C_3") (pintype "input"))
    )
    (net (code "6") (name "/A4") (class "Default")
      (node (ref "BUS1") (pin "58") (pinfunction "SA4_58") (pintype "passive"))
      (node (ref "U1") (pin "139") (pinfunction "SA4_139") (pintype "passive"))
      (node (ref "U14") (pin "6") (pinfunction "A4_6") (pintype "passive"))
      (node (ref "U16") (pin "1") (pinfunction "A_1") (pintype "input"))
      (node (ref "U24") (pin "10") (pinfunction "SA4_10") (pintype "passive"))
      (node (ref "U26") (pin "8") (pinfunction "A4_8") (pintype "passive"))
      (node (ref "U28") (pin "6") (pinfunction "P2_6") (pintype "input"))
      (node (ref "U6") (pin "7") (pinfunction "A3_7") (pintype "passive"))
      (node (ref "U7") (pin "2") (pinfunction "B_2") (pintype "input"))
    )
    (net (code "7") (name "/A5") (class "Default")
      (node (ref "BUS1") (pin "57") (pinfunction "SA5_57") (pintype "passive"))
      (node (ref "U1") (pin "140") (pinfunction "SA5_140") (pintype "passive"))
      (node (ref "U14") (pin "5") (pinfunction "A5_5") (pintype "passive"))
      (node (ref "U17") (pin "3") (pinfunction "C_3") (pintype "input"))
      (node (ref "U24") (pin "11") (pinfunction "SA5_11") (pintype "passive"))
      (node (ref "U26") (pin "7") (pinfunction "A5_7") (pintype "passive"))
      (node (ref "U28") (pin "8") (pinfunction "P3_8") (pintype "input"))
      (node (ref "U6") (pin "6") (pinfunction "A4_6") (pintype "passive"))
      (node (ref "U7") (pin "6") (pinfunction "G1_6") (pintype "input"))
    )
    (net (code "8") (name "/A6") (class "Default")
      (node (ref "BUS1") (pin "56") (pinfunction "SA6_56") (pintype "passive"))
      (node (ref "U1") (pin "141") (pinfunction "SA6_141") (pintype "passive"))
      (node (ref "U14") (pin "4") (pinfunction "A6_4") (pintype "passive"))
      (node (ref "U17") (pin "5") (pinfunction "~{G2B}_5") (pintype "input"))
      (node (ref "U24") (pin "12") (pinfunction "SA6_12") (pintype "passive"))
      (node (ref "U26") (pin "6") (pinfunction "A6_6") (pintype "passive"))
      (node (ref "U28") (pin "11") (pinfunction "P4_11") (pintype "input"))
      (node (ref "U6") (pin "5") (pinfunction "A5_5") (pintype "passive"))
      (node (ref "U8") (pin "1") (pinfunction "A_1") (pintype "input"))
    )
    (net (code "9") (name "/A7") (class "Default")
      (node (ref "BUS1") (pin "55") (pinfunction "SA7_55") (pintype "passive"))
      (node (ref "U1") (pin "142") (pinfunction "SA7_142") (pintype "passive"))
      (node (ref "U14") (pin "3") (pinfunction "A7_3") (pintype "passive"))
      (node (ref "U16") (pin "2") (pinfunction "B_2") (pintype "input"))
      (node (ref "U24") (pin "13") (pinfunction "SA7_13") (pintype "passive"))
      (node (ref "U26") (pin "5") (pinfunction "A7_5") (pintype "passive"))
      (node (ref "U28") (pin "13") (pinfunction "P5_13") (pintype "input"))
      (node (ref "U6") (pin "4") (pinfunction "A6_4") (pintype "passive"))
      (node (ref "U8") (pin "2") (pinfunction "B_2") (pintype "input"))
    )
    (net (code "10") (name "/A8") (class "Default")
      (node (ref "BUS1") (pin "54") (pinfunction "SA8_54") (pintype "passive"))
      (node (ref "U1") (pin "144") (pinfunction "SA8_144") (pintype "passive"))
      (node (ref "U14") (pin "25") (pinfunction "A8_25") (pintype "passive"))
      (node (ref "U16") (pin "3") (pinfunction "C_3") (pintype "input"))
      (node (ref "U24") (pin "15") (pinfunction "SA8_15") (pintype "passive"))
      (node (ref "U26") (pin "27") (pinfunction "A8_27") (pintype "passive"))
      (node (ref "U28") (pin "15") (pinfunction "P6_15") (pintype "input"))
      (node (ref "U6") (pin "3") (pinfunction "A7_3") (pintype "passive"))
      (node (ref "U7") (pin "1") (pinfunction "A_1") (pintype "input"))
    )
    (net (code "11") (name "/A9") (class "Default")
      (node (ref "BUS1") (pin "53") (pinfunction "SA9_53") (pintype "passive"))
      (node (ref "U1") (pin "145") (pinfunction "SA9_145") (pintype "passive"))
      (node (ref "U14") (pin "24") (pinfunction "A9_24") (pintype "passive"))
      (node (ref "U16") (pin "6") (pinfunction "G1_6") (pintype "input"))
      (node (ref "U24") (pin "16") (pinfunction "SA9_16") (pintype "passive"))
      (node (ref "U26") (pin "26") (pinfunction "A9_26") (pintype "passive"))
      (node (ref "U28") (pin "17") (pinfunction "P7_17") (pintype "input"))
      (node (ref "U6") (pin "25") (pinfunction "A8_25") (pintype "passive"))
      (node (ref "U8") (pin "3") (pinfunction "C_3") (pintype "input"))
    )
    (net (code "12") (name "/A10") (class "Default")
      (node (ref "BUS1") (pin "52") (pinfunction "SA10_52") (pintype "passive"))
      (node (ref "U1") (pin "146") (pinfunction "SA10_146") (pintype "passive"))
      (node (ref "U14") (pin "21") (pinfunction "A10_21") (pintype "passive"))
      (node (ref "U24") (pin "18") (pinfunction "SA10_18") (pintype "passive"))
      (node (ref "U26") (pin "23") (pinfunction "A10_23") (pintype "passive"))
      (node (ref "U6") (pin "24") (pinfunction "A9_24") (pintype "passive"))
    )
    (net (code "13") (name "/A11") (class "Default")
      (node (ref "BUS1") (pin "51") (pinfunction "SA11_51") (pintype "passive"))
      (node (ref "U1") (pin "147") (pinfunction "SA11_147") (pintype "passive"))
      (node (ref "U14") (pin "23") (pinfunction "A11_23") (pintype "passive"))
      (node (ref "U24") (pin "19") (pinfunction "SA11_19") (pintype "passive"))
      (node (ref "U26") (pin "25") (pinfunction "A11_25") (pintype "passive"))
      (node (ref "U6") (pin "21") (pinfunction "A10_21") (pintype "passive"))
    )
    (net (code "14") (name "/A12") (class "Default")
      (node (ref "BUS1") (pin "50") (pinfunction "SA12_50") (pintype "passive"))
      (node (ref "U1") (pin "148") (pinfunction "SA12_148") (pintype "passive"))
      (node (ref "U14") (pin "2") (pinfunction "A12_2") (pintype "passive"))
      (node (ref "U24") (pin "20") (pinfunction "SA12_20") (pintype "passive"))
      (node (ref "U26") (pin "4") (pinfunction "A12_4") (pintype "passive"))
      (node (ref "U6") (pin "23") (pinfunction "A11_23") (pintype "passive"))
    )
    (net (code "15") (name "/A13") (class "Default")
      (node (ref "BUS1") (pin "49") (pinfunction "SA13_49") (pintype "passive"))
      (node (ref "U1") (pin "149") (pinfunction "SA13_149") (pintype "passive"))
      (node (ref "U13") (pin "15") (pinfunction "P6_15") (pintype "input"))
      (node (ref "U24") (pin "21") (pinfunction "SA13_21") (pintype "passive"))
      (node (ref "U26") (pin "28") (pinfunction "A13_28") (pintype "passive"))
      (node (ref "U6") (pin "2") (pinfunction "A12_2") (pintype "passive"))
    )
    (net (code "16") (name "/A14") (class "Default")
      (node (ref "BUS1") (pin "48") (pinfunction "SA14_48") (pintype "passive"))
      (node (ref "U1") (pin "150") (pinfunction "SA14_150") (pintype "passive"))
      (node (ref "U13") (pin "13") (pinfunction "P5_13") (pintype "input"))
      (node (ref "U24") (pin "22") (pinfunction "SA14_22") (pintype "passive"))
      (node (ref "U6") (pin "26") (pinfunction "A13_26") (pintype "passive"))
    )
    (net (code "17") (name "/A15") (class "Default")
      (node (ref "BUS1") (pin "47") (pinfunction "SA15_47") (pintype "passive"))
      (node (ref "U1") (pin "151") (pinfunction "SA15_151") (pintype "passive"))
      (node (ref "U13") (pin "11") (pinfunction "P4_11") (pintype "input"))
      (node (ref "U24") (pin "23") (pinfunction "SA15_23") (pintype "passive"))
    )
    (net (code "18") (name "/A16") (class "Default")
      (node (ref "BUS1") (pin "46") (pinfunction "SA16_46") (pintype "passive"))
      (node (ref "U1") (pin "152") (pinfunction "SA16_152") (pintype "passive"))
      (node (ref "U13") (pin "8") (pinfunction "P3_8") (pintype "input"))
      (node (ref "U24") (pin "24") (pinfunction "SA16_24") (pintype "passive"))
    )
    (net (code "19") (name "/A17") (class "Default")
      (node (ref "BUS1") (pin "45") (pinfunction "SA17_45") (pintype "passive"))
      (node (ref "U1") (pin "113") (pinfunction "SA17(LA17)_113") (pintype "passive"))
      (node (ref "U13") (pin "6") (pinfunction "P2_6") (pintype "input"))
      (node (ref "U24") (pin "25") (pinfunction "SA17_25") (pintype "passive"))
    )
    (net (code "20") (name "/A18") (class "Default")
      (node (ref "BUS1") (pin "44") (pinfunction "SA18_44") (pintype "passive"))
      (node (ref "U1") (pin "114") (pinfunction "SA18(LA18)_114") (pintype "passive"))
      (node (ref "U13") (pin "4") (pinfunction "P1_4") (pintype "input"))
      (node (ref "U24") (pin "26") (pinfunction "SA18_26") (pintype "passive"))
    )
    (net (code "21") (name "/A19") (class "Default")
      (node (ref "BUS1") (pin "43") (pinfunction "SA19_43") (pintype "passive"))
      (node (ref "U1") (pin "115") (pinfunction "SA19(LA19)_115") (pintype "passive"))
      (node (ref "U13") (pin "2") (pinfunction "P0_2") (pintype "input"))
      (node (ref "U24") (pin "27") (pinfunction "SA19_27") (pintype "passive"))
    )
    (net (code "22") (name "/AEN") (class "Default")
      (node (ref "BUS1") (pin "42") (pinfunction "AEN_42") (pintype "passive"))
      (node (ref "U1") (pin "22") (pinfunction "AEN_22") (pintype "passive"))
      (node (ref "U16") (pin "4") (pinfunction "~{G2A}_4") (pintype "input"))
      (node (ref "U24") (pin "34") (pinfunction "AEN_34") (pintype "passive"))
      (node (ref "U28") (pin "1") (pinfunction "~{G}_1") (pintype "input"))
      (node (ref "U7") (pin "4") (pinfunction "~{G2A}_4") (pintype "input"))
    )
    (net (code "23") (name "/AMP_OUT") (class "Default")
      (node (ref "C42") (pin "1") (pinfunction "1_1") (pintype "passive"))
      (node (ref "C43") (pin "P") (pinfunction "P_P") (pintype "passive"))
      (node (ref "U23") (pin "5") (pinfunction "VOUT_5") (pintype "output"))
    )
    (net (code "24") (name "/AUI") (class "Default")
      (node (ref "RN4") (pin "1") (pinfunction "1_1") (pintype "passive"))
      (node (ref "U24") (pin "64") (pinfunction "AUI_64") (pintype "passive"))
    )
    (net (code "25") (name "/AVDD1") (class "Default")
      (node (ref "C11") (pin "1") (pinfunction "1_1") (pintype "passive"))
      (node (ref "C12") (pin "1") (pinfunction "1_1") (pintype "passive"))
      (node (ref "C16") (pin "2") (pinfunction "2_2") (pintype "passive"))
      (node (ref "L1") (pin "1") (pinfunction "1_1") (pintype "passive"))
      (node (ref "U1") (pin "124") (pinfunction "AVDD1_124") (pintype "passive"))
    )
    (net (code "26") (name "/AVDD2") (class "Default")
      (node (ref "C13") (pin "1") (pinfunction "1_1") (pintype "passive"))
      (node (ref "C14") (pin "1") (pinfunction "1_1") (pintype "passive"))
      (node (ref "L2") (pin "1") (pinfunction "1_1") (pintype "passive"))
      (node (ref "U1") (pin "13") (pinfunction "AVDD2_13") (pintype "passive"))
      (node (ref "U1") (pin "6") (pinfunction "AVDD2_6") (pintype "passive"))
    )
    (net (code "27") (name "/B") (class "Default")
      (node (ref "FB3") (pin "1") (pinfunction "1_1") (pintype "passive"))
      (node (ref "R9") (pin "2") (pinfunction "2_2") (pintype "passive"))
      (node (ref "U1") (pin "2") (pinfunction "B_2") (pintype "passive"))
    )
    (net (code "28") (name "/BA14") (class "Default")
      (node (ref "U24") (pin "74") (pinfunction "BA14/PL0_74") (pintype "passive"))
      (node (ref "U26") (pin "29") (pinfunction "A14_29") (pintype "passive"))
    )
    (net (code "29") (name "/BA15") (class "Default")
      (node (ref "U24") (pin "73") (pinfunction "BA15_73") (pintype "passive"))
      (node (ref "U26") (pin "3") (pinfunction "A15_3") (pintype "passive"))
    )
    (net (code "30") (name "/BA16") (class "Default")
      (node (ref "RN4") (pin "2") (pinfunction "2_2") (pintype "passive"))
      (node (ref "U24") (pin "72") (pinfunction "BA16/BS4_72") (pintype "passive"))
      (node (ref "U26") (pin "2") (pinfunction "A16_2") (pintype "passive"))
    )
    (net (code "31") (name "/BA17") (class "Default")
      (node (ref "RN3") (pin "4") (pinfunction "4_4") (pintype "passive"))
      (node (ref "U24") (pin "71") (pinfunction "BA17/BS3_71") (pintype "passive"))
      (node (ref "U26") (pin "30") (pinfunction "A17_30") (pintype "passive"))
    )
    (net (code "32") (name "/BA18") (class "Default")
      (node (ref "RN3") (pin "3") (pinfunction "3_3") (pintype "passive"))
      (node (ref "U24") (pin "69") (pinfunction "BA18/BS2_69") (pintype "passive"))
      (node (ref "U26") (pin "1") (pinfunction "A18_1") (pintype "passive"))
    )
    (net (code "33") (name "/BA19") (class "Default")
      (node (ref "RN3") (pin "2") (pinfunction "2_2") (pintype "passive"))
      (node (ref "U24") (pin "68") (pinfunction "BA19/BS1_68") (pintype "passive"))
    )
    (net (code "34") (name "/BA20") (class "Default")
      (node (ref "RN3") (pin "1") (pinfunction "1_1") (pintype "passive"))
      (node (ref "U24") (pin "67") (pinfunction "BA20/BS0_67") (pintype "passive"))
    )
    (net (code "35") (name "/BA21") (class "Default")
      (node (ref "RN1") (pin "2") (pinfunction "2_2") (pintype "passive"))
      (node (ref "U24") (pin "66") (pinfunction "BA21/PNP_66") (pintype "passive"))
    )
    (net (code "36") (name "/BD0") (class "Default")
      (node (ref "RN2") (pin "4") (pinfunction "4_4") (pintype "passive"))
      (node (ref "U24") (pin "85") (pinfunction "BD0/IOS3_85") (pintype "passive"))
      (node (ref "U26") (pin "13") (pinfunction "DQ0_13") (pintype "passive"))
    )
    (net (code "37") (name "/BD1") (class "Default")
      (node (ref "RN2") (pin "3") (pinfunction "3_3") (pintype "passive"))
      (node (ref "U24") (pin "84") (pinfunction "BD1/IOS2_84") (pintype "passive"))
      (node (ref "U26") (pin "14") (pinfunction "DQ1_14") (pintype "passive"))
    )
    (net (code "38") (name "/BD2") (class "Default")
      (node (ref "RN2") (pin "2") (pinfunction "2_2") (pintype "passive"))
      (node (ref "U24") (pin "82") (pinfunction "BD2/IOS1_82") (pintype "passive"))
      (node (ref "U26") (pin "15") (pinfunction "DQ2_15") (pintype "passive"))
    )
    (net (code "39") (name "/BD3") (class "Default")
      (node (ref "RN2") (pin "1") (pinfunction "1_1") (pintype "passive"))
      (node (ref "U24") (pin "81") (pinfunction "BD3/IOS0_81") (pintype "passive"))
      (node (ref "U26") (pin "17") (pinfunction "DQ3_17") (pintype "passive"))
    )
    (net (code "40") (name "/BD4") (class "Default")
      (node (ref "U24") (pin "80") (pinfunction "BD4/IRQS2_80") (pintype "passive"))
      (node (ref "U26") (pin "18") (pinfunction "DQ4_18") (pintype "passive"))
    )
    (net (code "41") (name "/BD5") (class "Default")
      (node (ref "RN1") (pin "4") (pinfunction "4_4") (pintype "passive"))
      (node (ref "U24") (pin "79") (pinfunction "BD5/IRQS1/EESK_79") (pintype "passive"))
      (node (ref "U25") (pin "2") (pinfunction "SCLK_2") (pintype "passive"))
      (node (ref "U26") (pin "19") (pinfunction "DQ5_19") (pintype "passive"))
    )
    (net (code "42") (name "/BD6") (class "Default")
      (node (ref "RN1") (pin "3") (pinfunction "3_3") (pintype "passive"))
      (node (ref "U24") (pin "78") (pinfunction "BD6/IRQS0/EEDI_78") (pintype "passive"))
      (node (ref "U25") (pin "3") (pinfunction "DI_3") (pintype "passive"))
      (node (ref "U26") (pin "20") (pinfunction "DQ6_20") (pintype "passive"))
    )
    (net (code "43") (name "/BD7") (class "Default")
      (node (ref "U24") (pin "77") (pinfunction "BD7/PL1/EEDO_77") (pintype "passive"))
      (node (ref "U25") (pin "4") (pinfunction "DO_4") (pintype "passive"))
      (node (ref "U26") (pin "21") (pinfunction "DQ7_21") (pintype "passive"))
    )
    (net (code "44") (name "/CTS") (class "Default")
      (node (ref "P2") (pin "6") (pinfunction "6_6") (pintype "passive"))
      (node (ref "U11") (pin "7") (pinfunction "RA4_7") (pintype "passive"))
    )
    (net (code "45") (name "/D0") (class "Default")
      (node (ref "BUS1") (pin "40") (pinfunction "SD0_40") (pintype "passive"))
      (node (ref "U1") (pin "25") (pinfunction "SD0_25") (pintype "passive"))
      (node (ref "U12") (pin "11") (pinfunction "DB0_11") (pintype "passive"))
      (node (ref "U14") (pin "11") (pinfunction "DQ0_11") (pintype "passive"))
      (node (ref "U18") (pin "2") (pinfunction "A1_2") (pintype "input"))
      (node (ref "U24") (pin "36") (pinfunction "SD0_36") (pintype "passive"))
      (node (ref "U27") (pin "4") (pinfunction "AD0_4") (pintype "bidirectional"))
      (node (ref "U9") (pin "2") (pinfunction "D0_2") (pintype "passive"))
    )
    (net (code "46") (name "/D1") (class "Default")
      (node (ref "BUS1") (pin "39") (pinfunction "SD1_39") (pintype "passive"))
      (node (ref "U1") (pin "26") (pinfunction "SD1_26") (pintype "passive"))
      (node (ref "U12") (pin "13") (pinfunction "DB1_13") (pintype "passive"))
      (node (ref "U14") (pin "12") (pinfunction "DQ1_12") (pintype "passive"))
      (node (ref "U18") (pin "3") (pinfunction "A2_3") (pintype "input"))
      (node (ref "U24") (pin "37") (pinfunction "SD1_37") (pintype "passive"))
      (node (ref "U27") (pin "5") (pinfunction "AD1_5") (pintype "bidirectional"))
      (node (ref "U9") (pin "3") (pinfunction "D1_3") (pintype "passive"))
    )
    (net (code "47") (name "/D2") (class "Default")
      (node (ref "BUS1") (pin "38") (pinfunction "SD2_38") (pintype "passive"))
      (node (ref "U1") (pin "27") (pinfunction "SD2_27") (pintype "passive"))
      (node (ref "U12") (pin "14") (pinfunction "DB2_14") (pintype "passive"))
      (node (ref "U14") (pin "13") (pinfunction "DQ2_13") (pintype "passive"))
      (node (ref "U18") (pin "4") (pinfunction "A3_4") (pintype "input"))
      (node (ref "U24") (pin "38") (pinfunction "SD2_38") (pintype "passive"))
      (node (ref "U27") (pin "6") (pinfunction "AD2_6") (pintype "bidirectional"))
      (node (ref "U9") (pin "4") (pinfunction "D2_4") (pintype "passive"))
    )
    (net (code "48") (name "/D3") (class "Default")
      (node (ref "BUS1") (pin "37") (pinfunction "SD3_37") (pintype "passive"))
      (node (ref "U1") (pin "28") (pinfunction "SD3_28") (pintype "passive"))
      (node (ref "U12") (pin "15") (pinfunction "DB3_15") (pintype "passive"))
      (node (ref "U14") (pin "15") (pinfunction "DQ3_15") (pintype "passive"))
      (node (ref "U18") (pin "5") (pinfunction "A4_5") (pintype "input"))
      (node (ref "U24") (pin "39") (pinfunction "SD3_39") (pintype "passive"))
      (node (ref "U27") (pin "7") (pinfunction "AD3_7") (pintype "bidirectional"))
      (node (ref "U9") (pin "5") (pinfunction "D3_5") (pintype "passive"))
    )
    (net (code "49") (name "/D4") (class "Default")
      (node (ref "BUS1") (pin "36") (pinfunction "SD4_36") (pintype "passive"))
      (node (ref "U1") (pin "29") (pinfunction "SD4_29") (pintype "passive"))
      (node (ref "U12") (pin "17") (pinfunction "DB4_17") (pintype "passive"))
      (node (ref "U14") (pin "16") (pinfunction "DQ4_16") (pintype "passive"))
      (node (ref "U18") (pin "6") (pinfunction "A5_6") (pintype "input"))
      (node (ref "U24") (pin "40") (pinfunction "SD4_40") (pintype "passive"))
      (node (ref "U27") (pin "8") (pinfunction "AD4_8") (pintype "bidirectional"))
      (node (ref "U9") (pin "6") (pinfunction "D4_6") (pintype "passive"))
    )
    (net (code "50") (name "/D5") (class "Default")
      (node (ref "BUS1") (pin "35") (pinfunction "SD5_35") (pintype "passive"))
      (node (ref "U1") (pin "30") (pinfunction "SD5_30") (pintype "passive"))
      (node (ref "U12") (pin "19") (pinfunction "DB5_19") (pintype "passive"))
      (node (ref "U14") (pin "17") (pinfunction "DQ5_17") (pintype "passive"))
      (node (ref "U18") (pin "7") (pinfunction "A6_7") (pintype "input"))
      (node (ref "U24") (pin "41") (pinfunction "SD5_41") (pintype "passive"))
      (node (ref "U27") (pin "9") (pinfunction "AD5_9") (pintype "bidirectional"))
      (node (ref "U9") (pin "7") (pinfunction "D5_7") (pintype "passive"))
    )
    (net (code "51") (name "/D6") (class "Default")
      (node (ref "BUS1") (pin "34") (pinfunction "SD6_34") (pintype "passive"))
      (node (ref "U1") (pin "31") (pinfunction "SD6_31") (pintype "passive"))
      (node (ref "U12") (pin "20") (pinfunction "DB6_20") (pintype "passive"))
      (node (ref "U14") (pin "18") (pinfunction "DQ6_18") (pintype "passive"))
      (node (ref "U18") (pin "8") (pinfunction "A7_8") (pintype "input"))
      (node (ref "U24") (pin "42") (pinfunction "SD6_42") (pintype "passive"))
      (node (ref "U27") (pin "10") (pinfunction "AD6_10") (pintype "bidirectional"))
      (node (ref "U9") (pin "8") (pinfunction "D6_8") (pintype "passive"))
    )
    (net (code "52") (name "/D7") (class "Default")
      (node (ref "BUS1") (pin "33") (pinfunction "SD7_33") (pintype "passive"))
      (node (ref "U1") (pin "32") (pinfunction "SD7_32") (pintype "passive"))
      (node (ref "U12") (pin "22") (pinfunction "DB7_22") (pintype "passive"))
      (node (ref "U14") (pin "19") (pinfunction "DQ7_19") (pintype "passive"))
      (node (ref "U18") (pin "9") (pinfunction "A8_9") (pintype "input"))
      (node (ref "U24") (pin "43") (pinfunction "SD7_43") (pintype "passive"))
      (node (ref "U27") (pin "11") (pinfunction "AD7_11") (pintype "bidirectional"))
      (node (ref "U9") (pin "9") (pinfunction "D7_9") (pintype "passive"))
    )
    (net (code "53") (name "/DAC_CLK") (class "Default")
      (node (ref "U15") (pin "23") (pinfunction "fSY_23") (pintype "passive"))
      (node (ref "U21") (pin "5") (pinfunction "fI_5") (pintype "passive"))
    )
    (net (code "54") (name "/DAC_DATA") (class "Default")
      (node (ref "U15") (pin "21") (pinfunction "MO_21") (pintype "passive"))
      (node (ref "U21") (pin "4") (pinfunction "SD_4") (pintype "passive"))
    )
    (net (code "55") (name "/DAC_SYNC") (class "Default")
      (node (ref "U15") (pin "20") (pinfunction "SH_20") (pintype "passive"))
      (node (ref "U21") (pin "3") (pinfunction "LOAD_3") (pintype "passive"))
    )
    (net (code "56") (name "/DB0") (class "Default")
      (node (ref "U15") (pin "10") (pinfunction "D0_10") (pintype "passive"))
      (node (ref "U18") (pin "18") (pinfunction "B1_18") (pintype "output"))
    )
    (net (code "57") (name "/DB1") (class "Default")
      (node (ref "U15") (pin "11") (pinfunction "D1_11") (pintype "passive"))
      (node (ref "U18") (pin "17") (pinfunction "B2_17") (pintype "output"))
    )
    (net (code "58") (name "/DB2") (class "Default")
      (node (ref "U15") (pin "13") (pinfunction "D2_13") (pintype "passive"))
      (node (ref "U18") (pin "16") (pinfunction "B3_16") (pintype "output"))
    )
    (net (code "59") (name "/DB3") (class "Default")
      (node (ref "U15") (pin "14") (pinfunction "D3_14") (pintype "passive"))
      (node (ref "U18") (pin "15") (pinfunction "B4_15") (pintype "output"))
    )
    (net (code "60") (name "/DB4") (class "Default")
      (node (ref "U15") (pin "15") (pinfunction "D4_15") (pintype "passive"))
      (node (ref "U18") (pin "14") (pinfunction "B5_14") (pintype "output"))
    )
    (net (code "61") (name "/DB5") (class "Default")
      (node (ref "U15") (pin "16") (pinfunction "D5_16") (pintype "passive"))
      (node (ref "U18") (pin "13") (pinfunction "B6_13") (pintype "output"))
    )
    (net (code "62") (name "/DB6") (class "Default")
      (node (ref "U15") (pin "17") (pinfunction "D6_17") (pintype "passive"))
      (node (ref "U18") (pin "12") (pinfunction "B7_12") (pintype "output"))
    )
    (net (code "63") (name "/DB7") (class "Default")
      (node (ref "U15") (pin "18") (pinfunction "D7_18") (pintype "passive"))
      (node (ref "U18") (pin "11") (pinfunction "B8_11") (pintype "output"))
    )
    (net (code "64") (name "/DCD") (class "Default")
      (node (ref "P2") (pin "1") (pinfunction "1_1") (pintype "passive"))
      (node (ref "U11") (pin "2") (pinfunction "RA1_2") (pintype "passive"))
    )
    (net (code "65") (name "/DENSL") (class "Default")
      (node (ref "P3") (pin "2") (pinfunction "P2_2") (pintype "passive"))
      (node (ref "U12") (pin "49") (pinfunction "DENSEL_49") (pintype "passive"))
    )
    (net (code "66") (name "/DIR") (class "Default")
      (node (ref "P3") (pin "18") (pinfunction "P18_18") (pintype "passive"))
      (node (ref "U12") (pin "56") (pinfunction "DIR_56") (pintype "passive"))
    )
    (net (code "67") (name "/DRQ2") (class "Default")
      (node (ref "BUS1") (pin "6") (pinfunction "DRQ2_6") (pintype "passive"))
      (node (ref "U12") (pin "24") (pinfunction "DRQ_24") (pintype "passive"))
    )
    (net (code "68") (name "/DSA") (class "Default")
      (node (ref "P3") (pin "14") (pinfunction "P14_14") (pintype "passive"))
      (node (ref "U12") (pin "58") (pinfunction "DS0_58") (pintype "passive"))
    )
    (net (code "69") (name "/DSB") (class "Default")
      (node (ref "P3") (pin "12") (pinfunction "P12_12") (pintype "passive"))
      (node (ref "U12") (pin "62") (pinfunction "DS1_62") (pintype "passive"))
    )
    (net (code "70") (name "/DSKCG") (class "Default")
      (node (ref "P3") (pin "34") (pinfunction "P34_34") (pintype "passive"))
      (node (ref "RR1") (pin "6") (pinfunction "6_6") (pintype "passive"))
      (node (ref "U12") (pin "31") (pinfunction "DSKCHG_31") (pintype "passive"))
    )
    (net (code "71") (name "/DSR") (class "Default")
      (node (ref "P2") (pin "2") (pinfunction "2_2") (pintype "passive"))
      (node (ref "U11") (pin "3") (pinfunction "RA2_3") (pintype "passive"))
    )
    (net (code "72") (name "/DTR") (class "Default")
      (node (ref "P2") (pin "7") (pinfunction "7_7") (pintype "passive"))
      (node (ref "U11") (pin "8") (pinfunction "DY3_8") (pintype "passive"))
    )
    (net (code "73") (name "/EECS") (class "Default")
      (node (ref "U24") (pin "76") (pinfunction "EECS_76") (pintype "passive"))
      (node (ref "U25") (pin "1") (pinfunction "CS_1") (pintype "passive"))
    )
    (net (code "74") (name "/EXPROMRDY") (class "Default")
      (node (ref "RR2") (pin "10") (pinfunction "10_10") (pintype "passive"))
      (node (ref "U14") (pin "1") (pinfunction "RDY/~{{BUSY}}_1") (pintype "passive"))
    )
    (net (code "75") (name "/FILTER_OUT") (class "Default")
      (node (ref "C35") (pin "2") (pinfunction "2_2") (pintype "passive"))
      (node (ref "C36") (pin "1") (pinfunction "1_1") (pintype "passive"))
      (node (ref "R24") (pin "2") (pinfunction "2_2") (pintype "passive"))
      (node (ref "U22") (pin "12") (pinfunction "OUT_12") (pintype "output"))
    )
    (net (code "76") (name "/G") (class "Default")
      (node (ref "FB2") (pin "1") (pinfunction "1_1") (pintype "passive"))
      (node (ref "R8") (pin "2") (pinfunction "2_2") (pintype "passive"))
      (node (ref "U1") (pin "3") (pinfunction "G_3") (pintype "passive"))
    )
    (net (code "77") (name "/HDSEL") (class "Default")
      (node (ref "P3") (pin "32") (pinfunction "P32_32") (pintype "passive"))
      (node (ref "U12") (pin "51") (pinfunction "HDSEL_51") (pintype "passive"))
    )
    (net (code "78") (name "/HSYNC") (class "Default")
      (node (ref "FB5") (pin "2") (pinfunction "2_2") (pintype "passive"))
      (node (ref "U1") (pin "48") (pinfunction "HSYNC_48") (pintype "passive"))
    )
    (net (code "79") (name "/INDEX") (class "Default")
      (node (ref "P3") (pin "8") (pinfunction "P8_8") (pintype "passive"))
      (node (ref "RR1") (pin "2") (pinfunction "2_2") (pintype "passive"))
      (node (ref "U12") (pin "26") (pinfunction "INDX_26") (pintype "passive"))
    )
    (net (code "80") (name "/IOCHRDY") (class "Default")
      (node (ref "BUS1") (pin "41") (pinfunction "IO_READY_41") (pintype "passive"))
      (node (ref "U1") (pin "157") (pinfunction "IOCHRDY_157") (pintype "passive"))
      (node (ref "U24") (pin "35") (pinfunction "IOCHRDY_35") (pintype "passive"))
    )
    (net (code "81") (name "/IRQ3") (class "Default")
      (node (ref "BUS1") (pin "25") (pinfunction "IRQ3_25") (pintype "passive"))
      (node (ref "J4") (pin "03") (pinfunction "03_03") (pintype "passive"))
      (node (ref "SW1") (pin "1") (pinfunction "1_1") (pintype "passive"))
      (node (ref "SW8") (pin "1B") (pinfunction "NO1_1B") (pintype "passive"))
      (node (ref "U24") (pin "3") (pinfunction "INT1/IRQ3_3") (pintype "passive"))
    )
    (net (code "82") (name "/IRQ4") (class "Default")
      (node (ref "BUS1") (pin "24") (pinfunction "IRQ4_24") (pintype "passive"))
      (node (ref "SW1") (pin "2") (pinfunction "2_2") (pintype "passive"))
      (node (ref "SW8") (pin "2B") (pinfunction "NO2_2B") (pintype "passive"))
      (node (ref "U24") (pin "2") (pinfunction "INT2/IRQ4_2") (pintype "passive"))
    )
    (net (code "83") (name "/IRQ5") (class "Default")
      (node (ref "BUS1") (pin "23") (pinfunction "IRQ5_23") (pintype "passive"))
      (node (ref "J4") (pin "01") (pinfunction "01_01") (pintype "passive"))
      (node (ref "SW1") (pin "3") (pinfunction "3_3") (pintype "passive"))
      (node (ref "SW8") (pin "3B") (pinfunction "NO3_3B") (pintype "passive"))
      (node (ref "U24") (pin "1") (pinfunction "INT3/IRQ5_1") (pintype "passive"))
    )
    (net (code "84") (name "/IRQ6") (class "Default")
      (node (ref "BUS1") (pin "22") (pinfunction "IRQ6_22") (pintype "passive"))
      (node (ref "SW8") (pin "4B") (pinfunction "NO4_4B") (pintype "passive"))
      (node (ref "U12") (pin "23") (pinfunction "INT_23") (pintype "passive"))
    )
    (net (code "85") (name "/IRQ7") (class "Default")
      (node (ref "BUS1") (pin "21") (pinfunction "IRQ7_21") (pintype "passive"))
      (node (ref "SW1") (pin "4") (pinfunction "4_4") (pintype "passive"))
      (node (ref "SW8") (pin "5B") (pinfunction "NO5_5B") (pintype "passive"))
    )
    (net (code "86") (name "/IRQ9") (class "Default")
      (node (ref "BUS1") (pin "4") (pinfunction "IRQ2_4") (pintype "passive"))
      (node (ref "J4") (pin "05") (pinfunction "05_05") (pintype "passive"))
      (node (ref "SW8") (pin "6B") (pinfunction "NO6_6B") (pintype "passive"))
      (node (ref "U24") (pin "4") (pinfunction "INT0/IRQ2/9_4") (pintype "passive"))
    )
    (net (code "87") (name "/JP") (class "Default")
      (node (ref "RN1") (pin "1") (pinfunction "1_1") (pintype "passive"))
      (node (ref "U24") (pin "65") (pinfunction "JP_65") (pintype "passive"))
    )
    (net (code "88") (name "/LED_CRS") (class "Default")
      (node (ref "R36") (pin "2") (pinfunction "2_2") (pintype "passive"))
      (node (ref "U24") (pin "62") (pinfunction "LED1/LED_RX/LED_CRS_62") (pintype "passive"))
    )
    (net (code "89") (name "/LED_LINK") (class "Default")
      (node (ref "R35") (pin "2") (pinfunction "2_2") (pintype "passive"))
      (node (ref "U24") (pin "61") (pinfunction "LED0/LED_COL/LED_LINK_61") (pintype "passive"))
    )
    (net (code "90") (name "/MAA0") (class "Default")
      (node (ref "U1") (pin "52") (pinfunction "MAA0_52") (pintype "passive"))
      (node (ref "U2") (pin "6") (pinfunction "A0_6") (pintype "passive"))
      (node (ref "U3") (pin "6") (pinfunction "A0_6") (pintype "passive"))
    )
    (net (code "91") (name "/MAA1") (class "Default")
      (node (ref "U1") (pin "53") (pinfunction "MAA1_53") (pintype "passive"))
      (node (ref "U2") (pin "7") (pinfunction "A1_7") (pintype "passive"))
      (node (ref "U3") (pin "7") (pinfunction "A1_7") (pintype "passive"))
    )
    (net (code "92") (name "/MAA2") (class "Default")
      (node (ref "U1") (pin "54") (pinfunction "MAA2_54") (pintype "passive"))
      (node (ref "U2") (pin "8") (pinfunction "A2_8") (pintype "passive"))
      (node (ref "U3") (pin "8") (pinfunction "A2_8") (pintype "passive"))
    )
    (net (code "93") (name "/MAA3") (class "Default")
      (node (ref "U1") (pin "55") (pinfunction "MAA3_55") (pintype "passive"))
      (node (ref "U2") (pin "9") (pinfunction "A3_9") (pintype "passive"))
      (node (ref "U3") (pin "9") (pinfunction "A3_9") (pintype "passive"))
    )
    (net (code "94") (name "/MAA4") (class "Default")
      (node (ref "U1") (pin "56") (pinfunction "MAA4_56") (pintype "passive"))
      (node (ref "U2") (pin "11") (pinfunction "A4_11") (pintype "passive"))
      (node (ref "U3") (pin "11") (pinfunction "A4_11") (pintype "passive"))
    )
    (net (code "95") (name "/MAA5") (class "Default")
      (node (ref "U1") (pin "57") (pinfunction "MAA5_57") (pintype "passive"))
      (node (ref "U2") (pin "12") (pinfunction "A5_12") (pintype "passive"))
      (node (ref "U3") (pin "12") (pinfunction "A5_12") (pintype "passive"))
    )
    (net (code "96") (name "/MAA6") (class "Default")
      (node (ref "U1") (pin "59") (pinfunction "MAA6_59") (pintype "passive"))
      (node (ref "U2") (pin "13") (pinfunction "A6_13") (pintype "passive"))
      (node (ref "U3") (pin "13") (pinfunction "A6_13") (pintype "passive"))
    )
    (net (code "97") (name "/MAA7") (class "Default")
      (node (ref "U1") (pin "60") (pinfunction "MAA7_60") (pintype "passive"))
      (node (ref "U2") (pin "14") (pinfunction "A7_14") (pintype "passive"))
      (node (ref "U3") (pin "14") (pinfunction "A7_14") (pintype "passive"))
    )
    (net (code "98") (name "/MAA8") (class "Default")
      (node (ref "U1") (pin "61") (pinfunction "MAA8_61") (pintype "passive"))
      (node (ref "U2") (pin "15") (pinfunction "A8_15") (pintype "passive"))
      (node (ref "U3") (pin "15") (pinfunction "A8_15") (pintype "passive"))
    )
    (net (code "99") (name "/MAB0") (class "Default")
      (node (ref "U1") (pin "73") (pinfunction "MAB0_73") (pintype "passive"))
      (node (ref "U4") (pin "6") (pinfunction "A0_6") (pintype "passive"))
      (node (ref "U5") (pin "6") (pinfunction "A0_6") (pintype "passive"))
    )
    (net (code "100") (name "/MAB1") (class "Default")
      (node (ref "U1") (pin "74") (pinfunction "MAB1_74") (pintype "passive"))
      (node (ref "U4") (pin "7") (pinfunction "A1_7") (pintype "passive"))
      (node (ref "U5") (pin "7") (pinfunction "A1_7") (pintype "passive"))
    )
    (net (code "101") (name "/MAB2") (class "Default")
      (node (ref "U1") (pin "75") (pinfunction "MAB2_75") (pintype "passive"))
      (node (ref "U4") (pin "8") (pinfunction "A2_8") (pintype "passive"))
      (node (ref "U5") (pin "8") (pinfunction "A2_8") (pintype "passive"))
    )
    (net (code "102") (name "/MAB3") (class "Default")
      (node (ref "U1") (pin "76") (pinfunction "MAB3_76") (pintype "passive"))
      (node (ref "U4") (pin "9") (pinfunction "A3_9") (pintype "passive"))
      (node (ref "U5") (pin "9") (pinfunction "A3_9") (pintype "passive"))
    )
    (net (code "103") (name "/MAB4") (class "Default")
      (node (ref "U1") (pin "77") (pinfunction "MAB4_77") (pintype "passive"))
      (node (ref "U4") (pin "11") (pinfunction "A4_11") (pintype "passive"))
      (node (ref "U5") (pin "11") (pinfunction "A4_11") (pintype "passive"))
    )
    (net (code "104") (name "/MAB5") (class "Default")
      (node (ref "U1") (pin "78") (pinfunction "MAB5_78") (pintype "passive"))
      (node (ref "U4") (pin "12") (pinfunction "A5_12") (pintype "passive"))
      (node (ref "U5") (pin "12") (pinfunction "A5_12") (pintype "passive"))
    )
    (net (code "105") (name "/MAB6") (class "Default")
      (node (ref "U1") (pin "82") (pinfunction "MAB6_82") (pintype "passive"))
      (node (ref "U4") (pin "13") (pinfunction "A6_13") (pintype "passive"))
      (node (ref "U5") (pin "13") (pinfunction "A6_13") (pintype "passive"))
    )
    (net (code "106") (name "/MAB7") (class "Default")
      (node (ref "U1") (pin "83") (pinfunction "MAB7_83") (pintype "passive"))
      (node (ref "U4") (pin "14") (pinfunction "A7_14") (pintype "passive"))
      (node (ref "U5") (pin "14") (pinfunction "A7_14") (pintype "passive"))
    )
    (net (code "107") (name "/MAB8") (class "Default")
      (node (ref "U1") (pin "84") (pinfunction "MAB8_84") (pintype "passive"))
      (node (ref "U4") (pin "15") (pinfunction "A8_15") (pintype "passive"))
      (node (ref "U5") (pin "15") (pinfunction "A8_15") (pintype "passive"))
    )
    (net (code "108") (name "/MCLK") (class "Default")
      (node (ref "U15") (pin "24") (pinfunction "fM_24") (pintype "passive"))
      (node (ref "U20") (pin "9") (pinfunction "2Q_9") (pintype "output"))
    )
    (net (code "109") (name "/MD0") (class "Default")
      (node (ref "U1") (pin "64") (pinfunction "MD0_64") (pintype "passive"))
      (node (ref "U2") (pin "1") (pinfunction "DQ1_1") (pintype "passive"))
    )
    (net (code "110") (name "/MD1") (class "Default")
      (node (ref "U1") (pin "65") (pinfunction "MD1_65") (pintype "passive"))
      (node (ref "U2") (pin "2") (pinfunction "DQ2_2") (pintype "passive"))
    )
    (net (code "111") (name "/MD2") (class "Default")
      (node (ref "R16") (pin "1") (pinfunction "1_1") (pintype "passive"))
      (node (ref "U1") (pin "66") (pinfunction "MD2_66") (pintype "passive"))
      (node (ref "U2") (pin "18") (pinfunction "DQ3_18") (pintype "passive"))
    )
    (net (code "112") (name "/MD3") (class "Default")
      (node (ref "R12") (pin "1") (pinfunction "1_1") (pintype "passive"))
      (node (ref "U1") (pin "67") (pinfunction "MD3_67") (pintype "passive"))
      (node (ref "U2") (pin "19") (pinfunction "DQ4_19") (pintype "passive"))
    )
    (net (code "113") (name "/MD4") (class "Default")
      (node (ref "U1") (pin "68") (pinfunction "MD4_68") (pintype "passive"))
      (node (ref "U3") (pin "1") (pinfunction "DQ1_1") (pintype "passive"))
    )
    (net (code "114") (name "/MD5") (class "Default")
      (node (ref "U1") (pin "70") (pinfunction "MD5_70") (pintype "passive"))
      (node (ref "U3") (pin "2") (pinfunction "DQ2_2") (pintype "passive"))
    )
    (net (code "115") (name "/MD6") (class "Default")
      (node (ref "U1") (pin "71") (pinfunction "MD6_71") (pintype "passive"))
      (node (ref "U3") (pin "18") (pinfunction "DQ3_18") (pintype "passive"))
    )
    (net (code "116") (name "/MD7") (class "Default")
      (node (ref "R11") (pin "1") (pinfunction "1_1") (pintype "passive"))
      (node (ref "U1") (pin "72") (pinfunction "MD7_72") (pintype "passive"))
      (node (ref "U3") (pin "19") (pinfunction "DQ4_19") (pintype "passive"))
    )
    (net (code "117") (name "/MD16") (class "Default")
      (node (ref "U1") (pin "89") (pinfunction "MD16_89") (pintype "passive"))
      (node (ref "U4") (pin "1") (pinfunction "DQ1_1") (pintype "passive"))
    )
    (net (code "118") (name "/MD17") (class "Default")
      (node (ref "U1") (pin "90") (pinfunction "MD17_90") (pintype "passive"))
      (node (ref "U4") (pin "2") (pinfunction "DQ2_2") (pintype "passive"))
    )
    (net (code "119") (name "/MD18") (class "Default")
      (node (ref "U1") (pin "91") (pinfunction "MD18_91") (pintype "passive"))
      (node (ref "U4") (pin "18") (pinfunction "DQ3_18") (pintype "passive"))
    )
    (net (code "120") (name "/MD19") (class "Default")
      (node (ref "U1") (pin "92") (pinfunction "MD19_92") (pintype "passive"))
      (node (ref "U4") (pin "19") (pinfunction "DQ4_19") (pintype "passive"))
    )
    (net (code "121") (name "/MD20") (class "Default")
      (node (ref "U1") (pin "93") (pinfunction "MD20_93") (pintype "passive"))
      (node (ref "U5") (pin "1") (pinfunction "DQ1_1") (pintype "passive"))
    )
    (net (code "122") (name "/MD21") (class "Default")
      (node (ref "U1") (pin "94") (pinfunction "MD21_94") (pintype "passive"))
      (node (ref "U5") (pin "2") (pinfunction "DQ2_2") (pintype "passive"))
    )
    (net (code "123") (name "/MD22") (class "Default")
      (node (ref "U1") (pin "95") (pinfunction "MD22_95") (pintype "passive"))
      (node (ref "U5") (pin "18") (pinfunction "DQ3_18") (pintype "passive"))
    )
    (net (code "124") (name "/MD23") (class "Default")
      (node (ref "U1") (pin "96") (pinfunction "MD23_96") (pintype "passive"))
      (node (ref "U5") (pin "19") (pinfunction "DQ4_19") (pintype "passive"))
    )
    (net (code "125") (name "/MEA") (class "Default")
      (node (ref "P3") (pin "10") (pinfunction "P10_10") (pintype "passive"))
      (node (ref "U12") (pin "57") (pinfunction "ME0_57") (pintype "passive"))
    )
    (net (code "126") (name "/MEB") (class "Default")
      (node (ref "P3") (pin "16") (pinfunction "P16_16") (pintype "passive"))
      (node (ref "U12") (pin "61") (pinfunction "ME1_61") (pintype "passive"))
    )
    (net (code "127") (name "/MONITOR") (class "Default")
      (node (ref "FB4") (pin "2") (pinfunction "2_2") (pintype "passive"))
      (node (ref "R10") (pin "1") (pinfunction "1_1") (pintype "passive"))
      (node (ref "U1") (pin "46") (pinfunction "MONITOR_46") (pintype "passive"))
    )
    (net (code "128") (name "/OPL_IRQ") (class "Default")
      (node (ref "J4") (pin "02") (pinfunction "02_02") (pintype "passive"))
      (node (ref "J4") (pin "04") (pinfunction "04_04") (pintype "passive"))
      (node (ref "J4") (pin "06") (pinfunction "06_06") (pintype "passive"))
      (node (ref "U19") (pin "2") (pinfunction "1Y_2") (pintype "output"))
    )
    (net (code "129") (name "/OSC") (class "Default")
      (node (ref "BUS1") (pin "30") (pinfunction "OSC_30") (pintype "passive"))
      (node (ref "U1") (pin "98") (pinfunction "ROMCLK_98") (pintype "passive"))
      (node (ref "U20") (pin "3") (pinfunction "1CLK_3") (pintype "input"))
    )
    (net (code "130") (name "/R") (class "Default")
      (node (ref "FB1") (pin "1") (pinfunction "1_1") (pintype "passive"))
      (node (ref "R7") (pin "2") (pinfunction "2_2") (pintype "passive"))
      (node (ref "U1") (pin "4") (pinfunction "R_4") (pintype "passive"))
    )
    (net (code "131") (name "/RDATA") (class "Default")
      (node (ref "P3") (pin "30") (pinfunction "P30_30") (pintype "passive"))
      (node (ref "RR1") (pin "5") (pinfunction "5_5") (pintype "passive"))
      (node (ref "U12") (pin "41") (pinfunction "RDDATA_41") (pintype "passive"))
    )
    (net (code "132") (name "/RESET") (class "Default")
      (node (ref "BUS1") (pin "2") (pinfunction "RESET_2") (pintype "passive"))
      (node (ref "R2") (pin "1") (pinfunction "1_1") (pintype "passive"))
      (node (ref "U19") (pin "13") (pinfunction "6A_13") (pintype "input"))
      (node (ref "U24") (pin "33") (pinfunction "RSTDRV_33") (pintype "passive"))
    )
    (net (code "133") (name "/RESETDRV") (class "Default")
      (node (ref "U12") (pin "32") (pinfunction "RESET_32") (pintype "passive"))
      (node (ref "U9") (pin "39") (pinfunction "MR_39") (pintype "passive"))
    )
    (net (code "134") (name "/RI") (class "Default")
      (node (ref "P2") (pin "8") (pinfunction "8_8") (pintype "passive"))
      (node (ref "U11") (pin "9") (pinfunction "RA5_9") (pintype "passive"))
    )
    (net (code "135") (name "/RMD0") (class "Default")
      (node (ref "U1") (pin "43") (pinfunction "RMD0_43") (pintype "passive"))
      (node (ref "U6") (pin "11") (pinfunction "DQ0_11") (pintype "passive"))
    )
    (net (code "136") (name "/RMD1") (class "Default")
      (node (ref "R13") (pin "1") (pinfunction "1_1") (pintype "passive"))
      (node (ref "U1") (pin "39") (pinfunction "RMD1_39") (pintype "passive"))
      (node (ref "U6") (pin "12") (pinfunction "DQ1_12") (pintype "passive"))
    )
    (net (code "137") (name "/RMD2") (class "Default")
      (node (ref "U1") (pin "38") (pinfunction "RMD2_38") (pintype "passive"))
      (node (ref "U6") (pin "13") (pinfunction "DQ2_13") (pintype "passive"))
    )
    (net (code "138") (name "/RMD3") (class "Default")
      (node (ref "U1") (pin "37") (pinfunction "RMD3_37") (pintype "passive"))
      (node (ref "U6") (pin "15") (pinfunction "DQ3_15") (pintype "passive"))
    )
    (net (code "139") (name "/RMD4") (class "Default")
      (node (ref "R14") (pin "1") (pinfunction "1_1") (pintype "passive"))
      (node (ref "U1") (pin "36") (pinfunction "RMD4_36") (pintype "passive"))
      (node (ref "U6") (pin "16") (pinfunction "DQ4_16") (pintype "passive"))
    )
    (net (code "140") (name "/RMD5") (class "Default")
      (node (ref "U1") (pin "35") (pinfunction "RMD5_35") (pintype "passive"))
      (node (ref "U6") (pin "17") (pinfunction "DQ5_17") (pintype "passive"))
    )
    (net (code "141") (name "/RMD6") (class "Default")
      (node (ref "R15") (pin "1") (pinfunction "1_1") (pintype "passive"))
      (node (ref "U1") (pin "34") (pinfunction "RMD6_34") (pintype "passive"))
      (node (ref "U6") (pin "18") (pinfunction "DQ6_18") (pintype "passive"))
    )
    (net (code "142") (name "/RMD7") (class "Default")
      (node (ref "U1") (pin "33") (pinfunction "RMD7_33") (pintype "passive"))
      (node (ref "U6") (pin "19") (pinfunction "DQ7_19") (pintype "passive"))
    )
    (net (code "143") (name "/ROMA0") (class "Default")
      (node (ref "U1") (pin "97") (pinfunction "ROMBA0_97") (pintype "passive"))
      (node (ref "U6") (pin "27") (pinfunction "A14_27") (pintype "passive"))
    )
    (net (code "144") (name "/RTC_ALE") (class "Default")
      (node (ref "U27") (pin "14") (pinfunction "AS_14") (pintype "bidirectional"))
      (node (ref "U30") (pin "10") (pinfunction "~{5Y}_10") (pintype "output"))
    )
    (net (code "145") (name "/RTC_IRQ") (class "Default")
      (node (ref "SW8") (pin "1A") (pinfunction "COM1_1A") (pintype "passive"))
      (node (ref "SW8") (pin "2A") (pinfunction "COM2_2A") (pintype "passive"))
      (node (ref "SW8") (pin "3A") (pinfunction "COM3_3A") (pintype "passive"))
      (node (ref "SW8") (pin "4A") (pinfunction "COM4_4A") (pintype "passive"))
      (node (ref "SW8") (pin "5A") (pinfunction "COM5_5A") (pintype "passive"))
      (node (ref "SW8") (pin "6A") (pinfunction "COM6_6A") (pintype "passive"))
      (node (ref "U30") (pin "12") (pinfunction "~{6Y}_12") (pintype "output"))
    )
    (net (code "146") (name "/RTS") (class "Default")
      (node (ref "P2") (pin "4") (pinfunction "4_4") (pintype "passive"))
      (node (ref "U11") (pin "5") (pinfunction "DY1_5") (pintype "passive"))
    )
    (net (code "147") (name "/RX") (class "Default")
      (node (ref "P2") (pin "3") (pinfunction "3_3") (pintype "passive"))
      (node (ref "U11") (pin "4") (pinfunction "RA3_4") (pintype "passive"))
    )
    (net (code "148") (name "/STEP") (class "Default")
      (node (ref "P3") (pin "20") (pinfunction "P20_20") (pintype "passive"))
      (node (ref "U12") (pin "55") (pinfunction "STEP_55") (pintype "passive"))
    )
    (net (code "149") (name "/TC") (class "Default")
      (node (ref "BUS1") (pin "27") (pinfunction "TC_27") (pintype "passive"))
      (node (ref "U12") (pin "25") (pinfunction "TC_25") (pintype "passive"))
    )
    (net (code "150") (name "/TP_RX_N") (class "Default")
      (node (ref "P5") (pin "R6") (pinfunction "RD-_R6") (pintype "input"))
      (node (ref "R38") (pin "2") (pinfunction "2_2") (pintype "passive"))
      (node (ref "U24") (pin "58") (pinfunction "TPIN-_58") (pintype "passive"))
    )
    (net (code "151") (name "/TP_RX_P") (class "Default")
      (node (ref "P5") (pin "R3") (pinfunction "RD+_R3") (pintype "input"))
      (node (ref "R38") (pin "1") (pinfunction "1_1") (pintype "passive"))
      (node (ref "U24") (pin "59") (pinfunction "TPIN+_59") (pintype "passive"))
    )
    (net (code "152") (name "/TP_TX_N") (class "Default")
      (node (ref "P5") (pin "R2") (pinfunction "TD-_R2") (pintype "input"))
      (node (ref "U24") (pin "46") (pinfunction "TPOUT-_46") (pintype "passive"))
    )
    (net (code "153") (name "/TP_TX_P") (class "Default")
      (node (ref "P5") (pin "R1") (pinfunction "TD+_R1") (pintype "input"))
      (node (ref "U24") (pin "45") (pinfunction "TPOUT+_45") (pintype "passive"))
    )
    (net (code "154") (name "/TRK00") (class "Default")
      (node (ref "P3") (pin "26") (pinfunction "P26_26") (pintype "passive"))
      (node (ref "RR1") (pin "3") (pinfunction "3_3") (pintype "passive"))
      (node (ref "U12") (pin "2") (pinfunction "TRK0_2") (pintype "passive"))
    )
    (net (code "155") (name "/TX") (class "Default")
      (node (ref "P2") (pin "5") (pinfunction "5_5") (pintype "passive"))
      (node (ref "U11") (pin "6") (pinfunction "DY2_6") (pintype "passive"))
    )
    (net (code "156") (name "/UART_IRQ") (class "Default")
      (node (ref "SW1") (pin "1.1") (pinfunction "1.1_1.1") (pintype "passive"))
      (node (ref "SW1") (pin "2.1") (pinfunction "2.1_2.1") (pintype "passive"))
      (node (ref "SW1") (pin "3.1") (pinfunction "3.1_3.1") (pintype "passive"))
      (node (ref "SW1") (pin "4.1") (pinfunction "4.1_4.1") (pintype "passive"))
      (node (ref "U9") (pin "33") (pinfunction "INTR_33") (pintype "passive"))
    )
    (net (code "157") (name "/VBAT") (class "Default")
      (node (ref "BT1") (pin "POS") (pinfunction "POS_POS") (pintype "passive"))
      (node (ref "U27") (pin "20") (pinfunction "VBAT_20") (pintype "power_in"))
    )
    (net (code "158") (name "/VSS") (class "Default")
      (node (ref "BUS1") (pin "7") (pinfunction "-12V_7") (pintype "passive"))
      (node (ref "C50") (pin "2") (pinfunction "2_2") (pintype "passive"))
      (node (ref "C51") (pin "2") (pinfunction "2_2") (pintype "passive"))
      (node (ref "C53") (pin "2") (pinfunction "2_2") (pintype "passive"))
      (node (ref "U11") (pin "10") (pinfunction "VSS_10") (pintype "passive"))
      (node (ref "U22") (pin "7") (pinfunction "VCC-_7") (pintype "power_in"))
    )
    (net (code "159") (name "/VSYNC") (class "Default")
      (node (ref "FB6") (pin "2") (pinfunction "2_2") (pintype "passive"))
      (node (ref "U1") (pin "47") (pinfunction "VSYNC_47") (pintype "passive"))
    )
    (net (code "160") (name "/WDATA") (class "Default")
      (node (ref "P3") (pin "22") (pinfunction "P22_22") (pintype "passive"))
      (node (ref "U12") (pin "53") (pinfunction "WRDATA_53") (pintype "passive"))
    )
    (net (code "161") (name "/WE") (class "Default")
      (node (ref "P3") (pin "24") (pinfunction "P24_24") (pintype "passive"))
      (node (ref "U12") (pin "52") (pinfunction "WE_52") (pintype "passive"))
    )
    (net (code "162") (name "/WP") (class "Default")
      (node (ref "P3") (pin "28") (pinfunction "P28_28") (pintype "passive"))
      (node (ref "RR1") (pin "4") (pinfunction "4_4") (pintype "passive"))
      (node (ref "U12") (pin "1") (pinfunction "WP_1") (pintype "passive"))
    )
    (net (code "163") (name "/nBCS") (class "Default")
      (node (ref "U24") (pin "75") (pinfunction "~{BCSB}_75") (pintype "passive"))
      (node (ref "U26") (pin "22") (pinfunction "~{CE}_22") (pintype "passive"))
    )
    (net (code "164") (name "/nCAS") (class "Default")
      (node (ref "C20") (pin "1") (pinfunction "1_1") (pintype "passive"))
      (node (ref "R5") (pin "2") (pinfunction "2_2") (pintype "passive"))
      (node (ref "U2") (pin "17") (pinfunction "~{{CAS}}_17") (pintype "passive"))
      (node (ref "U3") (pin "17") (pinfunction "~{{CAS}}_17") (pintype "passive"))
      (node (ref "U4") (pin "17") (pinfunction "~{{CAS}}_17") (pintype "passive"))
      (node (ref "U5") (pin "17") (pinfunction "~{{CAS}}_17") (pintype "passive"))
    )
    (net (code "165") (name "/nCTS") (class "Default")
      (node (ref "U11") (pin "14") (pinfunction "RY4_14") (pintype "passive"))
      (node (ref "U9") (pin "40") (pinfunction "~{{CTS}}_40") (pintype "passive"))
    )
    (net (code "166") (name "/nDACK2") (class "Default")
      (node (ref "BUS1") (pin "26") (pinfunction "DACK2_26") (pintype "passive"))
      (node (ref "U12") (pin "3") (pinfunction "~{{DACK}}_3") (pintype "passive"))
    )
    (net (code "167") (name "/nDCD") (class "Default")
      (node (ref "U11") (pin "19") (pinfunction "RY1_19") (pintype "passive"))
      (node (ref "U9") (pin "42") (pinfunction "~{{DCD}}_42") (pintype "passive"))
    )
    (net (code "168") (name "/nDEC1") (class "Default")
      (node (ref "U28") (pin "19") (pinfunction "~{P=Q}_19") (pintype "output"))
      (node (ref "U29") (pin "1") (pinfunction "~{1G}_1") (pintype "input"))
      (node (ref "U29") (pin "15") (pinfunction "~{2G}_15") (pintype "input"))
    )
    (net (code "169") (name "/nDSR") (class "Default")
      (node (ref "U11") (pin "18") (pinfunction "RY2_18") (pintype "passive"))
      (node (ref "U9") (pin "41") (pinfunction "~{{DSR}}_41") (pintype "passive"))
    )
    (net (code "170") (name "/nDTR") (class "Default")
      (node (ref "U11") (pin "13") (pinfunction "DA3_13") (pintype "passive"))
      (node (ref "U9") (pin "37") (pinfunction "~{{DTR}}_37") (pintype "passive"))
    )
    (net (code "171") (name "/nEXPROMCS") (class "Default")
      (node (ref "RR2") (pin "2") (pinfunction "2_2") (pintype "passive"))
      (node (ref "SW2") (pin "1.1") (pinfunction "1.1_1.1") (pintype "passive"))
      (node (ref "U14") (pin "20") (pinfunction "~{{CE}}_20") (pintype "passive"))
    )
    (net (code "172") (name "/nEXPROMCS_in") (class "Default")
      (node (ref "SW2") (pin "1") (pinfunction "1_1") (pintype "passive"))
      (node (ref "U13") (pin "19") (pinfunction "~{P=Q}_19") (pintype "output"))
    )
    (net (code "173") (name "/nFDC_CS") (class "Default")
      (node (ref "U12") (pin "6") (pinfunction "CS_6") (pintype "passive"))
      (node (ref "U7") (pin "12") (pinfunction "Y3_12") (pintype "output"))
    )
    (net (code "174") (name "/nIOCHCK") (class "Default")
      (node (ref "BUS1") (pin "32") (pinfunction "IO_CH_CK_32") (pintype "passive"))
      (node (ref "U1") (pin "24") (pinfunction "~{{NMI}}_24") (pintype "passive"))
    )
    (net (code "175") (name "/nIOCS16") (class "Default")
      (node (ref "R37") (pin "2") (pinfunction "2_2") (pintype "passive"))
      (node (ref "U24") (pin "96") (pinfunction "~{IOCS16B/SLOT16}_96") (pintype "passive"))
    )
    (net (code "176") (name "/nIOR") (class "Default")
      (node (ref "BUS1") (pin "14") (pinfunction "IOR_14") (pintype "passive"))
      (node (ref "U1") (pin "153") (pinfunction "~{{IOR}}_153") (pintype "passive"))
      (node (ref "U12") (pin "4") (pinfunction "~{{RD}}_4") (pintype "passive"))
      (node (ref "U19") (pin "3") (pinfunction "2A_3") (pintype "input"))
      (node (ref "U24") (pin "29") (pinfunction "~{IORB}_29") (pintype "passive"))
      (node (ref "U29") (pin "2") (pinfunction "1A_2") (pintype "input"))
      (node (ref "U9") (pin "24") (pinfunction "~{{RD}}_24") (pintype "passive"))
    )
    (net (code "177") (name "/nIOW") (class "Default")
      (node (ref "BUS1") (pin "13") (pinfunction "IOW_13") (pintype "passive"))
      (node (ref "R1") (pin "2") (pinfunction "2_2") (pintype "passive"))
      (node (ref "U12") (pin "5") (pinfunction "~{{WR}}_5") (pintype "passive"))
      (node (ref "U19") (pin "5") (pinfunction "3A_5") (pintype "input"))
      (node (ref "U24") (pin "30") (pinfunction "~{IOWB}_30") (pintype "passive"))
      (node (ref "U29") (pin "14") (pinfunction "2A_14") (pintype "input"))
      (node (ref "U9") (pin "20") (pinfunction "~{{WR}}_20") (pintype "passive"))
    )
    (net (code "178") (name "/nMEMR") (class "Default")
      (node (ref "BUS1") (pin "12") (pinfunction "MEMR_12") (pintype "passive"))
      (node (ref "C18") (pin "1") (pinfunction "1_1") (pintype "passive"))
      (node (ref "U1") (pin "155") (pinfunction "~{{MEMR}}_155") (pintype "passive"))
      (node (ref "U14") (pin "22") (pinfunction "~{{OE}}_22") (pintype "passive"))
    )
    (net (code "179") (name "/nMEMW") (class "Default")
      (node (ref "BUS1") (pin "11") (pinfunction "MEMW_11") (pintype "passive"))
      (node (ref "SW2") (pin "2") (pinfunction "2_2") (pintype "passive"))
      (node (ref "U1") (pin "156") (pinfunction "~{{MEMW}}_156") (pintype "passive"))
    )
    (net (code "180") (name "/nOPL_CS") (class "Default")
      (node (ref "J3") (pin "2") (pinfunction "2_2") (pintype "passive"))
      (node (ref "J3") (pin "4") (pinfunction "4_4") (pintype "passive"))
      (node (ref "J3") (pin "6") (pinfunction "6_6") (pintype "passive"))
      (node (ref "J3") (pin "7") (pinfunction "7_7") (pintype "passive"))
      (node (ref "J3") (pin "8") (pinfunction "8_8") (pintype "passive"))
      (node (ref "U15") (pin "7") (pinfunction "~{CS}_7") (pintype "passive"))
      (node (ref "U16") (pin "9") (pinfunction "Y6_9") (pintype "output"))
      (node (ref "U18") (pin "19") (pinfunction "~{OE}_19") (pintype "output"))
    )
    (net (code "181") (name "/nOPL_IRQ") (class "Default")
      (node (ref "R17") (pin "2") (pinfunction "2_2") (pintype "passive"))
      (node (ref "U15") (pin "2") (pinfunction "~{IRQ}_2") (pintype "passive"))
      (node (ref "U19") (pin "1") (pinfunction "1A_1") (pintype "input"))
    )
    (net (code "182") (name "/nOPL_RD") (class "Default")
      (node (ref "U15") (pin "6") (pinfunction "~{RD}_6") (pintype "passive"))
      (node (ref "U18") (pin "1") (pinfunction "DIR_1") (pintype "input"))
      (node (ref "U19") (pin "10") (pinfunction "5Y_10") (pintype "output"))
    )
    (net (code "183") (name "/nOPL_WR") (class "Default")
      (node (ref "U15") (pin "5") (pinfunction "~{WR}_5") (pintype "passive"))
      (node (ref "U19") (pin "8") (pinfunction "4Y_8") (pintype "output"))
    )
    (net (code "184") (name "/nRAS") (class "Default")
      (node (ref "C21") (pin "1") (pinfunction "1_1") (pintype "passive"))
      (node (ref "R4") (pin "2") (pinfunction "2_2") (pintype "passive"))
      (node (ref "U2") (pin "4") (pinfunction "~{{RAS}}_4") (pintype "passive"))
      (node (ref "U3") (pin "4") (pinfunction "~{{RAS}}_4") (pintype "passive"))
      (node (ref "U4") (pin "4") (pinfunction "~{{RAS}}_4") (pintype "passive"))
      (node (ref "U5") (pin "4") (pinfunction "~{{RAS}}_4") (pintype "passive"))
    )
    (net (code "185") (name "/nREFRESH") (class "Default")
      (node (ref "BUS1") (pin "19") (pinfunction "DACK0_19") (pintype "passive"))
      (node (ref "U1") (pin "158") (pinfunction "ENMEM_158") (pintype "passive"))
    )
    (net (code "186") (name "/nRESET") (class "Default")
      (node (ref "U15") (pin "3") (pinfunction "~{IC}_3") (pintype "passive"))
      (node (ref "U19") (pin "12") (pinfunction "6Y_12") (pintype "output"))
    )
    (net (code "187") (name "/nRI") (class "Default")
      (node (ref "U11") (pin "12") (pinfunction "RY5_12") (pintype "passive"))
      (node (ref "U9") (pin "43") (pinfunction "~{{RI}}_43") (pintype "passive"))
    )
    (net (code "188") (name "/nROMCS") (class "Default")
      (node (ref "U1") (pin "45") (pinfunction "~{{ROMCS}}_45") (pintype "passive"))
      (node (ref "U6") (pin "22") (pinfunction "~{{OE}}_22") (pintype "passive"))
    )
    (net (code "189") (name "/nROMW") (class "Default")
      (node (ref "RR2") (pin "3") (pinfunction "3_3") (pintype "passive"))
      (node (ref "SW2") (pin "2.1") (pinfunction "2.1_2.1") (pintype "passive"))
      (node (ref "U14") (pin "27") (pinfunction "~{{WE}}_27") (pintype "passive"))
    )
    (net (code "190") (name "/nRTCIRQ") (class "Default")
      (node (ref "U27") (pin "19") (pinfunction "~{IRQ}_19") (pintype "bidirectional"))
      (node (ref "U30") (pin "13") (pinfunction "6A_13") (pintype "input"))
    )
    (net (code "191") (name "/nRTC_RD") (class "Default")
      (node (ref "U27") (pin "17") (pinfunction "DS_17") (pintype "bidirectional"))
      (node (ref "U29") (pin "6") (pinfunction "1Y2_6") (pintype "output"))
    )
    (net (code "192") (name "/nRTC_WR") (class "Default")
      (node (ref "U27") (pin "15") (pinfunction "R/*W_15") (pintype "bidirectional"))
      (node (ref "U29") (pin "10") (pinfunction "2Y2_10") (pintype "output"))
    )
    (net (code "193") (name "/nRTS") (class "Default")
      (node (ref "U11") (pin "16") (pinfunction "DA1_16") (pintype "passive"))
      (node (ref "U9") (pin "36") (pinfunction "~{{RTS}}_36") (pintype "passive"))
    )
    (net (code "194") (name "/nSIN") (class "Default")
      (node (ref "U11") (pin "17") (pinfunction "RY3_17") (pintype "passive"))
      (node (ref "U9") (pin "11") (pinfunction "SIN_11") (pintype "passive"))
    )
    (net (code "195") (name "/nSMEMR") (class "Default")
      (node (ref "U24") (pin "31") (pinfunction "~{SMEMRB}_31") (pintype "passive"))
      (node (ref "U26") (pin "24") (pinfunction "~{OE}_24") (pintype "passive"))
    )
    (net (code "196") (name "/nSMEMW") (class "Default")
      (node (ref "U24") (pin "32") (pinfunction "~{SMEMWB}_32") (pintype "passive"))
      (node (ref "U26") (pin "31") (pinfunction "~{WE}_31") (pintype "passive"))
    )
    (net (code "197") (name "/nSOUT") (class "Default")
      (node (ref "U11") (pin "15") (pinfunction "DA2_15") (pintype "passive"))
      (node (ref "U9") (pin "13") (pinfunction "SOUT_13") (pintype "passive"))
    )
    (net (code "198") (name "/nUART_CS") (class "Default")
      (node (ref "SW1") (pin "5.1") (pinfunction "5.1_5.1") (pintype "passive"))
      (node (ref "SW1") (pin "6.1") (pinfunction "6.1_6.1") (pintype "passive"))
      (node (ref "SW1") (pin "7.1") (pinfunction "7.1_7.1") (pintype "passive"))
      (node (ref "SW1") (pin "8.1") (pinfunction "8.1_8.1") (pintype "passive"))
      (node (ref "U9") (pin "16") (pinfunction "~{{CS2}}_16") (pintype "passive"))
    )
    (net (code "199") (name "/nWE0") (class "Default")
      (node (ref "U1") (pin "88") (pinfunction "~{{WE0}}_88") (pintype "passive"))
      (node (ref "U2") (pin "3") (pinfunction "~{{WE}}_3") (pintype "passive"))
      (node (ref "U3") (pin "3") (pinfunction "~{{WE}}_3") (pintype "passive"))
    )
    (net (code "200") (name "/nWE2") (class "Default")
      (node (ref "U1") (pin "87") (pinfunction "~{{WE2}}_87") (pintype "passive"))
      (node (ref "U4") (pin "3") (pinfunction "~{{WE}}_3") (pintype "passive"))
      (node (ref "U5") (pin "3") (pinfunction "~{{WE}}_3") (pintype "passive"))
    )
    (net (code "201") (name "GND") (class "Default")
      (node (ref "BT1") (pin "NEG") (pinfunction "NEG_NEG") (pintype "passive"))
      (node (ref "BUS1") (pin "1") (pinfunction "GND_1") (pintype "passive"))
      (node (ref "BUS1") (pin "10") (pinfunction "GND_10") (pintype "passive"))
      (node (ref "BUS1") (pin "31") (pinfunction "GND_31") (pintype "passive"))
      (node (ref "C1") (pin "2") (pinfunction "2_2") (pintype "passive"))
      (node (ref "C10") (pin "2") (pinfunction "2_2") (pintype "passive"))
      (node (ref "C11") (pin "2") (pinfunction "2_2") (pintype "passive"))
      (node (ref "C12") (pin "2") (pinfunction "2_2") (pintype "passive"))
      (node (ref "C13") (pin "2") (pinfunction "2_2") (pintype "passive"))
      (node (ref "C14") (pin "2") (pinfunction "2_2") (pintype "passive"))
      (node (ref "C15") (pin "2") (pinfunction "2_2") (pintype "passive"))
      (node (ref "C17") (pin "2") (pinfunction "2_2") (pintype "passive"))
      (node (ref "C18") (pin "2") (pinfunction "2_2") (pintype "passive"))
      (node (ref "C19") (pin "2") (pinfunction "2_2") (pintype "passive"))
      (node (ref "C2") (pin "2") (pinfunction "2_2") (pintype "passive"))
      (node (ref "C20") (pin "2") (pinfunction "2_2") (pintype "passive"))
      (node (ref "C21") (pin "2") (pinfunction "2_2") (pintype "passive"))
      (node (ref "C22") (pin "2") (pinfunction "2_2") (pintype "passive"))
      (node (ref "C23") (pin "2") (pinfunction "2_2") (pintype "passive"))
      (node (ref "C24") (pin "2") (pinfunction "2_2") (pintype "passive"))
      (node (ref "C25") (pin "2") (pinfunction "2_2") (pintype "passive"))
      (node (ref "C26") (pin "2") (pinfunction "2_2") (pintype "passive"))
      (node (ref "C27") (pin "2") (pinfunction "2_2") (pintype "passive"))
      (node (ref "C28") (pin "1") (pinfunction "1_1") (pintype "passive"))
      (node (ref "C29") (pin "1") (pinfunction "1_1") (pintype "passive"))
      (node (ref "C3") (pin "2") (pinfunction "2_2") (pintype "passive"))
      (node (ref "C31") (pin "2") (pinfunction "2_2") (pintype "passive"))
      (node (ref "C33") (pin "1") (pinfunction "1_1") (pintype "passive"))
      (node (ref "C34") (pin "1") (pinfunction "1_1") (pintype "passive"))
      (node (ref "C38") (pin "2") (pinfunction "2_2") (pintype "passive"))
      (node (ref "C39") (pin "2") (pinfunction "2_2") (pintype "passive"))
      (node (ref "C4") (pin "2") (pinfunction "2_2") (pintype "passive"))
      (node (ref "C40") (pin "2") (pinfunction "2_2") (pintype "passive"))
      (node (ref "C41") (pin "2") (pinfunction "2_2") (pintype "passive"))
      (node (ref "C44") (pin "2") (pinfunction "2_2") (pintype "passive"))
      (node (ref "C45") (pin "2") (pinfunction "2_2") (pintype "passive"))
      (node (ref "C46") (pin "2") (pinfunction "2_2") (pintype "passive"))
      (node (ref "C47") (pin "2") (pinfunction "2_2") (pintype "passive"))
      (node (ref "C48") (pin "2") (pinfunction "2_2") (pintype "passive"))
      (node (ref "C49") (pin "2") (pinfunction "2_2") (pintype "passive"))
      (node (ref "C5") (pin "2") (pinfunction "2_2") (pintype "passive"))
      (node (ref "C50") (pin "1") (pinfunction "1_1") (pintype "passive"))
      (node (ref "C51") (pin "1") (pinfunction "1_1") (pintype "passive"))
      (node (ref "C52") (pin "2") (pinfunction "2_2") (pintype "passive"))
      (node (ref "C53") (pin "1") (pinfunction "1_1") (pintype "passive"))
      (node (ref "C6") (pin "2") (pinfunction "2_2") (pintype "passive"))
      (node (ref "C7") (pin "2") (pinfunction "2_2") (pintype "passive"))
      (node (ref "C8") (pin "2") (pinfunction "2_2") (pintype "passive"))
      (node (ref "C9") (pin "2") (pinfunction "2_2") (pintype "passive"))
      (node (ref "CD1") (pin "2") (pinfunction "2_2") (pintype "passive"))
      (node (ref "CD10") (pin "2") (pinfunction "2_2") (pintype "passive"))
      (node (ref "CD11") (pin "2") (pinfunction "2_2") (pintype "passive"))
      (node (ref "CD12") (pin "2") (pinfunction "2_2") (pintype "passive"))
      (node (ref "CD13") (pin "2") (pinfunction "2_2") (pintype "passive"))
      (node (ref "CD14") (pin "2") (pinfunction "2_2") (pintype "passive"))
      (node (ref "CD15") (pin "2") (pinfunction "2_2") (pintype "passive"))
      (node (ref "CD16") (pin "2") (pinfunction "2_2") (pintype "passive"))
      (node (ref "CD17") (pin "2") (pinfunction "2_2") (pintype "passive"))
      (node (ref "CD18") (pin "2") (pinfunction "2_2") (pintype "passive"))
      (node (ref "CD19") (pin "2") (pinfunction "2_2") (pintype "passive"))
      (node (ref "CD2") (pin "2") (pinfunction "2_2") (pintype "passive"))
      (node (ref "CD20") (pin "2") (pinfunction "2_2") (pintype "passive"))
      (node (ref "CD21") (pin "2") (pinfunction "2_2") (pintype "passive"))
      (node (ref "CD22") (pin "2") (pinfunction "2_2") (pintype "passive"))
      (node (ref "CD23") (pin "2") (pinfunction "2_2") (pintype "passive"))
      (node (ref "CD24") (pin "2") (pinfunction "2_2") (pintype "passive"))
      (node (ref "CD25") (pin "2") (pinfunction "2_2") (pintype "passive"))
      (node (ref "CD27") (pin "2") (pinfunction "2_2") (pintype "passive"))
      (node (ref "CD28") (pin "2") (pinfunction "2_2") (pintype "passive"))
      (node (ref "CD29") (pin "2") (pinfunction "2_2") (pintype "passive"))
      (node (ref "CD3") (pin "2") (pinfunction "2_2") (pintype "passive"))
      (node (ref "CD32") (pin "2") (pinfunction "2_2") (pintype "passive"))
      (node (ref "CD4") (pin "2") (pinfunction "2_2") (pintype "passive"))
      (node (ref "CD42") (pin "2") (pinfunction "2_2") (pintype "passive"))
      (node (ref "CD43") (pin "2") (pinfunction "2_2") (pintype "passive"))
      (node (ref "CD5") (pin "2") (pinfunction "2_2") (pintype "passive"))
      (node (ref "CD6") (pin "2") (pinfunction "2_2") (pintype "passive"))
      (node (ref "CD7") (pin "2") (pinfunction "2_2") (pintype "passive"))
      (node (ref "CD8") (pin "2") (pinfunction "2_2") (pintype "passive"))
      (node (ref "CD9") (pin "2") (pinfunction "2_2") (pintype "passive"))
      (node (ref "D1") (pin "A") (pinfunction "A_A") (pintype "passive"))
      (node (ref "J1") (pin "1") (pinfunction "P1_1") (pintype "passive"))
      (node (ref "J5") (pin "2") (pinfunction "P2_2") (pintype "passive"))
      (node (ref "P1") (pin "10") (pinfunction "10_10") (pintype "passive"))
      (node (ref "P1") (pin "5") (pinfunction "5_5") (pintype "passive"))
      (node (ref "P1") (pin "6") (pinfunction "P6_6") (pintype "passive"))
      (node (ref "P1") (pin "7") (pinfunction "P7_7") (pintype "passive"))
      (node (ref "P1") (pin "8") (pinfunction "P8_8") (pintype "passive"))
      (node (ref "P2") (pin "9") (pinfunction "9_9") (pintype "passive"))
      (node (ref "P3") (pin "1") (pinfunction "P1_1") (pintype "passive"))
      (node (ref "P3") (pin "11") (pinfunction "P11_11") (pintype "passive"))
      (node (ref "P3") (pin "13") (pinfunction "P13_13") (pintype "passive"))
      (node (ref "P3") (pin "15") (pinfunction "P15_15") (pintype "passive"))
      (node (ref "P3") (pin "19") (pinfunction "P19_19") (pintype "passive"))
      (node (ref "P3") (pin "21") (pinfunction "P21_21") (pintype "passive"))
      (node (ref "P3") (pin "23") (pinfunction "P23_23") (pintype "passive"))
      (node (ref "P3") (pin "25") (pinfunction "25_25") (pintype "passive"))
      (node (ref "P3") (pin "29") (pinfunction "P29_29") (pintype "passive"))
      (node (ref "P3") (pin "31") (pinfunction "P31_31") (pintype "passive"))
      (node (ref "P3") (pin "5") (pinfunction "P5_5") (pintype "passive"))
      (node (ref "P3") (pin "7") (pinfunction "P7_7") (pintype "passive"))
      (node (ref "P4") (pin "1") (pinfunction "1_1") (pintype "passive"))
      (node (ref "P5") (pin "1") (pinfunction "SHIELD_1") (pintype "passive"))
      (node (ref "P5") (pin "2") (pinfunction "SHIELD_2") (pintype "passive"))
      (node (ref "P5") (pin "R8") (pinfunction "GND_R8") (pintype "input"))
      (node (ref "Q1") (pin "1") (pinfunction "E_1") (pintype "passive"))
      (node (ref "R11") (pin "2") (pinfunction "2_2") (pintype "passive"))
      (node (ref "R12") (pin "2") (pinfunction "2_2") (pintype "passive"))
      (node (ref "R13") (pin "2") (pinfunction "2_2") (pintype "passive"))
      (node (ref "R14") (pin "2") (pinfunction "2_2") (pintype "passive"))
      (node (ref "R15") (pin "2") (pinfunction "2_2") (pintype "passive"))
      (node (ref "R21") (pin "2") (pinfunction "2_2") (pintype "passive"))
      (node (ref "R25") (pin "2") (pinfunction "2_2") (pintype "passive"))
      (node (ref "R28") (pin "2") (pinfunction "2_2") (pintype "passive"))
      (node (ref "R3") (pin "2") (pinfunction "2_2") (pintype "passive"))
      (node (ref "R30") (pin "1") (pinfunction "1_1") (pintype "passive"))
      (node (ref "R31") (pin "1") (pinfunction "1_1") (pintype "passive"))
      (node (ref "R37") (pin "1") (pinfunction "1_1") (pintype "passive"))
      (node (ref "R7") (pin "1") (pinfunction "1_1") (pintype "passive"))
      (node (ref "R8") (pin "1") (pinfunction "1_1") (pintype "passive"))
      (node (ref "R9") (pin "1") (pinfunction "1_1") (pintype "passive"))
      (node (ref "RN4") (pin "8") (pinfunction "8_8") (pintype "passive"))
      (node (ref "RN5") (pin "1") (pinfunction "1_1") (pintype "passive"))
      (node (ref "RN5") (pin "2") (pinfunction "2_2") (pintype "passive"))
      (node (ref "RN5") (pin "3") (pinfunction "3_3") (pintype "passive"))
      (node (ref "RN5") (pin "4") (pinfunction "4_4") (pintype "passive"))
      (node (ref "RN5") (pin "5") (pinfunction "5_5") (pintype "passive"))
      (node (ref "RN5") (pin "6") (pinfunction "6_6") (pintype "passive"))
      (node (ref "RN5") (pin "7") (pinfunction "7_7") (pintype "passive"))
      (node (ref "RN5") (pin "8") (pinfunction "8_8") (pintype "passive"))
      (node (ref "RV1") (pin "1") (pinfunction "1_1") (pintype "passive"))
      (node (ref "SW2") (pin "3") (pinfunction "3_3") (pintype "passive"))
      (node (ref "SW2") (pin "4") (pinfunction "4_4") (pintype "passive"))
      (node (ref "SW2") (pin "5") (pinfunction "5_5") (pintype "passive"))
      (node (ref "SW2") (pin "6") (pinfunction "6_6") (pintype "passive"))
      (node (ref "SW2") (pin "7") (pinfunction "7_7") (pintype "passive"))
      (node (ref "U1") (pin "1") (pinfunction "AVSS2_1") (pintype "passive"))
      (node (ref "U1") (pin "101") (pinfunction "VSS_101") (pintype "passive"))
      (node (ref "U1") (pin "121") (pinfunction "VSS_121") (pintype "passive"))
      (node (ref "U1") (pin "122") (pinfunction "VSS_122") (pintype "passive"))
      (node (ref "U1") (pin "126") (pinfunction "AVSS_126") (pintype "passive"))
      (node (ref "U1") (pin "128") (pinfunction "DVSS1_128") (pintype "passive"))
      (node (ref "U1") (pin "143") (pinfunction "VSS_143") (pintype "passive"))
      (node (ref "U1") (pin "160") (pinfunction "VSS_160") (pintype "passive"))
      (node (ref "U1") (pin "23") (pinfunction "VSS_23") (pintype "passive"))
      (node (ref "U1") (pin "41") (pinfunction "VSS_41") (pintype "passive"))
      (node (ref "U1") (pin "42") (pinfunction "VSS_42") (pintype "passive"))
      (node (ref "U1") (pin "49") (pinfunction "EVIDEO_49") (pintype "passive"))
      (node (ref "U1") (pin "50") (pinfunction "ECLK_50") (pintype "passive"))
      (node (ref "U1") (pin "58") (pinfunction "VSS_58") (pintype "passive"))
      (node (ref "U1") (pin "7") (pinfunction "DVSS2_7") (pintype "passive"))
      (node (ref "U1") (pin "79") (pinfunction "VSS_79") (pintype "passive"))
      (node (ref "U1") (pin "80") (pinfunction "VSS_80") (pintype "passive"))
      (node (ref "U10") (pin "7") (pinfunction "GND_7") (pintype "passive"))
      (node (ref "U11") (pin "20") (pinfunction "VCC_20") (pintype "passive"))
      (node (ref "U12") (pin "12") (pinfunction "GND_12") (pintype "passive"))
      (node (ref "U12") (pin "16") (pinfunction "GND_16") (pintype "passive"))
      (node (ref "U12") (pin "21") (pinfunction "GND_21") (pintype "passive"))
      (node (ref "U12") (pin "30") (pinfunction "DRV2_30") (pintype "passive"))
      (node (ref "U12") (pin "35") (pinfunction "~{{INVERT}}_35") (pintype "passive"))
      (node (ref "U12") (pin "36") (pinfunction "GND_36") (pintype "passive"))
      (node (ref "U12") (pin "45") (pinfunction "AVSS_45") (pintype "passive"))
      (node (ref "U12") (pin "50") (pinfunction "GND_50") (pintype "passive"))
      (node (ref "U12") (pin "54") (pinfunction "GND_54") (pintype "passive"))
      (node (ref "U12") (pin "59") (pinfunction "GND_59") (pintype "passive"))
      (node (ref "U12") (pin "65") (pinfunction "GND_65") (pintype "passive"))
      (node (ref "U12") (pin "9") (pinfunction "GND_9") (pintype "passive"))
      (node (ref "U13") (pin "1") (pinfunction "~{G}_1") (pintype "input"))
      (node (ref "U13") (pin "10") (pinfunction "GND_10") (pintype "power_in"))
      (node (ref "U13") (pin "17") (pinfunction "P7_17") (pintype "input"))
      (node (ref "U13") (pin "18") (pinfunction "Q7_18") (pintype "input"))
      (node (ref "U14") (pin "14") (pinfunction "GND_14") (pintype "passive"))
      (node (ref "U15") (pin "12") (pinfunction "GND_12") (pintype "passive"))
      (node (ref "U16") (pin "8") (pinfunction "GND_8") (pintype "input"))
      (node (ref "U17") (pin "4") (pinfunction "~{G2A}_4") (pintype "input"))
      (node (ref "U17") (pin "8") (pinfunction "GND_8") (pintype "input"))
      (node (ref "U18") (pin "10") (pinfunction "GND_10") (pintype "power_in"))
      (node (ref "U19") (pin "7") (pinfunction "GND_7") (pintype "power_in"))
      (node (ref "U2") (pin "16") (pinfunction "~{{OE}}_16") (pintype "passive"))
      (node (ref "U2") (pin "20") (pinfunction "GND_20") (pintype "passive"))
      (node (ref "U20") (pin "7") (pinfunction "GND_7") (pintype "power_in"))
      (node (ref "U21") (pin "6") (pinfunction "GND_6") (pintype "passive"))
      (node (ref "U23") (pin "4") (pinfunction "GND_4") (pintype "power_in"))
      (node (ref "U24") (pin "14") (pinfunction "GND_14") (pintype "passive"))
      (node (ref "U24") (pin "28") (pinfunction "GND_28") (pintype "passive"))
      (node (ref "U24") (pin "44") (pinfunction "GND_44") (pintype "passive"))
      (node (ref "U24") (pin "52") (pinfunction "GND_52") (pintype "passive"))
      (node (ref "U24") (pin "83") (pinfunction "GND_83") (pintype "passive"))
      (node (ref "U24") (pin "86") (pinfunction "GND_86") (pintype "passive"))
      (node (ref "U25") (pin "5") (pinfunction "GND_5") (pintype "passive"))
      (node (ref "U26") (pin "16") (pinfunction "GND_16") (pintype "passive"))
      (node (ref "U27") (pin "12") (pinfunction "GND_12") (pintype "power_in"))
      (node (ref "U27") (pin "13") (pinfunction "~{CS}_13") (pintype "bidirectional"))
      (node (ref "U27") (pin "16") (pinfunction "GND_16") (pintype "power_in"))
      (node (ref "U28") (pin "10") (pinfunction "GND_10") (pintype "power_in"))
      (node (ref "U29") (pin "8") (pinfunction "GND_8") (pintype "power_in"))
      (node (ref "U3") (pin "16") (pinfunction "~{{OE}}_16") (pintype "passive"))
      (node (ref "U3") (pin "20") (pinfunction "GND_20") (pintype "passive"))
      (node (ref "U30") (pin "1") (pinfunction "1A_1") (pintype "input"))
      (node (ref "U30") (pin "3") (pinfunction "2A_3") (pintype "input"))
      (node (ref "U30") (pin "5") (pinfunction "3A_5") (pintype "input"))
      (node (ref "U30") (pin "7") (pinfunction "GND_7") (pintype "power_in"))
      (node (ref "U30") (pin "9") (pinfunction "4A_9") (pintype "input"))
      (node (ref "U4") (pin "16") (pinfunction "~{{OE}}_16") (pintype "passive"))
      (node (ref "U4") (pin "20") (pinfunction "GND_20") (pintype "passive"))
      (node (ref "U5") (pin "16") (pinfunction "~{{OE}}_16") (pintype "passive"))
      (node (ref "U5") (pin "20") (pinfunction "GND_20") (pintype "passive"))
      (node (ref "U6") (pin "14") (pinfunction "GND_14") (pintype "passive"))
      (node (ref "U6") (pin "20") (pinfunction "~{{CE}}_20") (pintype "passive"))
      (node (ref "U7") (pin "8") (pinfunction "GND_8") (pintype "input"))
      (node (ref "U8") (pin "4") (pinfunction "~{G2A}_4") (pintype "input"))
      (node (ref "U8") (pin "5") (pinfunction "~{G2B}_5") (pintype "input"))
      (node (ref "U8") (pin "8") (pinfunction "GND_8") (pintype "input"))
      (node (ref "U9") (pin "21") (pinfunction "WR_21") (pintype "passive"))
      (node (ref "U9") (pin "22") (pinfunction "GND_22") (pintype "passive"))
      (node (ref "U9") (pin "25") (pinfunction "RD_25") (pintype "passive"))
      (node (ref "U9") (pin "28") (pinfunction "~{{ADS}}_28") (pintype "passive"))
    )
    (net (code "202") (name "Net-(C15-Pad1)") (class "Default")
      (node (ref "C15") (pin "1") (pinfunction "1_1") (pintype "passive"))
      (node (ref "L3") (pin "1") (pinfunction "1_1") (pintype "passive"))
    )
    (net (code "203") (name "Net-(C22-Pad1)") (class "Default")
      (node (ref "C22") (pin "1") (pinfunction "1_1") (pintype "passive"))
      (node (ref "FB1") (pin "2") (pinfunction "2_2") (pintype "passive"))
      (node (ref "P1") (pin "1") (pinfunction "1_1") (pintype "passive"))
    )
    (net (code "204") (name "Net-(C23-Pad1)") (class "Default")
      (node (ref "C23") (pin "1") (pinfunction "1_1") (pintype "passive"))
      (node (ref "FB2") (pin "2") (pinfunction "2_2") (pintype "passive"))
      (node (ref "P1") (pin "2") (pinfunction "2_2") (pintype "passive"))
    )
    (net (code "205") (name "Net-(C24-Pad1)") (class "Default")
      (node (ref "C24") (pin "1") (pinfunction "1_1") (pintype "passive"))
      (node (ref "FB3") (pin "2") (pinfunction "2_2") (pintype "passive"))
      (node (ref "P1") (pin "3") (pinfunction "3_3") (pintype "passive"))
    )
    (net (code "206") (name "Net-(C25-Pad1)") (class "Default")
      (node (ref "C25") (pin "1") (pinfunction "1_1") (pintype "passive"))
      (node (ref "FB4") (pin "1") (pinfunction "1_1") (pintype "passive"))
      (node (ref "P1") (pin "12") (pinfunction "12_12") (pintype "passive"))
    )
    (net (code "207") (name "Net-(C26-Pad1)") (class "Default")
      (node (ref "C26") (pin "1") (pinfunction "1_1") (pintype "passive"))
      (node (ref "FB5") (pin "1") (pinfunction "1_1") (pintype "passive"))
      (node (ref "P1") (pin "13") (pinfunction "13_13") (pintype "passive"))
    )
    (net (code "208") (name "Net-(C27-Pad1)") (class "Default")
      (node (ref "C27") (pin "1") (pinfunction "1_1") (pintype "passive"))
      (node (ref "FB6") (pin "1") (pinfunction "1_1") (pintype "passive"))
      (node (ref "P1") (pin "14") (pinfunction "14_14") (pintype "passive"))
    )
    (net (code "209") (name "Net-(C32-Pad1)") (class "Default")
      (node (ref "C32") (pin "1") (pinfunction "1_1") (pintype "passive"))
      (node (ref "R18") (pin "2") (pinfunction "2_2") (pintype "passive"))
      (node (ref "R19") (pin "1") (pinfunction "1_1") (pintype "passive"))
    )
    (net (code "210") (name "Net-(C35-Pad1)") (class "Default")
      (node (ref "C35") (pin "1") (pinfunction "1_1") (pintype "passive"))
      (node (ref "R22") (pin "2") (pinfunction "2_2") (pintype "passive"))
      (node (ref "R23") (pin "1") (pinfunction "1_1") (pintype "passive"))
    )
    (net (code "211") (name "Net-(C36-Pad2)") (class "Default")
      (node (ref "C36") (pin "2") (pinfunction "2_2") (pintype "passive"))
      (node (ref "R27") (pin "1") (pinfunction "1_1") (pintype "passive"))
      (node (ref "R28") (pin "1") (pinfunction "1_1") (pintype "passive"))
    )
    (net (code "212") (name "Net-(C37-Pad2)") (class "Default")
      (node (ref "C37") (pin "2") (pinfunction "2_2") (pintype "passive"))
      (node (ref "D1") (pin "C") (pinfunction "C_C") (pintype "passive"))
      (node (ref "R26") (pin "1") (pinfunction "1_1") (pintype "passive"))
    )
    (net (code "213") (name "Net-(C39-Pad1)") (class "Default")
      (node (ref "C39") (pin "1") (pinfunction "1_1") (pintype "passive"))
      (node (ref "R29") (pin "2") (pinfunction "2_2") (pintype "passive"))
      (node (ref "RV1") (pin "3") (pinfunction "3_3") (pintype "passive"))
    )
    (net (code "214") (name "Net-(C42-Pad2)") (class "Default")
      (node (ref "C42") (pin "2") (pinfunction "2_2") (pintype "passive"))
      (node (ref "R30") (pin "2") (pinfunction "2_2") (pintype "passive"))
    )
    (net (code "215") (name "Net-(C43-PadN)") (class "Default")
      (node (ref "C43") (pin "N") (pinfunction "N_N") (pintype "passive"))
      (node (ref "R31") (pin "2") (pinfunction "2_2") (pintype "passive"))
      (node (ref "R32") (pin "1") (pinfunction "1_1") (pintype "passive"))
      (node (ref "R33") (pin "1") (pinfunction "1_1") (pintype "passive"))
    )
    (net (code "216") (name "Net-(J1-P2)") (class "Default")
      (node (ref "J1") (pin "2") (pinfunction "P2_2") (pintype "passive"))
      (node (ref "R16") (pin "2") (pinfunction "2_2") (pintype "passive"))
    )
    (net (code "217") (name "Net-(J2-P2)") (class "Default")
      (node (ref "J2") (pin "2") (pinfunction "P2_2") (pintype "passive"))
      (node (ref "P3") (pin "3") (pinfunction "P3_3") (pintype "passive"))
    )
    (net (code "218") (name "Net-(J5-P1)") (class "Default")
      (node (ref "J5") (pin "1") (pinfunction "P1_1") (pintype "passive"))
      (node (ref "U27") (pin "21") (pinfunction "~{RCLR}_21") (pintype "bidirectional"))
    )
    (net (code "219") (name "Net-(P3-P6)") (class "Default")
      (node (ref "P3") (pin "6") (pinfunction "P6_6") (pintype "passive"))
      (node (ref "U12") (pin "28") (pinfunction "DRATE0_28") (pintype "passive"))
    )
    (net (code "220") (name "Net-(P4-Pad2)") (class "Default")
      (node (ref "P4") (pin "2") (pinfunction "2_2") (pintype "passive"))
      (node (ref "R33") (pin "2") (pinfunction "2_2") (pintype "passive"))
    )
    (net (code "221") (name "Net-(P4-Pad5)") (class "Default")
      (node (ref "P4") (pin "5") (pinfunction "5_5") (pintype "passive"))
      (node (ref "R32") (pin "2") (pinfunction "2_2") (pintype "passive"))
    )
    (net (code "222") (name "Net-(P5-PadL2)") (class "Default")
      (node (ref "P5") (pin "L2") (pinfunction "L2_L2") (pintype "passive"))
      (node (ref "R36") (pin "1") (pinfunction "1_1") (pintype "passive"))
    )
    (net (code "223") (name "Net-(P5-PadL3)") (class "Default")
      (node (ref "P5") (pin "L3") (pinfunction "L3_L3") (pintype "passive"))
      (node (ref "R35") (pin "1") (pinfunction "1_1") (pintype "passive"))
    )
    (net (code "224") (name "Net-(P5-RCT)") (class "Default")
      (node (ref "C46") (pin "1") (pinfunction "1_1") (pintype "passive"))
      (node (ref "P5") (pin "R5") (pinfunction "RCT_R5") (pintype "input"))
    )
    (net (code "225") (name "Net-(P5-TCT)") (class "Default")
      (node (ref "C47") (pin "1") (pinfunction "1_1") (pintype "passive"))
      (node (ref "P5") (pin "R4") (pinfunction "TCT_R4") (pintype "input"))
    )
    (net (code "226") (name "Net-(Q1-B)") (class "Default")
      (node (ref "Q1") (pin "2") (pinfunction "B_2") (pintype "passive"))
      (node (ref "R26") (pin "2") (pinfunction "2_2") (pintype "passive"))
    )
    (net (code "227") (name "Net-(Q1-C)") (class "Default")
      (node (ref "C38") (pin "1") (pinfunction "1_1") (pintype "passive"))
      (node (ref "Q1") (pin "3") (pinfunction "C_3") (pintype "passive"))
      (node (ref "R27") (pin "2") (pinfunction "2_2") (pintype "passive"))
      (node (ref "R29") (pin "1") (pinfunction "1_1") (pintype "passive"))
    )
    (net (code "228") (name "Net-(RN1-Pad5)") (class "Default")
      (node (ref "RN1") (pin "5") (pinfunction "5_5") (pintype "passive"))
      (node (ref "SW4") (pin "2") (pinfunction "2_2") (pintype "passive"))
    )
    (net (code "229") (name "Net-(RN1-Pad6)") (class "Default")
      (node (ref "RN1") (pin "6") (pinfunction "6_6") (pintype "passive"))
      (node (ref "SW4") (pin "1") (pinfunction "1_1") (pintype "passive"))
    )
    (net (code "230") (name "Net-(RN1-Pad7)") (class "Default")
      (node (ref "RN1") (pin "7") (pinfunction "7_7") (pintype "passive"))
      (node (ref "SW3") (pin "2") (pinfunction "2_2") (pintype "passive"))
    )
    (net (code "231") (name "Net-(RN1-Pad8)") (class "Default")
      (node (ref "RN1") (pin "8") (pinfunction "8_8") (pintype "passive"))
      (node (ref "SW3") (pin "1") (pinfunction "1_1") (pintype "passive"))
    )
    (net (code "232") (name "Net-(RN2-Pad5)") (class "Default")
      (node (ref "RN2") (pin "5") (pinfunction "5_5") (pintype "passive"))
      (node (ref "SW5") (pin "4") (pinfunction "4_4") (pintype "passive"))
    )
    (net (code "233") (name "Net-(RN2-Pad6)") (class "Default")
      (node (ref "RN2") (pin "6") (pinfunction "6_6") (pintype "passive"))
      (node (ref "SW5") (pin "3") (pinfunction "3_3") (pintype "passive"))
    )
    (net (code "234") (name "Net-(RN2-Pad7)") (class "Default")
      (node (ref "RN2") (pin "7") (pinfunction "7_7") (pintype "passive"))
      (node (ref "SW5") (pin "2") (pinfunction "2_2") (pintype "passive"))
    )
    (net (code "235") (name "Net-(RN2-Pad8)") (class "Default")
      (node (ref "RN2") (pin "8") (pinfunction "8_8") (pintype "passive"))
      (node (ref "SW5") (pin "1") (pinfunction "1_1") (pintype "passive"))
    )
    (net (code "236") (name "Net-(RN3-Pad5)") (class "Default")
      (node (ref "RN3") (pin "5") (pinfunction "5_5") (pintype "passive"))
      (node (ref "SW6") (pin "4") (pinfunction "4_4") (pintype "passive"))
    )
    (net (code "237") (name "Net-(RN3-Pad6)") (class "Default")
      (node (ref "RN3") (pin "6") (pinfunction "6_6") (pintype "passive"))
      (node (ref "SW6") (pin "3") (pinfunction "3_3") (pintype "passive"))
    )
    (net (code "238") (name "Net-(RN3-Pad7)") (class "Default")
      (node (ref "RN3") (pin "7") (pinfunction "7_7") (pintype "passive"))
      (node (ref "SW6") (pin "2") (pinfunction "2_2") (pintype "passive"))
    )
    (net (code "239") (name "Net-(RN3-Pad8)") (class "Default")
      (node (ref "RN3") (pin "8") (pinfunction "8_8") (pintype "passive"))
      (node (ref "SW6") (pin "1") (pinfunction "1_1") (pintype "passive"))
    )
    (net (code "240") (name "Net-(RN4-Pad7)") (class "Default")
      (node (ref "RN4") (pin "7") (pinfunction "7_7") (pintype "passive"))
      (node (ref "SW6") (pin "5") (pinfunction "5_5") (pintype "passive"))
    )
    (net (code "241") (name "Net-(U1-IRSET)") (class "Default")
      (node (ref "R3") (pin "1") (pinfunction "1_1") (pintype "passive"))
      (node (ref "U1") (pin "18") (pinfunction "IRSET_18") (pintype "passive"))
    )
    (net (code "242") (name "Net-(U1-RESET)") (class "Default")
      (node (ref "C19") (pin "1") (pinfunction "1_1") (pintype "passive"))
      (node (ref "R2") (pin "2") (pinfunction "2_2") (pintype "passive"))
      (node (ref "U1") (pin "5") (pinfunction "RESET_5") (pintype "passive"))
    )
    (net (code "243") (name "Net-(U1-VLF)") (class "Default")
      (node (ref "C16") (pin "1") (pinfunction "1_1") (pintype "passive"))
      (node (ref "U1") (pin "125") (pinfunction "VLF_125") (pintype "passive"))
    )
    (net (code "244") (name "Net-(U1-XTL1)") (class "Default")
      (node (ref "L3") (pin "2") (pinfunction "2_2") (pintype "passive"))
      (node (ref "U1") (pin "131") (pinfunction "XTL1_131") (pintype "passive"))
      (node (ref "X1") (pin "2") (pinfunction "2_2") (pintype "passive"))
    )
    (net (code "245") (name "Net-(U1-XTL2)") (class "Default")
      (node (ref "U1") (pin "133") (pinfunction "XTL2_133") (pintype "passive"))
      (node (ref "X1") (pin "1") (pinfunction "1_1") (pintype "passive"))
    )
    (net (code "246") (name "Net-(U1-~{{CAS}})") (class "Default")
      (node (ref "R5") (pin "1") (pinfunction "1_1") (pintype "passive"))
      (node (ref "U1") (pin "85") (pinfunction "~{{CAS}}_85") (pintype "passive"))
    )
    (net (code "247") (name "Net-(U1-~{{IOW}})") (class "Default")
      (node (ref "C17") (pin "1") (pinfunction "1_1") (pintype "passive"))
      (node (ref "R1") (pin "1") (pinfunction "1_1") (pintype "passive"))
      (node (ref "U1") (pin "154") (pinfunction "~{{IOW}}_154") (pintype "passive"))
    )
    (net (code "248") (name "Net-(U1-~{{MCS16}})") (class "Default")
      (node (ref "R6") (pin "2") (pinfunction "2_2") (pintype "passive"))
      (node (ref "U1") (pin "102") (pinfunction "~{{MCS16}}_102") (pintype "passive"))
    )
    (net (code "249") (name "Net-(U1-~{{RAS}})") (class "Default")
      (node (ref "R4") (pin "1") (pinfunction "1_1") (pintype "passive"))
      (node (ref "U1") (pin "86") (pinfunction "~{{RAS}}_86") (pintype "passive"))
    )
    (net (code "250") (name "Net-(U7-Y4)") (class "Default")
      (node (ref "SW1") (pin "5") (pinfunction "5_5") (pintype "passive"))
      (node (ref "U7") (pin "11") (pinfunction "Y4_11") (pintype "output"))
    )
    (net (code "251") (name "Net-(U7-Y5)") (class "Default")
      (node (ref "SW1") (pin "6") (pinfunction "6_6") (pintype "passive"))
      (node (ref "U7") (pin "10") (pinfunction "Y5_10") (pintype "output"))
    )
    (net (code "252") (name "Net-(U7-Y6)") (class "Default")
      (node (ref "SW1") (pin "7") (pinfunction "7_7") (pintype "passive"))
      (node (ref "U7") (pin "9") (pinfunction "Y6_9") (pintype "output"))
    )
    (net (code "253") (name "Net-(U7-Y7)") (class "Default")
      (node (ref "SW1") (pin "8") (pinfunction "8_8") (pintype "passive"))
      (node (ref "U7") (pin "7") (pinfunction "Y7_7") (pintype "output"))
    )
    (net (code "254") (name "Net-(U7-~{G2B})") (class "Default")
      (node (ref "U7") (pin "5") (pinfunction "~{G2B}_5") (pintype "input"))
      (node (ref "U8") (pin "7") (pinfunction "Y7_7") (pintype "output"))
    )
    (net (code "255") (name "Net-(U9-RCLK)") (class "Default")
      (node (ref "U9") (pin "10") (pinfunction "RCLK_10") (pintype "passive"))
      (node (ref "U9") (pin "17") (pinfunction "~{{BAUDOUT}}_17") (pintype "passive"))
    )
    (net (code "256") (name "Net-(U10-OUT)") (class "Default")
      (node (ref "U10") (pin "8") (pinfunction "OUT_8") (pintype "passive"))
      (node (ref "U9") (pin "18") (pinfunction "XIN_18") (pintype "passive"))
    )
    (net (code "257") (name "Net-(U12-HIFIL)") (class "Default")
      (node (ref "C30") (pin "2") (pinfunction "2_2") (pintype "passive"))
      (node (ref "U12") (pin "38") (pinfunction "HIFIL_38") (pintype "passive"))
    )
    (net (code "258") (name "Net-(U12-LOFIL)") (class "Default")
      (node (ref "C30") (pin "1") (pinfunction "1_1") (pintype "passive"))
      (node (ref "U12") (pin "37") (pinfunction "LOFIL_37") (pintype "passive"))
    )
    (net (code "259") (name "Net-(U12-X1)") (class "Default")
      (node (ref "C28") (pin "2") (pinfunction "2_2") (pintype "passive"))
      (node (ref "U12") (pin "33") (pinfunction "X1_33") (pintype "passive"))
      (node (ref "X2") (pin "2") (pinfunction "2_2") (pintype "passive"))
    )
    (net (code "260") (name "Net-(U12-X2)") (class "Default")
      (node (ref "C29") (pin "2") (pinfunction "2_2") (pintype "passive"))
      (node (ref "U12") (pin "34") (pinfunction "X2_34") (pintype "passive"))
      (node (ref "X2") (pin "1") (pinfunction "1_1") (pintype "passive"))
    )
    (net (code "261") (name "Net-(U13-Q2)") (class "Default")
      (node (ref "RR2") (pin "4") (pinfunction "4_4") (pintype "passive"))
      (node (ref "SW2") (pin "3.1") (pinfunction "3.1_3.1") (pintype "passive"))
      (node (ref "U13") (pin "7") (pinfunction "Q2_7") (pintype "input"))
    )
    (net (code "262") (name "Net-(U13-Q3)") (class "Default")
      (node (ref "RR2") (pin "5") (pinfunction "5_5") (pintype "passive"))
      (node (ref "SW2") (pin "4.1") (pinfunction "4.1_4.1") (pintype "passive"))
      (node (ref "U13") (pin "9") (pinfunction "Q3_9") (pintype "input"))
    )
    (net (code "263") (name "Net-(U13-Q4)") (class "Default")
      (node (ref "RR2") (pin "6") (pinfunction "6_6") (pintype "passive"))
      (node (ref "SW2") (pin "5.1") (pinfunction "5.1_5.1") (pintype "passive"))
      (node (ref "U13") (pin "12") (pinfunction "Q4_12") (pintype "input"))
    )
    (net (code "264") (name "Net-(U13-Q5)") (class "Default")
      (node (ref "RR2") (pin "7") (pinfunction "7_7") (pintype "passive"))
      (node (ref "SW2") (pin "6.1") (pinfunction "6.1_6.1") (pintype "passive"))
      (node (ref "U13") (pin "14") (pinfunction "Q5_14") (pintype "input"))
    )
    (net (code "265") (name "Net-(U13-Q6)") (class "Default")
      (node (ref "RR2") (pin "8") (pinfunction "8_8") (pintype "passive"))
      (node (ref "SW2") (pin "7.1") (pinfunction "7.1_7.1") (pintype "passive"))
      (node (ref "U13") (pin "16") (pinfunction "Q6_16") (pintype "input"))
    )
    (net (code "266") (name "Net-(U16-Y1)") (class "Default")
      (node (ref "J3") (pin "1") (pinfunction "1_1") (pintype "passive"))
      (node (ref "U16") (pin "14") (pinfunction "Y1_14") (pintype "output"))
    )
    (net (code "267") (name "Net-(U16-Y2)") (class "Default")
      (node (ref "J3") (pin "3") (pinfunction "3_3") (pintype "passive"))
      (node (ref "U16") (pin "13") (pinfunction "Y2_13") (pintype "output"))
    )
    (net (code "268") (name "Net-(U16-Y5)") (class "Default")
      (node (ref "J3") (pin "5") (pinfunction "5_5") (pintype "passive"))
      (node (ref "U16") (pin "10") (pinfunction "Y5_10") (pintype "output"))
    )
    (net (code "269") (name "Net-(U16-~{G2B})") (class "Default")
      (node (ref "U16") (pin "5") (pinfunction "~{G2B}_5") (pintype "input"))
      (node (ref "U17") (pin "15") (pinfunction "Y0_15") (pintype "output"))
    )
    (net (code "270") (name "Net-(U19-2Y)") (class "Default")
      (node (ref "U19") (pin "11") (pinfunction "5A_11") (pintype "input"))
      (node (ref "U19") (pin "4") (pinfunction "2Y_4") (pintype "output"))
    )
    (net (code "271") (name "Net-(U19-3Y)") (class "Default")
      (node (ref "U19") (pin "6") (pinfunction "3Y_6") (pintype "output"))
      (node (ref "U19") (pin "9") (pinfunction "4A_9") (pintype "input"))
    )
    (net (code "272") (name "Net-(U20-1D)") (class "Default")
      (node (ref "U20") (pin "2") (pinfunction "1D_2") (pintype "input"))
      (node (ref "U20") (pin "6") (pinfunction "1~Q_6") (pintype "output"))
    )
    (net (code "273") (name "Net-(U20-1Q)") (class "Default")
      (node (ref "U20") (pin "11") (pinfunction "2CLK_11") (pintype "input"))
      (node (ref "U20") (pin "5") (pinfunction "1Q_5") (pintype "output"))
    )
    (net (code "274") (name "Net-(U20-2D)") (class "Default")
      (node (ref "U20") (pin "12") (pinfunction "2D_12") (pintype "input"))
      (node (ref "U20") (pin "8") (pinfunction "2~Q_8") (pintype "output"))
    )
    (net (code "275") (name "Net-(U21-MP)") (class "Default")
      (node (ref "U21") (pin "8") (pinfunction "MP_8") (pintype "passive"))
      (node (ref "U22") (pin "1") (pinfunction "IN-_1") (pintype "input"))
      (node (ref "U22") (pin "3") (pinfunction "OUT_3") (pintype "output"))
    )
    (net (code "276") (name "Net-(U21-RB)") (class "Default")
      (node (ref "C31") (pin "1") (pinfunction "1_1") (pintype "passive"))
      (node (ref "U21") (pin "7") (pinfunction "RB_7") (pintype "passive"))
      (node (ref "U22") (pin "2") (pinfunction "IN+_2") (pintype "input"))
    )
    (net (code "277") (name "Net-(U21-ToBUFF)") (class "Default")
      (node (ref "U21") (pin "2") (pinfunction "ToBUFF_2") (pintype "passive"))
      (node (ref "U22") (pin "5") (pinfunction "IN+_5") (pintype "input"))
    )
    (net (code "278") (name "Net-(U22B-IN-)") (class "Default")
      (node (ref "R18") (pin "1") (pinfunction "1_1") (pintype "passive"))
      (node (ref "U22") (pin "4") (pinfunction "OUT_4") (pintype "output"))
      (node (ref "U22") (pin "6") (pinfunction "IN-_6") (pintype "input"))
    )
    (net (code "279") (name "Net-(U22C-IN+)") (class "Default")
      (node (ref "C33") (pin "2") (pinfunction "2_2") (pintype "passive"))
      (node (ref "R19") (pin "2") (pinfunction "2_2") (pintype "passive"))
      (node (ref "U22") (pin "9") (pinfunction "IN+_9") (pintype "input"))
    )
    (net (code "280") (name "Net-(U22C-IN-)") (class "Default")
      (node (ref "R20") (pin "1") (pinfunction "1_1") (pintype "passive"))
      (node (ref "R21") (pin "1") (pinfunction "1_1") (pintype "passive"))
      (node (ref "U22") (pin "8") (pinfunction "IN-_8") (pintype "input"))
    )
    (net (code "281") (name "Net-(U22C-OUT)") (class "Default")
      (node (ref "C32") (pin "2") (pinfunction "2_2") (pintype "passive"))
      (node (ref "R20") (pin "2") (pinfunction "2_2") (pintype "passive"))
      (node (ref "R22") (pin "1") (pinfunction "1_1") (pintype "passive"))
      (node (ref "U22") (pin "10") (pinfunction "OUT_10") (pintype "output"))
    )
    (net (code "282") (name "Net-(U22D-IN+)") (class "Default")
      (node (ref "C34") (pin "2") (pinfunction "2_2") (pintype "passive"))
      (node (ref "R23") (pin "2") (pinfunction "2_2") (pintype "passive"))
      (node (ref "U22") (pin "13") (pinfunction "IN+_13") (pintype "input"))
    )
    (net (code "283") (name "Net-(U22D-IN-)") (class "Default")
      (node (ref "R24") (pin "1") (pinfunction "1_1") (pintype "passive"))
      (node (ref "R25") (pin "1") (pinfunction "1_1") (pintype "passive"))
      (node (ref "U22") (pin "14") (pinfunction "IN-_14") (pintype "input"))
    )
    (net (code "284") (name "Net-(U23-+INPUT)") (class "Default")
      (node (ref "RV1") (pin "2") (pinfunction "2_2") (pintype "passive"))
      (node (ref "U23") (pin "3") (pinfunction "+INPUT_3") (pintype "input"))
    )
    (net (code "285") (name "Net-(U23--INPUT)") (class "Default")
      (node (ref "C40") (pin "1") (pinfunction "1_1") (pintype "passive"))
      (node (ref "U23") (pin "2") (pinfunction "-INPUT_2") (pintype "input"))
    )
    (net (code "286") (name "Net-(U23-BYPASS)") (class "Default")
      (node (ref "C41") (pin "1") (pinfunction "1_1") (pintype "passive"))
      (node (ref "U23") (pin "7") (pinfunction "BYPASS_7") (pintype "output"))
    )
    (net (code "287") (name "Net-(U24-X1)") (class "Default")
      (node (ref "C44") (pin "1") (pinfunction "1_1") (pintype "passive"))
      (node (ref "R34") (pin "2") (pinfunction "2_2") (pintype "passive"))
      (node (ref "U24") (pin "50") (pinfunction "X1_50") (pintype "passive"))
      (node (ref "X3") (pin "1") (pinfunction "1_1") (pintype "passive"))
    )
    (net (code "288") (name "Net-(U24-X2)") (class "Default")
      (node (ref "C45") (pin "1") (pinfunction "1_1") (pintype "passive"))
      (node (ref "R34") (pin "1") (pinfunction "1_1") (pintype "passive"))
      (node (ref "U24") (pin "51") (pinfunction "X2_51") (pintype "passive"))
      (node (ref "X3") (pin "2") (pinfunction "2_2") (pintype "passive"))
    )
    (net (code "289") (name "Net-(U27-X1)") (class "Default")
      (node (ref "U27") (pin "2") (pinfunction "X1_2") (pintype "bidirectional"))
      (node (ref "X4") (pin "1") (pinfunction "1_1") (pintype "passive"))
    )
    (net (code "290") (name "Net-(U27-X2)") (class "Default")
      (node (ref "U27") (pin "3") (pinfunction "X2_3") (pintype "bidirectional"))
      (node (ref "X4") (pin "2") (pinfunction "2_2") (pintype "passive"))
    )
    (net (code "291") (name "Net-(U28-Q0)") (class "Default")
      (node (ref "RN5") (pin "9") (pinfunction "9_9") (pintype "passive"))
      (node (ref "SW7") (pin "16") (pinfunction "16_16") (pintype "passive"))
      (node (ref "U28") (pin "3") (pinfunction "Q0_3") (pintype "input"))
    )
    (net (code "292") (name "Net-(U28-Q1)") (class "Default")
      (node (ref "RN5") (pin "10") (pinfunction "10_10") (pintype "passive"))
      (node (ref "SW7") (pin "15") (pinfunction "15_15") (pintype "passive"))
      (node (ref "U28") (pin "5") (pinfunction "Q1_5") (pintype "input"))
    )
    (net (code "293") (name "Net-(U28-Q2)") (class "Default")
      (node (ref "RN5") (pin "11") (pinfunction "11_11") (pintype "passive"))
      (node (ref "SW7") (pin "14") (pinfunction "14_14") (pintype "passive"))
      (node (ref "U28") (pin "7") (pinfunction "Q2_7") (pintype "input"))
    )
    (net (code "294") (name "Net-(U28-Q3)") (class "Default")
      (node (ref "RN5") (pin "12") (pinfunction "12_12") (pintype "passive"))
      (node (ref "SW7") (pin "13") (pinfunction "13_13") (pintype "passive"))
      (node (ref "U28") (pin "9") (pinfunction "Q3_9") (pintype "input"))
    )
    (net (code "295") (name "Net-(U28-Q4)") (class "Default")
      (node (ref "RN5") (pin "13") (pinfunction "13_13") (pintype "passive"))
      (node (ref "SW7") (pin "12") (pinfunction "12_12") (pintype "passive"))
      (node (ref "U28") (pin "12") (pinfunction "Q4_12") (pintype "input"))
    )
    (net (code "296") (name "Net-(U28-Q5)") (class "Default")
      (node (ref "RN5") (pin "14") (pinfunction "14_14") (pintype "passive"))
      (node (ref "SW7") (pin "11") (pinfunction "11_11") (pintype "passive"))
      (node (ref "U28") (pin "14") (pinfunction "Q5_14") (pintype "input"))
    )
    (net (code "297") (name "Net-(U28-Q6)") (class "Default")
      (node (ref "RN5") (pin "15") (pinfunction "15_15") (pintype "passive"))
      (node (ref "SW7") (pin "10") (pinfunction "10_10") (pintype "passive"))
      (node (ref "U28") (pin "16") (pinfunction "Q6_16") (pintype "input"))
    )
    (net (code "298") (name "Net-(U28-Q7)") (class "Default")
      (node (ref "RN5") (pin "16") (pinfunction "16_16") (pintype "passive"))
      (node (ref "SW7") (pin "9") (pinfunction "9_9") (pintype "passive"))
      (node (ref "U28") (pin "18") (pinfunction "Q7_18") (pintype "input"))
    )
    (net (code "299") (name "Net-(U29-2Y0)") (class "Default")
      (node (ref "U29") (pin "12") (pinfunction "2Y0_12") (pintype "output"))
      (node (ref "U30") (pin "11") (pinfunction "5A_11") (pintype "input"))
    )
    (net (code "300") (name "VCC") (class "Default")
      (node (ref "BUS1") (pin "29") (pinfunction "VCC_29") (pintype "passive"))
      (node (ref "BUS1") (pin "3") (pinfunction "VCC_3") (pintype "passive"))
      (node (ref "C1") (pin "1") (pinfunction "1_1") (pintype "passive"))
      (node (ref "C10") (pin "1") (pinfunction "1_1") (pintype "passive"))
      (node (ref "C2") (pin "1") (pinfunction "1_1") (pintype "passive"))
      (node (ref "C3") (pin "1") (pinfunction "1_1") (pintype "passive"))
      (node (ref "C37") (pin "1") (pinfunction "1_1") (pintype "passive"))
      (node (ref "C4") (pin "1") (pinfunction "1_1") (pintype "passive"))
      (node (ref "C5") (pin "1") (pinfunction "1_1") (pintype "passive"))
      (node (ref "C6") (pin "1") (pinfunction "1_1") (pintype "passive"))
      (node (ref "C7") (pin "1") (pinfunction "1_1") (pintype "passive"))
      (node (ref "C8") (pin "1") (pinfunction "1_1") (pintype "passive"))
      (node (ref "C9") (pin "1") (pinfunction "1_1") (pintype "passive"))
      (node (ref "CD1") (pin "1") (pinfunction "1_1") (pintype "passive"))
      (node (ref "CD10") (pin "1") (pinfunction "1_1") (pintype "passive"))
      (node (ref "CD11") (pin "1") (pinfunction "1_1") (pintype "passive"))
      (node (ref "CD12") (pin "1") (pinfunction "1_1") (pintype "passive"))
      (node (ref "CD13") (pin "1") (pinfunction "1_1") (pintype "passive"))
      (node (ref "CD14") (pin "1") (pinfunction "1_1") (pintype "passive"))
      (node (ref "CD15") (pin "1") (pinfunction "1_1") (pintype "passive"))
      (node (ref "CD16") (pin "1") (pinfunction "1_1") (pintype "passive"))
      (node (ref "CD17") (pin "1") (pinfunction "1_1") (pintype "passive"))
      (node (ref "CD18") (pin "1") (pinfunction "1_1") (pintype "passive"))
      (node (ref "CD19") (pin "1") (pinfunction "1_1") (pintype "passive"))
      (node (ref "CD2") (pin "1") (pinfunction "1_1") (pintype "passive"))
      (node (ref "CD20") (pin "1") (pinfunction "1_1") (pintype "passive"))
      (node (ref "CD21") (pin "1") (pinfunction "1_1") (pintype "passive"))
      (node (ref "CD22") (pin "1") (pinfunction "1_1") (pintype "passive"))
      (node (ref "CD23") (pin "1") (pinfunction "1_1") (pintype "passive"))
      (node (ref "CD24") (pin "1") (pinfunction "1_1") (pintype "passive"))
      (node (ref "CD25") (pin "1") (pinfunction "1_1") (pintype "passive"))
      (node (ref "CD27") (pin "1") (pinfunction "1_1") (pintype "passive"))
      (node (ref "CD28") (pin "1") (pinfunction "1_1") (pintype "passive"))
      (node (ref "CD29") (pin "1") (pinfunction "1_1") (pintype "passive"))
      (node (ref "CD3") (pin "1") (pinfunction "1_1") (pintype "passive"))
      (node (ref "CD32") (pin "1") (pinfunction "1_1") (pintype "passive"))
      (node (ref "CD4") (pin "1") (pinfunction "1_1") (pintype "passive"))
      (node (ref "CD5") (pin "1") (pinfunction "1_1") (pintype "passive"))
      (node (ref "CD6") (pin "1") (pinfunction "1_1") (pintype "passive"))
      (node (ref "CD7") (pin "1") (pinfunction "1_1") (pintype "passive"))
      (node (ref "CD8") (pin "1") (pinfunction "1_1") (pintype "passive"))
      (node (ref "CD9") (pin "1") (pinfunction "1_1") (pintype "passive"))
      (node (ref "J2") (pin "1") (pinfunction "P1_1") (pintype "passive"))
      (node (ref "L1") (pin "2") (pinfunction "2_2") (pintype "passive"))
      (node (ref "L2") (pin "2") (pinfunction "2_2") (pintype "passive"))
      (node (ref "P5") (pin "L1") (pinfunction "L1_L1") (pintype "passive"))
      (node (ref "P5") (pin "L4") (pinfunction "L4_L4") (pintype "passive"))
      (node (ref "R10") (pin "2") (pinfunction "2_2") (pintype "passive"))
      (node (ref "R17") (pin "1") (pinfunction "1_1") (pintype "passive"))
      (node (ref "R6") (pin "1") (pinfunction "1_1") (pintype "passive"))
      (node (ref "RR1") (pin "1") (pinfunction "COM_1") (pintype "passive"))
      (node (ref "RR2") (pin "1") (pinfunction "COM_1") (pintype "passive"))
      (node (ref "SW3") (pin "3") (pinfunction "3_3") (pintype "passive"))
      (node (ref "SW3") (pin "4") (pinfunction "4_4") (pintype "passive"))
      (node (ref "SW4") (pin "3") (pinfunction "3_3") (pintype "passive"))
      (node (ref "SW4") (pin "4") (pinfunction "4_4") (pintype "passive"))
      (node (ref "SW5") (pin "5") (pinfunction "5_5") (pintype "passive"))
      (node (ref "SW5") (pin "6") (pinfunction "6_6") (pintype "passive"))
      (node (ref "SW5") (pin "7") (pinfunction "7_7") (pintype "passive"))
      (node (ref "SW5") (pin "8") (pinfunction "8_8") (pintype "passive"))
      (node (ref "SW6") (pin "10") (pinfunction "10_10") (pintype "passive"))
      (node (ref "SW6") (pin "6") (pinfunction "6_6") (pintype "passive"))
      (node (ref "SW6") (pin "7") (pinfunction "7_7") (pintype "passive"))
      (node (ref "SW6") (pin "8") (pinfunction "8_8") (pintype "passive"))
      (node (ref "SW6") (pin "9") (pinfunction "9_9") (pintype "passive"))
      (node (ref "SW7") (pin "1") (pinfunction "1_1") (pintype "passive"))
      (node (ref "SW7") (pin "2") (pinfunction "2_2") (pintype "passive"))
      (node (ref "SW7") (pin "3") (pinfunction "3_3") (pintype "passive"))
      (node (ref "SW7") (pin "4") (pinfunction "4_4") (pintype "passive"))
      (node (ref "SW7") (pin "5") (pinfunction "5_5") (pintype "passive"))
      (node (ref "SW7") (pin "6") (pinfunction "6_6") (pintype "passive"))
      (node (ref "SW7") (pin "7") (pinfunction "7_7") (pintype "passive"))
      (node (ref "SW7") (pin "8") (pinfunction "8_8") (pintype "passive"))
      (node (ref "U1") (pin "120") (pinfunction "VDD_120") (pintype "passive"))
      (node (ref "U1") (pin "130") (pinfunction "DVDD1_130") (pintype "passive"))
      (node (ref "U1") (pin "134") (pinfunction "VDD_134") (pintype "passive"))
      (node (ref "U1") (pin "19") (pinfunction "VDD_19") (pintype "passive"))
      (node (ref "U1") (pin "21") (pinfunction "ALE_21") (pintype "passive"))
      (node (ref "U1") (pin "40") (pinfunction "VDD_40") (pintype "passive"))
      (node (ref "U1") (pin "51") (pinfunction "ESYNC_51") (pintype "passive"))
      (node (ref "U1") (pin "62") (pinfunction "VDD_62") (pintype "passive"))
      (node (ref "U1") (pin "69") (pinfunction "VDD_69") (pintype "passive"))
      (node (ref "U1") (pin "8") (pinfunction "DVDD2_8") (pintype "passive"))
      (node (ref "U1") (pin "81") (pinfunction "VDD_81") (pintype "passive"))
      (node (ref "U10") (pin "14") (pinfunction "VCC_14") (pintype "passive"))
      (node (ref "U11") (pin "11") (pinfunction "GND_11") (pintype "passive"))
      (node (ref "U12") (pin "18") (pinfunction "VCC_18") (pintype "passive"))
      (node (ref "U12") (pin "27") (pinfunction "IDENT_27") (pintype "passive"))
      (node (ref "U12") (pin "39") (pinfunction "PLL0_39") (pintype "passive"))
      (node (ref "U12") (pin "40") (pinfunction "VCC_40") (pintype "passive"))
      (node (ref "U12") (pin "46") (pinfunction "AVCC_46") (pintype "passive"))
      (node (ref "U12") (pin "60") (pinfunction "VCC_60") (pintype "passive"))
      (node (ref "U12") (pin "68") (pinfunction "VCC_68") (pintype "passive"))
      (node (ref "U13") (pin "20") (pinfunction "VCC_20") (pintype "power_in"))
      (node (ref "U13") (pin "3") (pinfunction "Q0_3") (pintype "input"))
      (node (ref "U13") (pin "5") (pinfunction "Q1_5") (pintype "input"))
      (node (ref "U14") (pin "28") (pinfunction "VCC_28") (pintype "passive"))
      (node (ref "U15") (pin "1") (pinfunction "VCC_1") (pintype "passive"))
      (node (ref "U16") (pin "16") (pinfunction "VCC_16") (pintype "power_in"))
      (node (ref "U17") (pin "16") (pinfunction "VCC_16") (pintype "power_in"))
      (node (ref "U18") (pin "20") (pinfunction "VCC_20") (pintype "power_in"))
      (node (ref "U19") (pin "14") (pinfunction "VCC_14") (pintype "power_in"))
      (node (ref "U2") (pin "10") (pinfunction "VCC_10") (pintype "passive"))
      (node (ref "U20") (pin "1") (pinfunction "1~CLR_1") (pintype "input"))
      (node (ref "U20") (pin "10") (pinfunction "2~PRE_10") (pintype "input"))
      (node (ref "U20") (pin "13") (pinfunction "2~CLR_13") (pintype "input"))
      (node (ref "U20") (pin "14") (pinfunction "VCC_14") (pintype "power_in"))
      (node (ref "U20") (pin "4") (pinfunction "1~PRE_4") (pintype "input"))
      (node (ref "U21") (pin "1") (pinfunction "VCC_1") (pintype "passive"))
      (node (ref "U24") (pin "17") (pinfunction "VCC_17") (pintype "passive"))
      (node (ref "U24") (pin "47") (pinfunction "VCC_47") (pintype "passive"))
      (node (ref "U24") (pin "57") (pinfunction "VCC_57") (pintype "passive"))
      (node (ref "U24") (pin "6") (pinfunction "VCC_6") (pintype "passive"))
      (node (ref "U24") (pin "70") (pinfunction "VCC_70") (pintype "passive"))
      (node (ref "U24") (pin "89") (pinfunction "VCC_89") (pintype "passive"))
      (node (ref "U25") (pin "6") (pinfunction "ORG_6") (pintype "passive"))
      (node (ref "U25") (pin "8") (pinfunction "VCC_8") (pintype "passive"))
      (node (ref "U26") (pin "32") (pinfunction "VCC_32") (pintype "passive"))
      (node (ref "U27") (pin "18") (pinfunction "~{RESET}_18") (pintype "bidirectional"))
      (node (ref "U27") (pin "24") (pinfunction "VCC_24") (pintype "power_in"))
      (node (ref "U28") (pin "20") (pinfunction "VCC_20") (pintype "power_in"))
      (node (ref "U29") (pin "16") (pinfunction "VCC_16") (pintype "power_in"))
      (node (ref "U3") (pin "10") (pinfunction "VCC_10") (pintype "passive"))
      (node (ref "U30") (pin "14") (pinfunction "VCC_14") (pintype "power_in"))
      (node (ref "U4") (pin "10") (pinfunction "VCC_10") (pintype "passive"))
      (node (ref "U5") (pin "10") (pinfunction "VCC_10") (pintype "passive"))
      (node (ref "U6") (pin "1") (pinfunction "VPP_1") (pintype "passive"))
      (node (ref "U6") (pin "28") (pinfunction "VCC_28") (pintype "passive"))
      (node (ref "U7") (pin "16") (pinfunction "VCC_16") (pintype "power_in"))
      (node (ref "U8") (pin "16") (pinfunction "VCC_16") (pintype "power_in"))
      (node (ref "U8") (pin "6") (pinfunction "G1_6") (pintype "input"))
      (node (ref "U9") (pin "14") (pinfunction "CS0_14") (pintype "passive"))
      (node (ref "U9") (pin "15") (pinfunction "CS1_15") (pintype "passive"))
      (node (ref "U9") (pin "44") (pinfunction "VCC_44") (pintype "passive"))
    )
    (net (code "301") (name "unconnected-(BUS1--5V-Pad5)") (class "Default")
      (node (ref "BUS1") (pin "5") (pinfunction "-5V_5") (pintype "passive+no_connect"))
    )
    (net (code "302") (name "unconnected-(BUS1-ALE-Pad28)") (class "Default")
      (node (ref "BUS1") (pin "28") (pinfunction "ALE_28") (pintype "passive+no_connect"))
    )
    (net (code "303") (name "unconnected-(BUS1-CLK-Pad20)") (class "Default")
      (node (ref "BUS1") (pin "20") (pinfunction "CLK_20") (pintype "passive+no_connect"))
    )
    (net (code "304") (name "unconnected-(BUS1-DACK1-Pad17)") (class "Default")
      (node (ref "BUS1") (pin "17") (pinfunction "DACK1_17") (pintype "passive+no_connect"))
    )
    (net (code "305") (name "unconnected-(BUS1-DACK3-Pad15)") (class "Default")
      (node (ref "BUS1") (pin "15") (pinfunction "DACK3_15") (pintype "passive+no_connect"))
    )
    (net (code "306") (name "unconnected-(BUS1-DRQ1-Pad18)") (class "Default")
      (node (ref "BUS1") (pin "18") (pinfunction "DRQ1_18") (pintype "passive+no_connect"))
    )
    (net (code "307") (name "unconnected-(BUS1-DRQ3-Pad16)") (class "Default")
      (node (ref "BUS1") (pin "16") (pinfunction "DRQ3_16") (pintype "passive+no_connect"))
    )
    (net (code "308") (name "unconnected-(BUS1-UNUSED-Pad8)") (class "Default")
      (node (ref "BUS1") (pin "8") (pinfunction "UNUSED_8") (pintype "passive+no_connect"))
    )
    (net (code "309") (name "unconnected-(P1-P9-Pad9)") (class "Default")
      (node (ref "P1") (pin "9") (pinfunction "P9_9") (pintype "passive+no_connect"))
    )
    (net (code "310") (name "unconnected-(P1-Pad4)") (class "Default")
      (node (ref "P1") (pin "4") (pinfunction "4_4") (pintype "passive+no_connect"))
    )
    (net (code "311") (name "unconnected-(P1-Pad11)") (class "Default")
      (node (ref "P1") (pin "11") (pinfunction "11_11") (pintype "passive+no_connect"))
    )
    (net (code "312") (name "unconnected-(P1-Pad15)") (class "Default")
      (node (ref "P1") (pin "15") (pinfunction "15_15") (pintype "passive+no_connect"))
    )
    (net (code "313") (name "unconnected-(P2-Pad10)") (class "Default")
      (node (ref "P2") (pin "10") (pinfunction "10_10") (pintype "passive+no_connect"))
    )
    (net (code "314") (name "unconnected-(P3-P4-Pad4)") (class "Default")
      (node (ref "P3") (pin "4") (pinfunction "P4_4") (pintype "passive+no_connect"))
    )
    (net (code "315") (name "unconnected-(P3-P9-Pad9)") (class "Default")
      (node (ref "P3") (pin "9") (pinfunction "P9_9") (pintype "passive+no_connect"))
    )
    (net (code "316") (name "unconnected-(P3-P17-Pad17)") (class "Default")
      (node (ref "P3") (pin "17") (pinfunction "P17_17") (pintype "passive+no_connect"))
    )
    (net (code "317") (name "unconnected-(P3-P27-Pad27)") (class "Default")
      (node (ref "P3") (pin "27") (pinfunction "P27_27") (pintype "passive+no_connect"))
    )
    (net (code "318") (name "unconnected-(P3-P33-Pad33)") (class "Default")
      (node (ref "P3") (pin "33") (pinfunction "P33_33") (pintype "passive+no_connect"))
    )
    (net (code "319") (name "unconnected-(P4-Pad3)") (class "Default")
      (node (ref "P4") (pin "3") (pinfunction "3_3") (pintype "passive+no_connect"))
    )
    (net (code "320") (name "unconnected-(P4-Pad4)") (class "Default")
      (node (ref "P4") (pin "4") (pinfunction "4_4") (pintype "passive+no_connect"))
    )
    (net (code "321") (name "unconnected-(RN4-Pad3)") (class "Default")
      (node (ref "RN4") (pin "3") (pinfunction "3_3") (pintype "passive+no_connect"))
    )
    (net (code "322") (name "unconnected-(RN4-Pad4)") (class "Default")
      (node (ref "RN4") (pin "4") (pinfunction "4_4") (pintype "passive+no_connect"))
    )
    (net (code "323") (name "unconnected-(RN4-Pad5)") (class "Default")
      (node (ref "RN4") (pin "5") (pinfunction "5_5") (pintype "passive+no_connect"))
    )
    (net (code "324") (name "unconnected-(RN4-Pad6)") (class "Default")
      (node (ref "RN4") (pin "6") (pinfunction "6_6") (pintype "passive+no_connect"))
    )
    (net (code "325") (name "unconnected-(RR2-Pad9)") (class "Default")
      (node (ref "RR2") (pin "9") (pinfunction "9_9") (pintype "passive+no_connect"))
    )
    (net (code "326") (name "unconnected-(SW2-Pad8)") (class "Default")
      (node (ref "SW2") (pin "8") (pinfunction "8_8") (pintype "passive+no_connect"))
    )
    (net (code "327") (name "unconnected-(SW2-Pad8.1)") (class "Default")
      (node (ref "SW2") (pin "8.1") (pinfunction "8.1_8.1") (pintype "passive+no_connect"))
    )
    (net (code "328") (name "unconnected-(U1-DMCLK-Pad129)") (class "Default")
      (node (ref "U1") (pin "129") (pinfunction "DMCLK_129") (pintype "passive+no_connect"))
    )
    (net (code "329") (name "unconnected-(U1-IRQ-Pad111)") (class "Default")
      (node (ref "U1") (pin "111") (pinfunction "IRQ_111") (pintype "passive+no_connect"))
    )
    (net (code "330") (name "unconnected-(U1-LA20-Pad116)") (class "Default")
      (node (ref "U1") (pin "116") (pinfunction "LA20_116") (pintype "passive+no_connect"))
    )
    (net (code "331") (name "unconnected-(U1-LA21-Pad117)") (class "Default")
      (node (ref "U1") (pin "117") (pinfunction "LA21_117") (pintype "passive+no_connect"))
    )
    (net (code "332") (name "unconnected-(U1-LA22-Pad118)") (class "Default")
      (node (ref "U1") (pin "118") (pinfunction "LA22_118") (pintype "passive+no_connect"))
    )
    (net (code "333") (name "unconnected-(U1-LA23-Pad119)") (class "Default")
      (node (ref "U1") (pin "119") (pinfunction "LA23_119") (pintype "passive+no_connect"))
    )
    (net (code "334") (name "unconnected-(U1-MLF(RES)-Pad132)") (class "Default")
      (node (ref "U1") (pin "132") (pinfunction "MLF(RES)_132") (pintype "passive+no_connect"))
    )
    (net (code "335") (name "unconnected-(U1-OUTP0-Pad100)") (class "Default")
      (node (ref "U1") (pin "100") (pinfunction "OUTP0_100") (pintype "passive+no_connect"))
    )
    (net (code "336") (name "unconnected-(U1-P0-Pad17)") (class "Default")
      (node (ref "U1") (pin "17") (pinfunction "P0_17") (pintype "passive+no_connect"))
    )
    (net (code "337") (name "unconnected-(U1-P1-Pad16)") (class "Default")
      (node (ref "U1") (pin "16") (pinfunction "P1_16") (pintype "passive+no_connect"))
    )
    (net (code "338") (name "unconnected-(U1-P2-Pad15)") (class "Default")
      (node (ref "U1") (pin "15") (pinfunction "P2_15") (pintype "passive+no_connect"))
    )
    (net (code "339") (name "unconnected-(U1-P3-Pad14)") (class "Default")
      (node (ref "U1") (pin "14") (pinfunction "P3_14") (pintype "passive+no_connect"))
    )
    (net (code "340") (name "unconnected-(U1-P4-Pad12)") (class "Default")
      (node (ref "U1") (pin "12") (pinfunction "P4_12") (pintype "passive+no_connect"))
    )
    (net (code "341") (name "unconnected-(U1-P5-Pad11)") (class "Default")
      (node (ref "U1") (pin "11") (pinfunction "P5_11") (pintype "passive+no_connect"))
    )
    (net (code "342") (name "unconnected-(U1-P6-Pad10)") (class "Default")
      (node (ref "U1") (pin "10") (pinfunction "P6_10") (pintype "passive+no_connect"))
    )
    (net (code "343") (name "unconnected-(U1-P7-Pad9)") (class "Default")
      (node (ref "U1") (pin "9") (pinfunction "P7_9") (pintype "passive+no_connect"))
    )
    (net (code "344") (name "unconnected-(U1-PCLK-Pad159)") (class "Default")
      (node (ref "U1") (pin "159") (pinfunction "PCLK_159") (pintype "passive+no_connect"))
    )
    (net (code "345") (name "unconnected-(U1-RESERVED-Pad63)") (class "Default")
      (node (ref "U1") (pin "63") (pinfunction "RESERVED_63") (pintype "passive+no_connect"))
    )
    (net (code "346") (name "unconnected-(U1-RESERVED-Pad112)") (class "Default")
      (node (ref "U1") (pin "112") (pinfunction "RESERVED_112") (pintype "passive+no_connect"))
    )
    (net (code "347") (name "unconnected-(U1-RESERVED-Pad123)") (class "Default")
      (node (ref "U1") (pin "123") (pinfunction "RESERVED_123") (pintype "passive+no_connect"))
    )
    (net (code "348") (name "unconnected-(U1-RESERVED-Pad127)") (class "Default")
      (node (ref "U1") (pin "127") (pinfunction "RESERVED_127") (pintype "passive+no_connect"))
    )
    (net (code "349") (name "unconnected-(U1-SBHE-Pad99)") (class "Default")
      (node (ref "U1") (pin "99") (pinfunction "SBHE_99") (pintype "passive+no_connect"))
    )
    (net (code "350") (name "unconnected-(U1-SD8-Pad110)") (class "Default")
      (node (ref "U1") (pin "110") (pinfunction "SD8_110") (pintype "passive+no_connect"))
    )
    (net (code "351") (name "unconnected-(U1-SD9-Pad109)") (class "Default")
      (node (ref "U1") (pin "109") (pinfunction "SD9_109") (pintype "passive+no_connect"))
    )
    (net (code "352") (name "unconnected-(U1-SD10-Pad108)") (class "Default")
      (node (ref "U1") (pin "108") (pinfunction "SD10_108") (pintype "passive+no_connect"))
    )
    (net (code "353") (name "unconnected-(U1-SD11-Pad107)") (class "Default")
      (node (ref "U1") (pin "107") (pinfunction "SD11_107") (pintype "passive+no_connect"))
    )
    (net (code "354") (name "unconnected-(U1-SD12-Pad106)") (class "Default")
      (node (ref "U1") (pin "106") (pinfunction "SD12_106") (pintype "passive+no_connect"))
    )
    (net (code "355") (name "unconnected-(U1-SD13-Pad105)") (class "Default")
      (node (ref "U1") (pin "105") (pinfunction "SD13_105") (pintype "passive+no_connect"))
    )
    (net (code "356") (name "unconnected-(U1-SD14-Pad104)") (class "Default")
      (node (ref "U1") (pin "104") (pinfunction "SD14_104") (pintype "passive+no_connect"))
    )
    (net (code "357") (name "unconnected-(U1-SD15-Pad103)") (class "Default")
      (node (ref "U1") (pin "103") (pinfunction "SD15_103") (pintype "passive+no_connect"))
    )
    (net (code "358") (name "unconnected-(U1-VREF-Pad20)") (class "Default")
      (node (ref "U1") (pin "20") (pinfunction "VREF_20") (pintype "passive+no_connect"))
    )
    (net (code "359") (name "unconnected-(U1-~{{BLANK}}-Pad44)") (class "Default")
      (node (ref "U1") (pin "44") (pinfunction "~{{BLANK}}_44") (pintype "passive+no_connect"))
    )
    (net (code "360") (name "unconnected-(U2-NC-Pad5)") (class "Default")
      (node (ref "U2") (pin "5") (pinfunction "NC_5") (pintype "passive"))
    )
    (net (code "361") (name "unconnected-(U3-NC-Pad5)") (class "Default")
      (node (ref "U3") (pin "5") (pinfunction "NC_5") (pintype "passive"))
    )
    (net (code "362") (name "unconnected-(U4-NC-Pad5)") (class "Default")
      (node (ref "U4") (pin "5") (pinfunction "NC_5") (pintype "passive"))
    )
    (net (code "363") (name "unconnected-(U5-NC-Pad5)") (class "Default")
      (node (ref "U5") (pin "5") (pinfunction "NC_5") (pintype "passive"))
    )
    (net (code "364") (name "unconnected-(U7-Y0-Pad15)") (class "Default")
      (node (ref "U7") (pin "15") (pinfunction "Y0_15") (pintype "output+no_connect"))
    )
    (net (code "365") (name "unconnected-(U7-Y1-Pad14)") (class "Default")
      (node (ref "U7") (pin "14") (pinfunction "Y1_14") (pintype "output+no_connect"))
    )
    (net (code "366") (name "unconnected-(U7-Y2-Pad13)") (class "Default")
      (node (ref "U7") (pin "13") (pinfunction "Y2_13") (pintype "output+no_connect"))
    )
    (net (code "367") (name "unconnected-(U8-Y0-Pad15)") (class "Default")
      (node (ref "U8") (pin "15") (pinfunction "Y0_15") (pintype "output+no_connect"))
    )
    (net (code "368") (name "unconnected-(U8-Y1-Pad14)") (class "Default")
      (node (ref "U8") (pin "14") (pinfunction "Y1_14") (pintype "output+no_connect"))
    )
    (net (code "369") (name "unconnected-(U8-Y2-Pad13)") (class "Default")
      (node (ref "U8") (pin "13") (pinfunction "Y2_13") (pintype "output+no_connect"))
    )
    (net (code "370") (name "unconnected-(U8-Y3-Pad12)") (class "Default")
      (node (ref "U8") (pin "12") (pinfunction "Y3_12") (pintype "output+no_connect"))
    )
    (net (code "371") (name "unconnected-(U8-Y4-Pad11)") (class "Default")
      (node (ref "U8") (pin "11") (pinfunction "Y4_11") (pintype "output+no_connect"))
    )
    (net (code "372") (name "unconnected-(U8-Y5-Pad10)") (class "Default")
      (node (ref "U8") (pin "10") (pinfunction "Y5_10") (pintype "output+no_connect"))
    )
    (net (code "373") (name "unconnected-(U8-Y6-Pad9)") (class "Default")
      (node (ref "U8") (pin "9") (pinfunction "Y6_9") (pintype "output+no_connect"))
    )
    (net (code "374") (name "unconnected-(U9-DDIS-Pad26)") (class "Default")
      (node (ref "U9") (pin "26") (pinfunction "DDIS_26") (pintype "passive+no_connect"))
    )
    (net (code "375") (name "unconnected-(U9-Pad1)") (class "Default")
      (node (ref "U9") (pin "1") (pinfunction "1_1") (pintype "passive"))
    )
    (net (code "376") (name "unconnected-(U9-Pad12)") (class "Default")
      (node (ref "U9") (pin "12") (pinfunction "12_12") (pintype "passive"))
    )
    (net (code "377") (name "unconnected-(U9-Pad23)") (class "Default")
      (node (ref "U9") (pin "23") (pinfunction "23_23") (pintype "passive"))
    )
    (net (code "378") (name "unconnected-(U9-Pad34)") (class "Default")
      (node (ref "U9") (pin "34") (pinfunction "34_34") (pintype "passive"))
    )
    (net (code "379") (name "unconnected-(U9-XOUT-Pad19)") (class "Default")
      (node (ref "U9") (pin "19") (pinfunction "XOUT_19") (pintype "passive+no_connect"))
    )
    (net (code "380") (name "unconnected-(U9-~{{OUT1}}-Pad38)") (class "Default")
      (node (ref "U9") (pin "38") (pinfunction "~{{OUT1}}_38") (pintype "passive+no_connect"))
    )
    (net (code "381") (name "unconnected-(U9-~{{OUT2}}-Pad35)") (class "Default")
      (node (ref "U9") (pin "35") (pinfunction "~{{OUT2}}_35") (pintype "passive+no_connect"))
    )
    (net (code "382") (name "unconnected-(U9-~{{RXRDY}}-Pad32)") (class "Default")
      (node (ref "U9") (pin "32") (pinfunction "~{{RXRDY}}_32") (pintype "passive+no_connect"))
    )
    (net (code "383") (name "unconnected-(U9-~{{TXRDY}}-Pad27)") (class "Default")
      (node (ref "U9") (pin "27") (pinfunction "~{{TXRDY}}_27") (pintype "passive+no_connect"))
    )
    (net (code "384") (name "unconnected-(U12-DRATE1-Pad29)") (class "Default")
      (node (ref "U12") (pin "29") (pinfunction "DRATE1_29") (pintype "passive+no_connect"))
    )
    (net (code "385") (name "unconnected-(U12-DS2-Pad64)") (class "Default")
      (node (ref "U12") (pin "64") (pinfunction "DS2_64") (pintype "passive+no_connect"))
    )
    (net (code "386") (name "unconnected-(U12-DS3-Pad67)") (class "Default")
      (node (ref "U12") (pin "67") (pinfunction "DS3_67") (pintype "passive+no_connect"))
    )
    (net (code "387") (name "unconnected-(U12-ME2-Pad63)") (class "Default")
      (node (ref "U12") (pin "63") (pinfunction "ME2_63") (pintype "passive+no_connect"))
    )
    (net (code "388") (name "unconnected-(U12-ME3-Pad66)") (class "Default")
      (node (ref "U12") (pin "66") (pinfunction "ME3_66") (pintype "passive+no_connect"))
    )
    (net (code "389") (name "unconnected-(U12-MFM-Pad48)") (class "Default")
      (node (ref "U12") (pin "48") (pinfunction "MFM_48") (pintype "passive+no_connect"))
    )
    (net (code "390") (name "unconnected-(U12-NC-Pad42)") (class "Default")
      (node (ref "U12") (pin "42") (pinfunction "NC_42") (pintype "passive"))
    )
    (net (code "391") (name "unconnected-(U12-NC-Pad43)") (class "Default")
      (node (ref "U12") (pin "43") (pinfunction "NC_43") (pintype "passive"))
    )
    (net (code "392") (name "unconnected-(U12-NC-Pad44)") (class "Default")
      (node (ref "U12") (pin "44") (pinfunction "NC_44") (pintype "passive"))
    )
    (net (code "393") (name "unconnected-(U12-NC-Pad47)") (class "Default")
      (node (ref "U12") (pin "47") (pinfunction "NC_47") (pintype "passive"))
    )
    (net (code "394") (name "unconnected-(U14-NC-Pad26)") (class "Default")
      (node (ref "U14") (pin "26") (pinfunction "NC_26") (pintype "passive"))
    )
    (net (code "395") (name "unconnected-(U16-Y0-Pad15)") (class "Default")
      (node (ref "U16") (pin "15") (pinfunction "Y0_15") (pintype "output+no_connect"))
    )
    (net (code "396") (name "unconnected-(U16-Y3-Pad12)") (class "Default")
      (node (ref "U16") (pin "12") (pinfunction "Y3_12") (pintype "output+no_connect"))
    )
    (net (code "397") (name "unconnected-(U16-Y4-Pad11)") (class "Default")
      (node (ref "U16") (pin "11") (pinfunction "Y4_11") (pintype "output+no_connect"))
    )
    (net (code "398") (name "unconnected-(U16-Y7-Pad7)") (class "Default")
      (node (ref "U16") (pin "7") (pinfunction "Y7_7") (pintype "output+no_connect"))
    )
    (net (code "399") (name "unconnected-(U17-Y1-Pad14)") (class "Default")
      (node (ref "U17") (pin "14") (pinfunction "Y1_14") (pintype "output+no_connect"))
    )
    (net (code "400") (name "unconnected-(U17-Y2-Pad13)") (class "Default")
      (node (ref "U17") (pin "13") (pinfunction "Y2_13") (pintype "output+no_connect"))
    )
    (net (code "401") (name "unconnected-(U17-Y3-Pad12)") (class "Default")
      (node (ref "U17") (pin "12") (pinfunction "Y3_12") (pintype "output+no_connect"))
    )
    (net (code "402") (name "unconnected-(U17-Y4-Pad11)") (class "Default")
      (node (ref "U17") (pin "11") (pinfunction "Y4_11") (pintype "output+no_connect"))
    )
    (net (code "403") (name "unconnected-(U17-Y5-Pad10)") (class "Default")
      (node (ref "U17") (pin "10") (pinfunction "Y5_10") (pintype "output+no_connect"))
    )
    (net (code "404") (name "unconnected-(U17-Y6-Pad9)") (class "Default")
      (node (ref "U17") (pin "9") (pinfunction "Y6_9") (pintype "output+no_connect"))
    )
    (net (code "405") (name "unconnected-(U17-Y7-Pad7)") (class "Default")
      (node (ref "U17") (pin "7") (pinfunction "Y7_7") (pintype "output+no_connect"))
    )
    (net (code "406") (name "unconnected-(U23-GAIN-Pad1)") (class "Default")
      (node (ref "U23") (pin "1") (pinfunction "GAIN_1") (pintype "input+no_connect"))
    )
    (net (code "407") (name "unconnected-(U23-GAIN-Pad8)") (class "Default")
      (node (ref "U23") (pin "8") (pinfunction "GAIN_8") (pintype "input+no_connect"))
    )
    (net (code "408") (name "unconnected-(U24-CD+-Pad54)") (class "Default")
      (node (ref "U24") (pin "54") (pinfunction "CD+_54") (pintype "passive+no_connect"))
    )
    (net (code "409") (name "unconnected-(U24-CD--Pad53)") (class "Default")
      (node (ref "U24") (pin "53") (pinfunction "CD-_53") (pintype "passive+no_connect"))
    )
    (net (code "410") (name "unconnected-(U24-INT4{slash}IRQ10-Pad100)") (class "Default")
      (node (ref "U24") (pin "100") (pinfunction "INT4/IRQ10_100") (pintype "passive+no_connect"))
    )
    (net (code "411") (name "unconnected-(U24-INT5{slash}IRQ11-Pad99)") (class "Default")
      (node (ref "U24") (pin "99") (pinfunction "INT5/IRQ11_99") (pintype "passive+no_connect"))
    )
    (net (code "412") (name "unconnected-(U24-INT6{slash}IRQ12-Pad98)") (class "Default")
      (node (ref "U24") (pin "98") (pinfunction "INT6/IRQ12_98") (pintype "passive+no_connect"))
    )
    (net (code "413") (name "unconnected-(U24-INT7{slash}IRQ15-Pad97)") (class "Default")
      (node (ref "U24") (pin "97") (pinfunction "INT7/IRQ15_97") (pintype "passive+no_connect"))
    )
    (net (code "414") (name "unconnected-(U24-LED2{slash}LED_TX-Pad63)") (class "Default")
      (node (ref "U24") (pin "63") (pinfunction "LED2/LED_TX_63") (pintype "passive+no_connect"))
    )
    (net (code "415") (name "unconnected-(U24-LEDBNC-Pad60)") (class "Default")
      (node (ref "U24") (pin "60") (pinfunction "LEDBNC_60") (pintype "passive+no_connect"))
    )
    (net (code "416") (name "unconnected-(U24-RX+-Pad56)") (class "Default")
      (node (ref "U24") (pin "56") (pinfunction "RX+_56") (pintype "passive+no_connect"))
    )
    (net (code "417") (name "unconnected-(U24-RX--Pad55)") (class "Default")
      (node (ref "U24") (pin "55") (pinfunction "RX-_55") (pintype "passive+no_connect"))
    )
    (net (code "418") (name "unconnected-(U24-SD8-Pad95)") (class "Default")
      (node (ref "U24") (pin "95") (pinfunction "SD8_95") (pintype "passive+no_connect"))
    )
    (net (code "419") (name "unconnected-(U24-SD9-Pad94)") (class "Default")
      (node (ref "U24") (pin "94") (pinfunction "SD9_94") (pintype "passive+no_connect"))
    )
    (net (code "420") (name "unconnected-(U24-SD10-Pad93)") (class "Default")
      (node (ref "U24") (pin "93") (pinfunction "SD10_93") (pintype "passive+no_connect"))
    )
    (net (code "421") (name "unconnected-(U24-SD11-Pad92)") (class "Default")
      (node (ref "U24") (pin "92") (pinfunction "SD11_92") (pintype "passive+no_connect"))
    )
    (net (code "422") (name "unconnected-(U24-SD12-Pad91)") (class "Default")
      (node (ref "U24") (pin "91") (pinfunction "SD12_91") (pintype "passive+no_connect"))
    )
    (net (code "423") (name "unconnected-(U24-SD13-Pad90)") (class "Default")
      (node (ref "U24") (pin "90") (pinfunction "SD13_90") (pintype "passive+no_connect"))
    )
    (net (code "424") (name "unconnected-(U24-SD14-Pad88)") (class "Default")
      (node (ref "U24") (pin "88") (pinfunction "SD14_88") (pintype "passive+no_connect"))
    )
    (net (code "425") (name "unconnected-(U24-SD15-Pad87)") (class "Default")
      (node (ref "U24") (pin "87") (pinfunction "SD15_87") (pintype "passive+no_connect"))
    )
    (net (code "426") (name "unconnected-(U24-TX+-Pad49)") (class "Default")
      (node (ref "U24") (pin "49") (pinfunction "TX+_49") (pintype "passive+no_connect"))
    )
    (net (code "427") (name "unconnected-(U24-TX--Pad48)") (class "Default")
      (node (ref "U24") (pin "48") (pinfunction "TX-_48") (pintype "passive+no_connect"))
    )
    (net (code "428") (name "unconnected-(U25-NC-Pad7)") (class "Default")
      (node (ref "U25") (pin "7") (pinfunction "NC_7") (pintype "passive"))
    )
    (net (code "429") (name "unconnected-(U27-MOT-Pad1)") (class "Default")
      (node (ref "U27") (pin "1") (pinfunction "MOT_1") (pintype "bidirectional+no_connect"))
    )
    (net (code "430") (name "unconnected-(U27-NC-Pad22)") (class "Default")
      (node (ref "U27") (pin "22") (pinfunction "NC_22") (pintype "bidirectional+no_connect"))
    )
    (net (code "431") (name "unconnected-(U27-SQW-Pad23)") (class "Default")
      (node (ref "U27") (pin "23") (pinfunction "SQW_23") (pintype "bidirectional+no_connect"))
    )
    (net (code "432") (name "unconnected-(U29-1Y0-Pad4)") (class "Default")
      (node (ref "U29") (pin "4") (pinfunction "1Y0_4") (pintype "output"))
    )
    (net (code "433") (name "unconnected-(U29-1Y1-Pad5)") (class "Default")
      (node (ref "U29") (pin "5") (pinfunction "1Y1_5") (pintype "output"))
    )
    (net (code "434") (name "unconnected-(U29-1Y3-Pad7)") (class "Default")
      (node (ref "U29") (pin "7") (pinfunction "1Y3_7") (pintype "output"))
    )
    (net (code "435") (name "unconnected-(U29-2Y1-Pad11)") (class "Default")
      (node (ref "U29") (pin "11") (pinfunction "2Y1_11") (pintype "output"))
    )
    (net (code "436") (name "unconnected-(U29-2Y3-Pad9)") (class "Default")
      (node (ref "U29") (pin "9") (pinfunction "2Y3_9") (pintype "output"))
    )
    (net (code "437") (name "unconnected-(U30-~{1Y}-Pad2)") (class "Default")
      (node (ref "U30") (pin "2") (pinfunction "~{1Y}_2") (pintype "output+no_connect"))
    )
    (net (code "438") (name "unconnected-(U30-~{2Y}-Pad4)") (class "Default")
      (node (ref "U30") (pin "4") (pinfunction "~{2Y}_4") (pintype "output+no_connect"))
    )
    (net (code "439") (name "unconnected-(U30-~{3Y}-Pad6)") (class "Default")
      (node (ref "U30") (pin "6") (pinfunction "~{3Y}_6") (pintype "output+no_connect"))
    )
    (net (code "440") (name "unconnected-(U30-~{4Y}-Pad8)") (class "Default")
      (node (ref "U30") (pin "8") (pinfunction "~{4Y}_8") (pintype "output+no_connect"))
    )
  )
)
